# zulu_a7.net
KiCad netlist of a schematic drawn in EAGLE
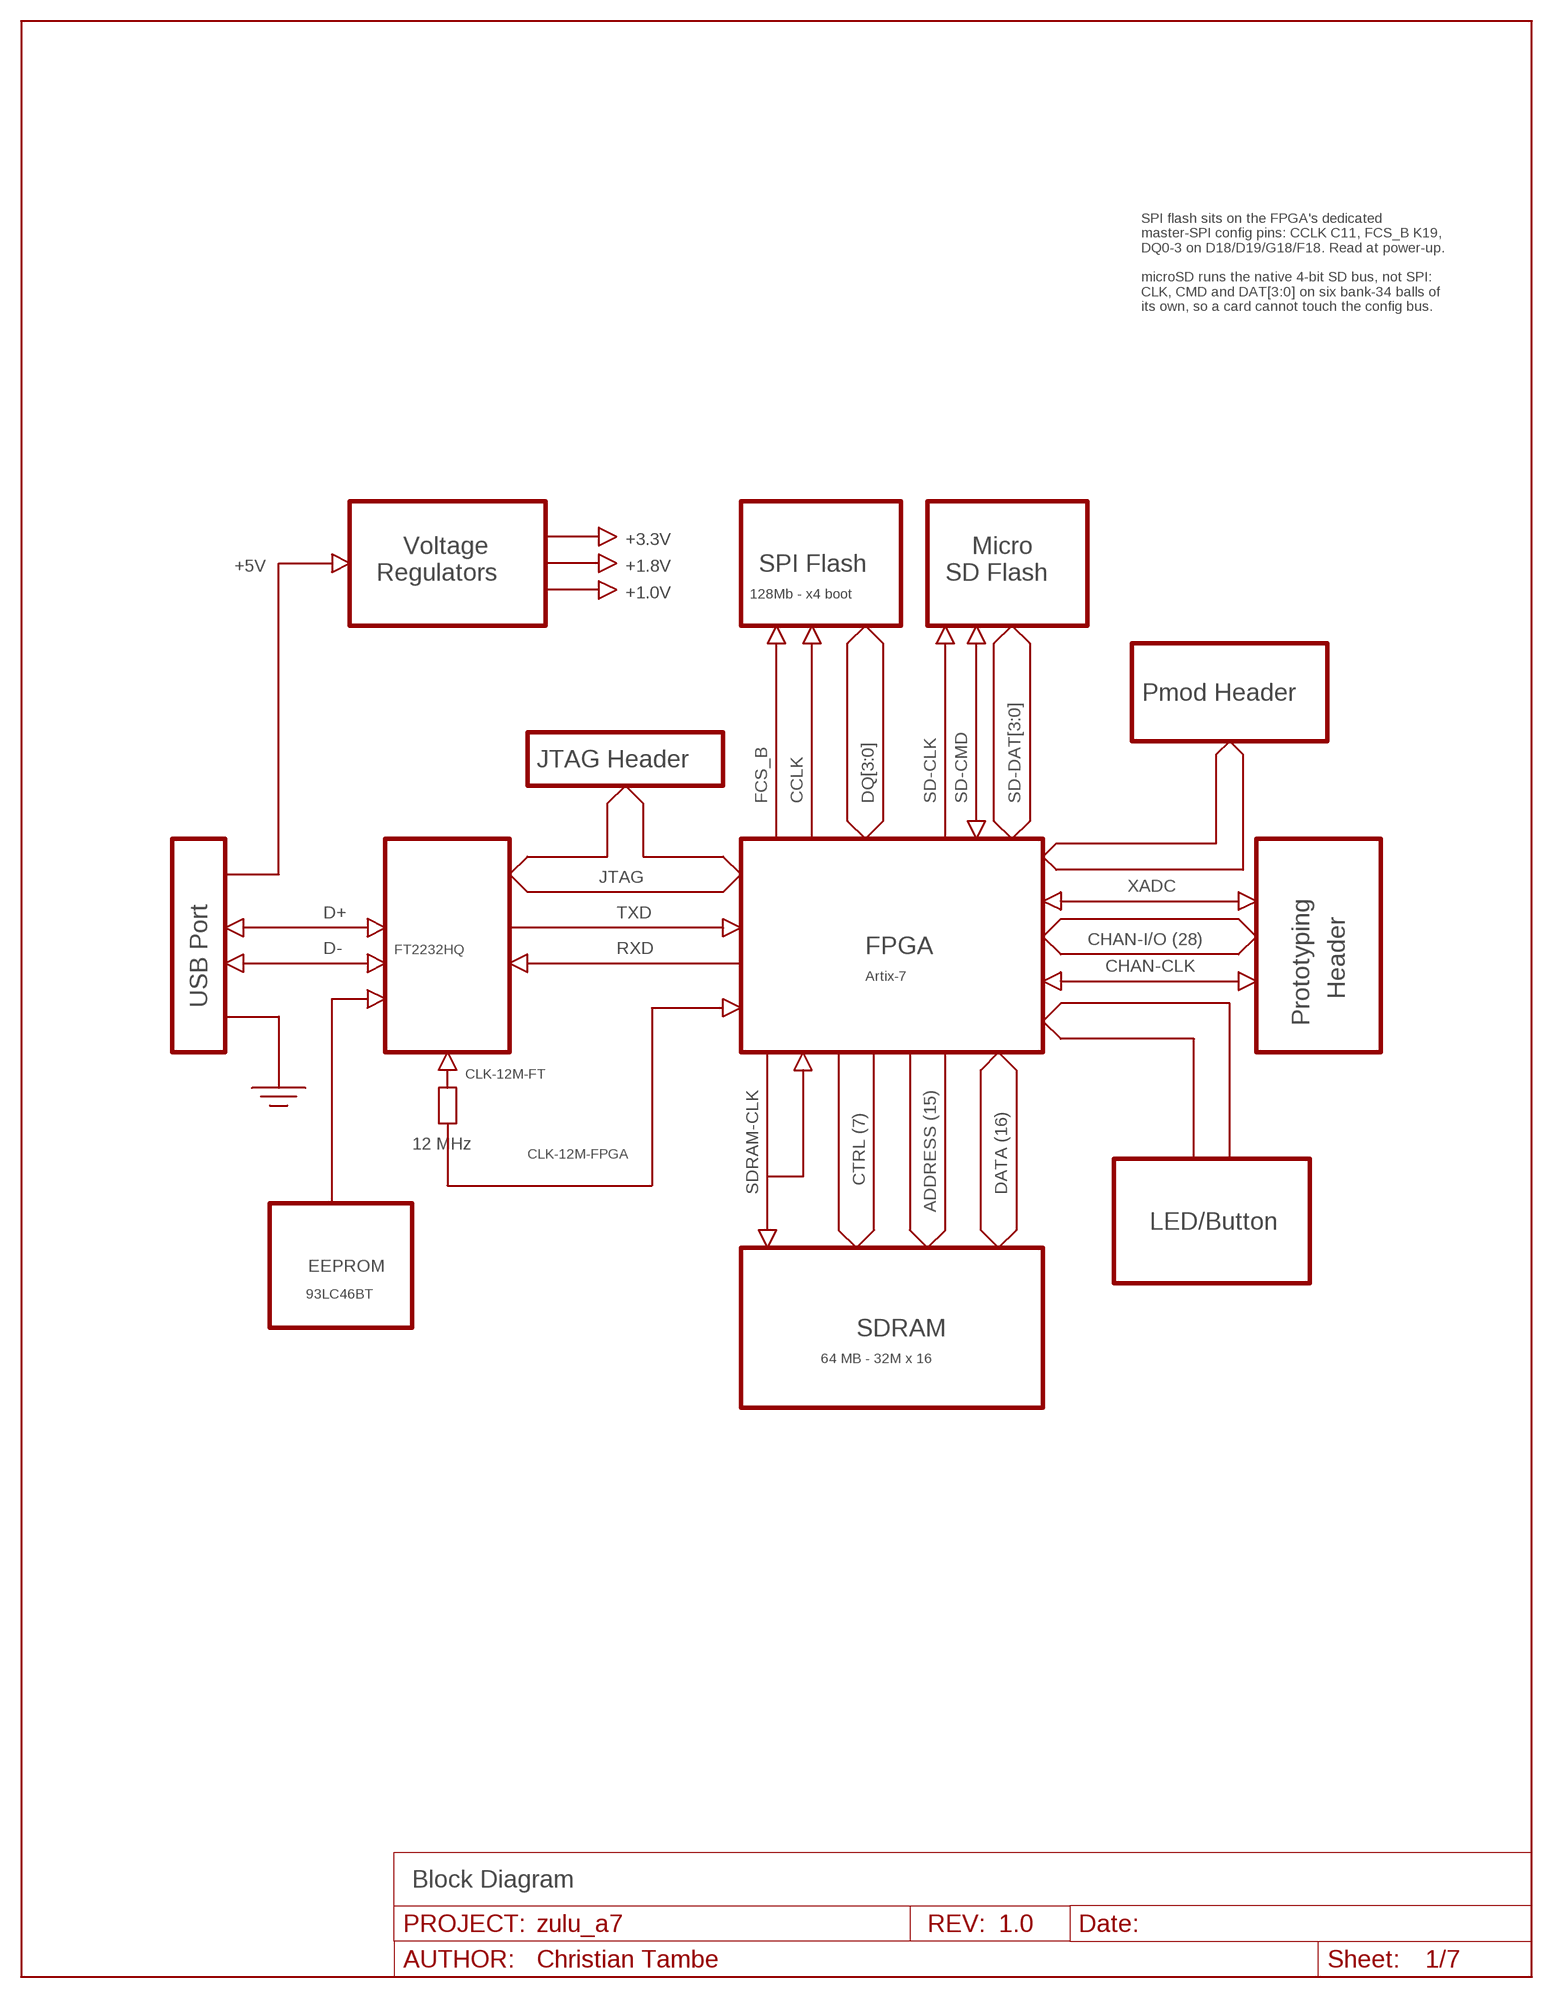
[diagram p0: schematic, sheet 1]
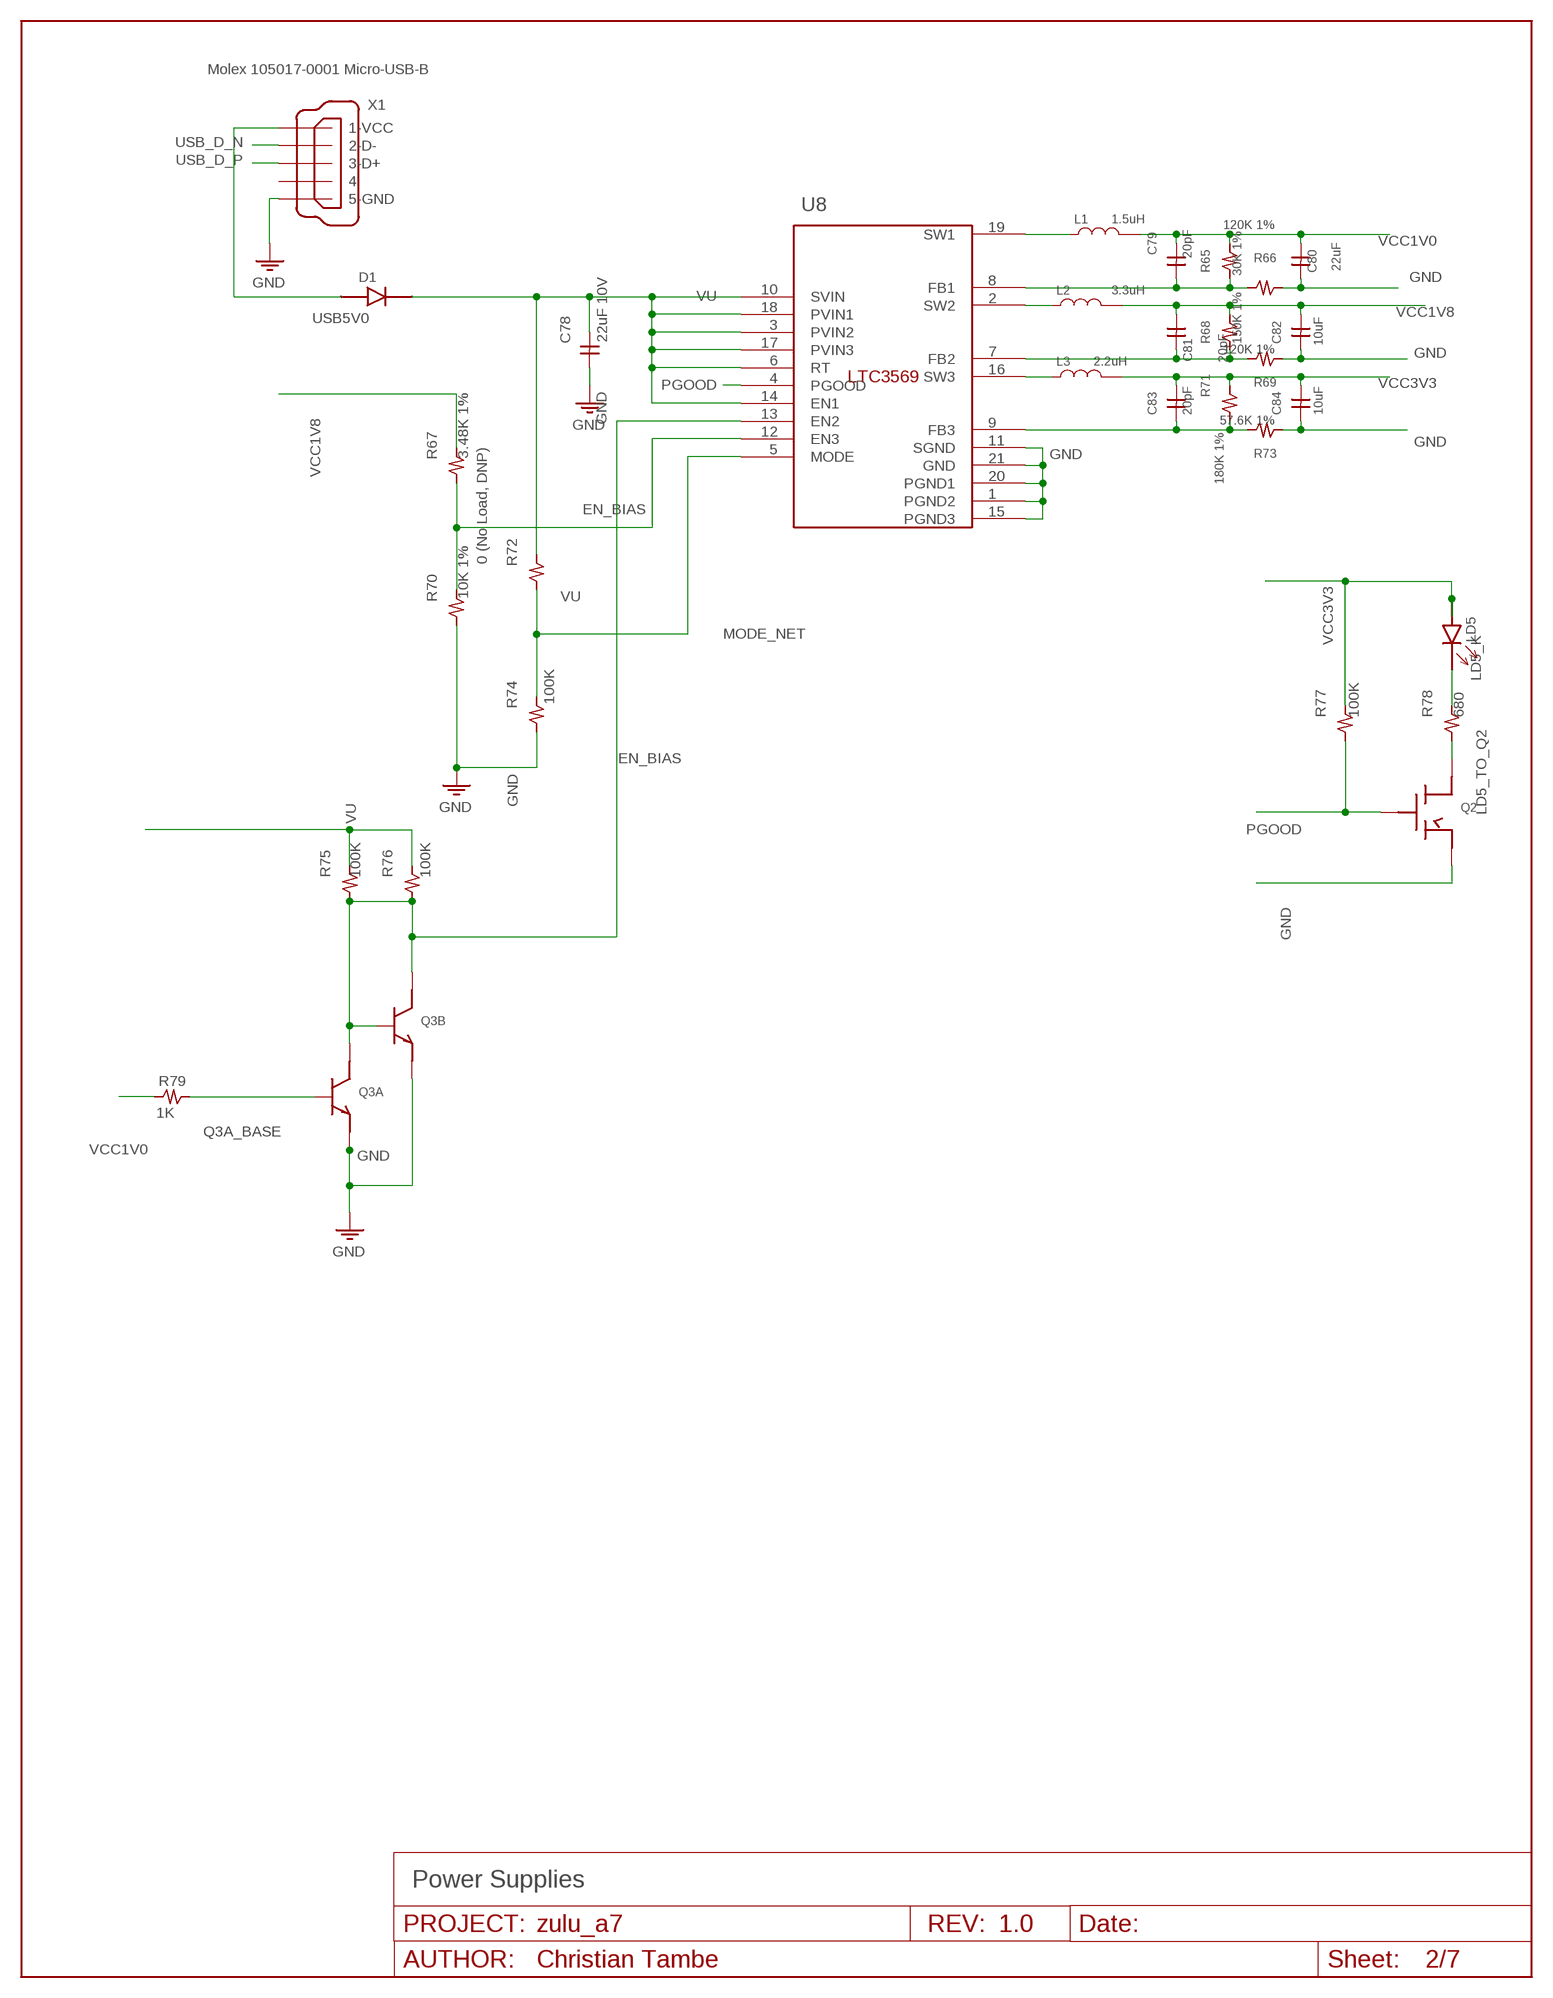
[diagram p1: schematic, sheet 2]
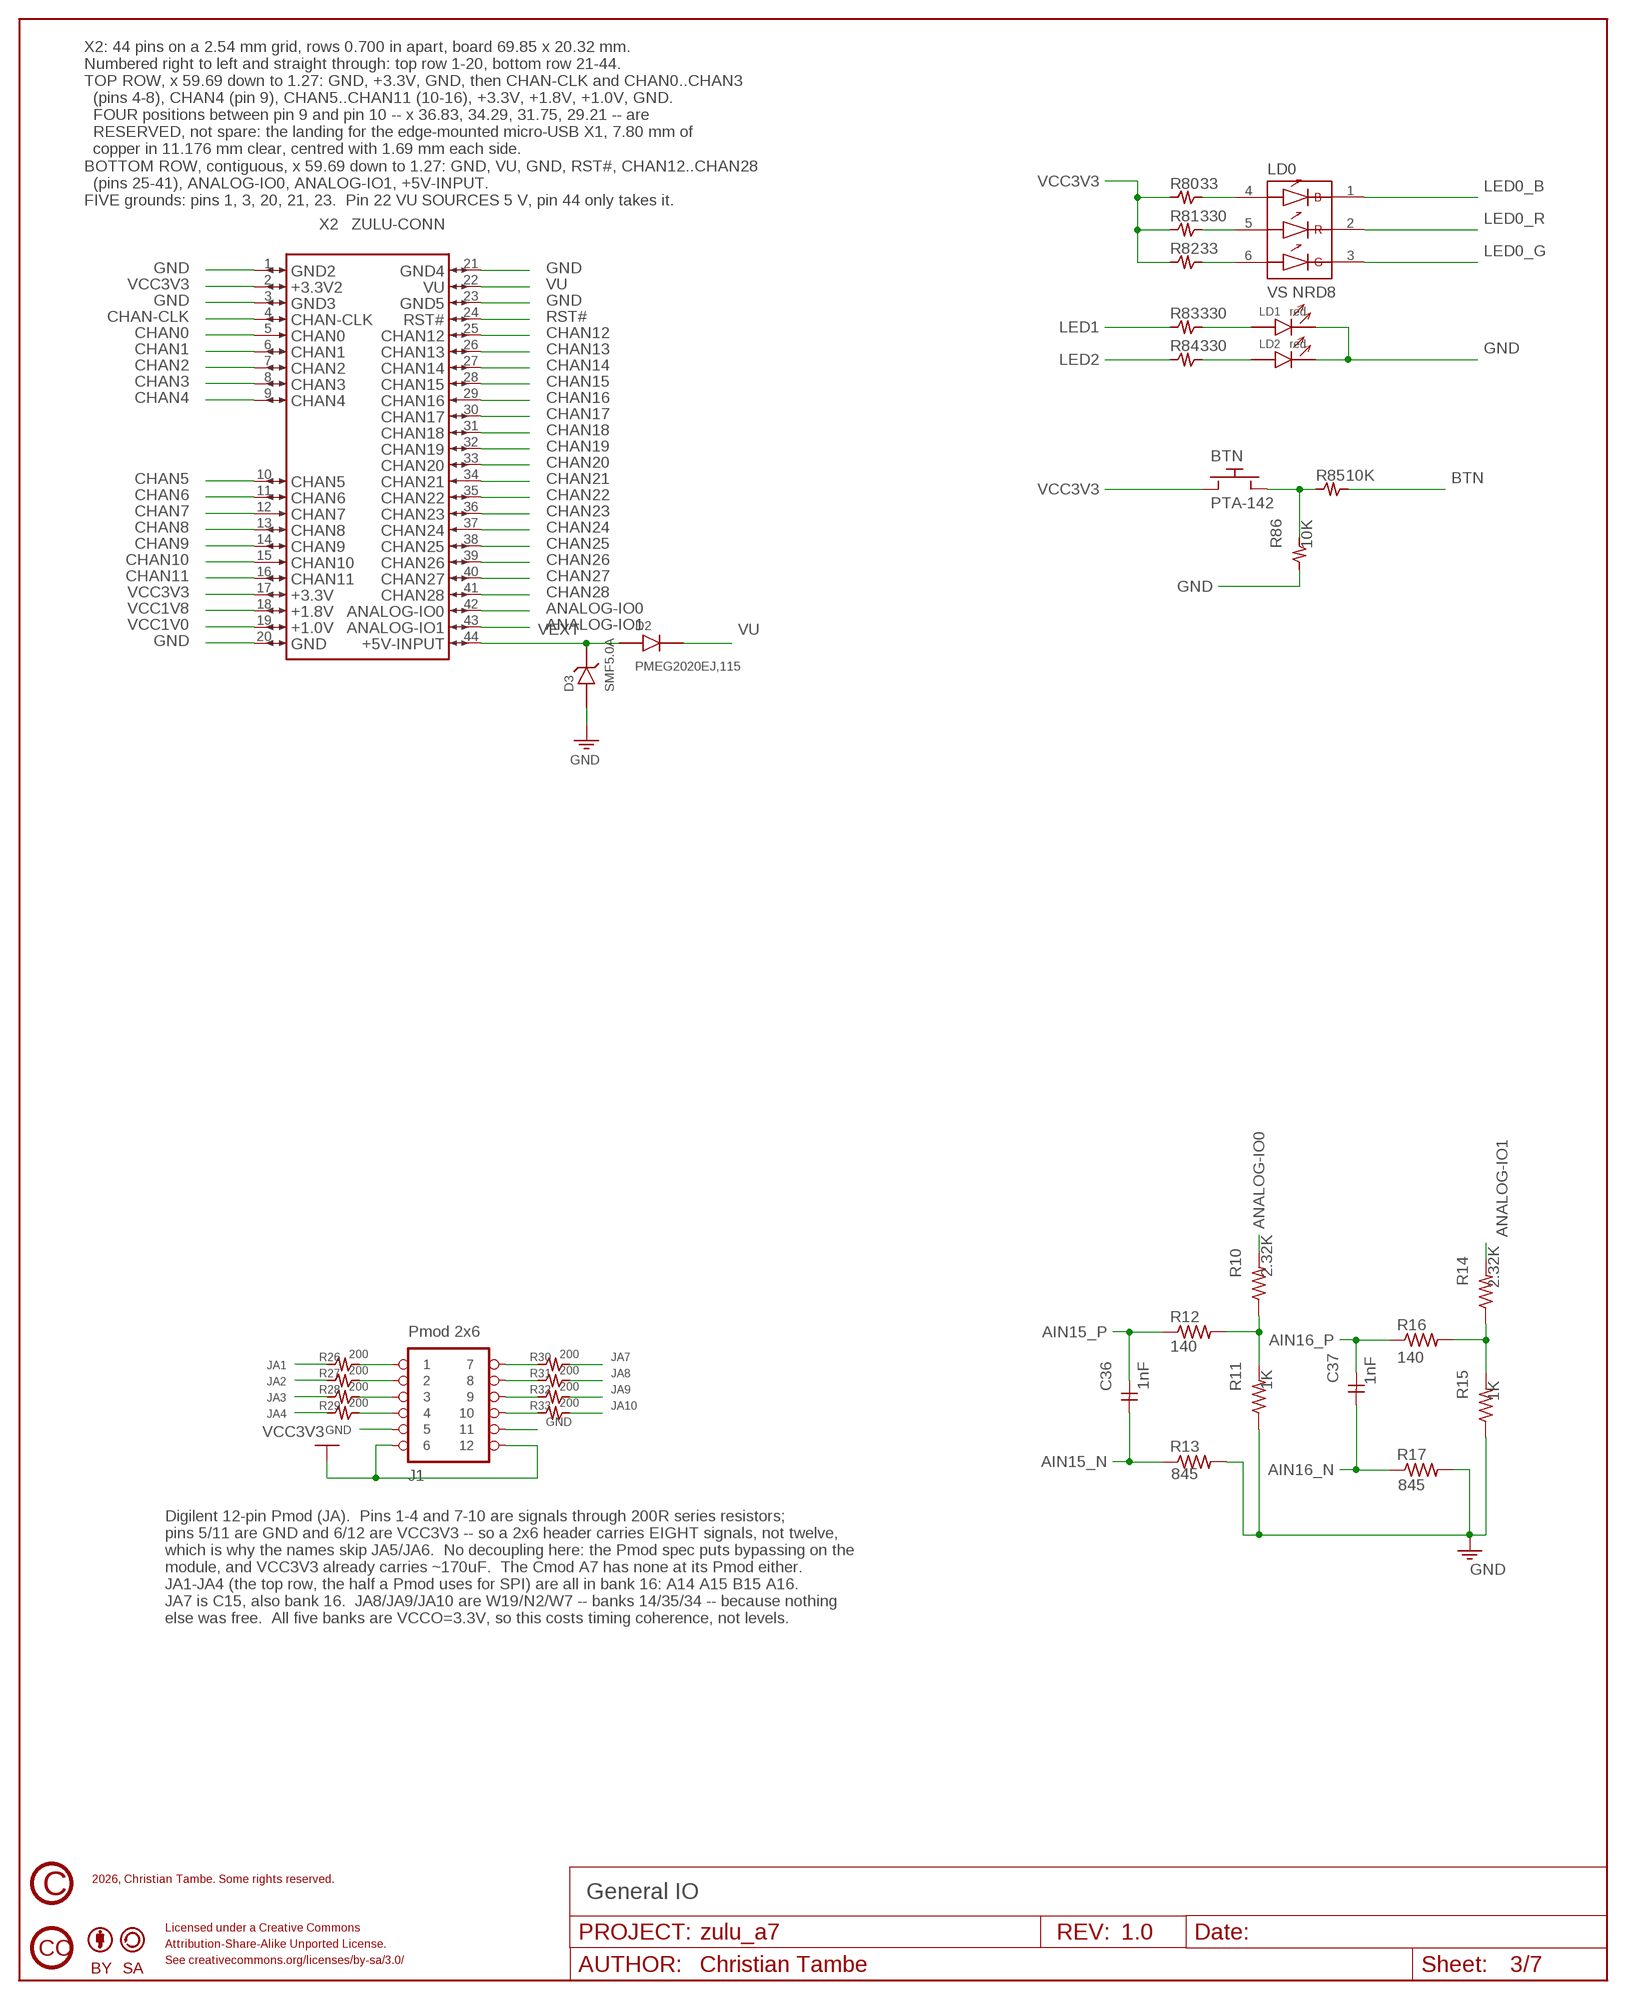
[diagram p2: schematic, sheet 3]
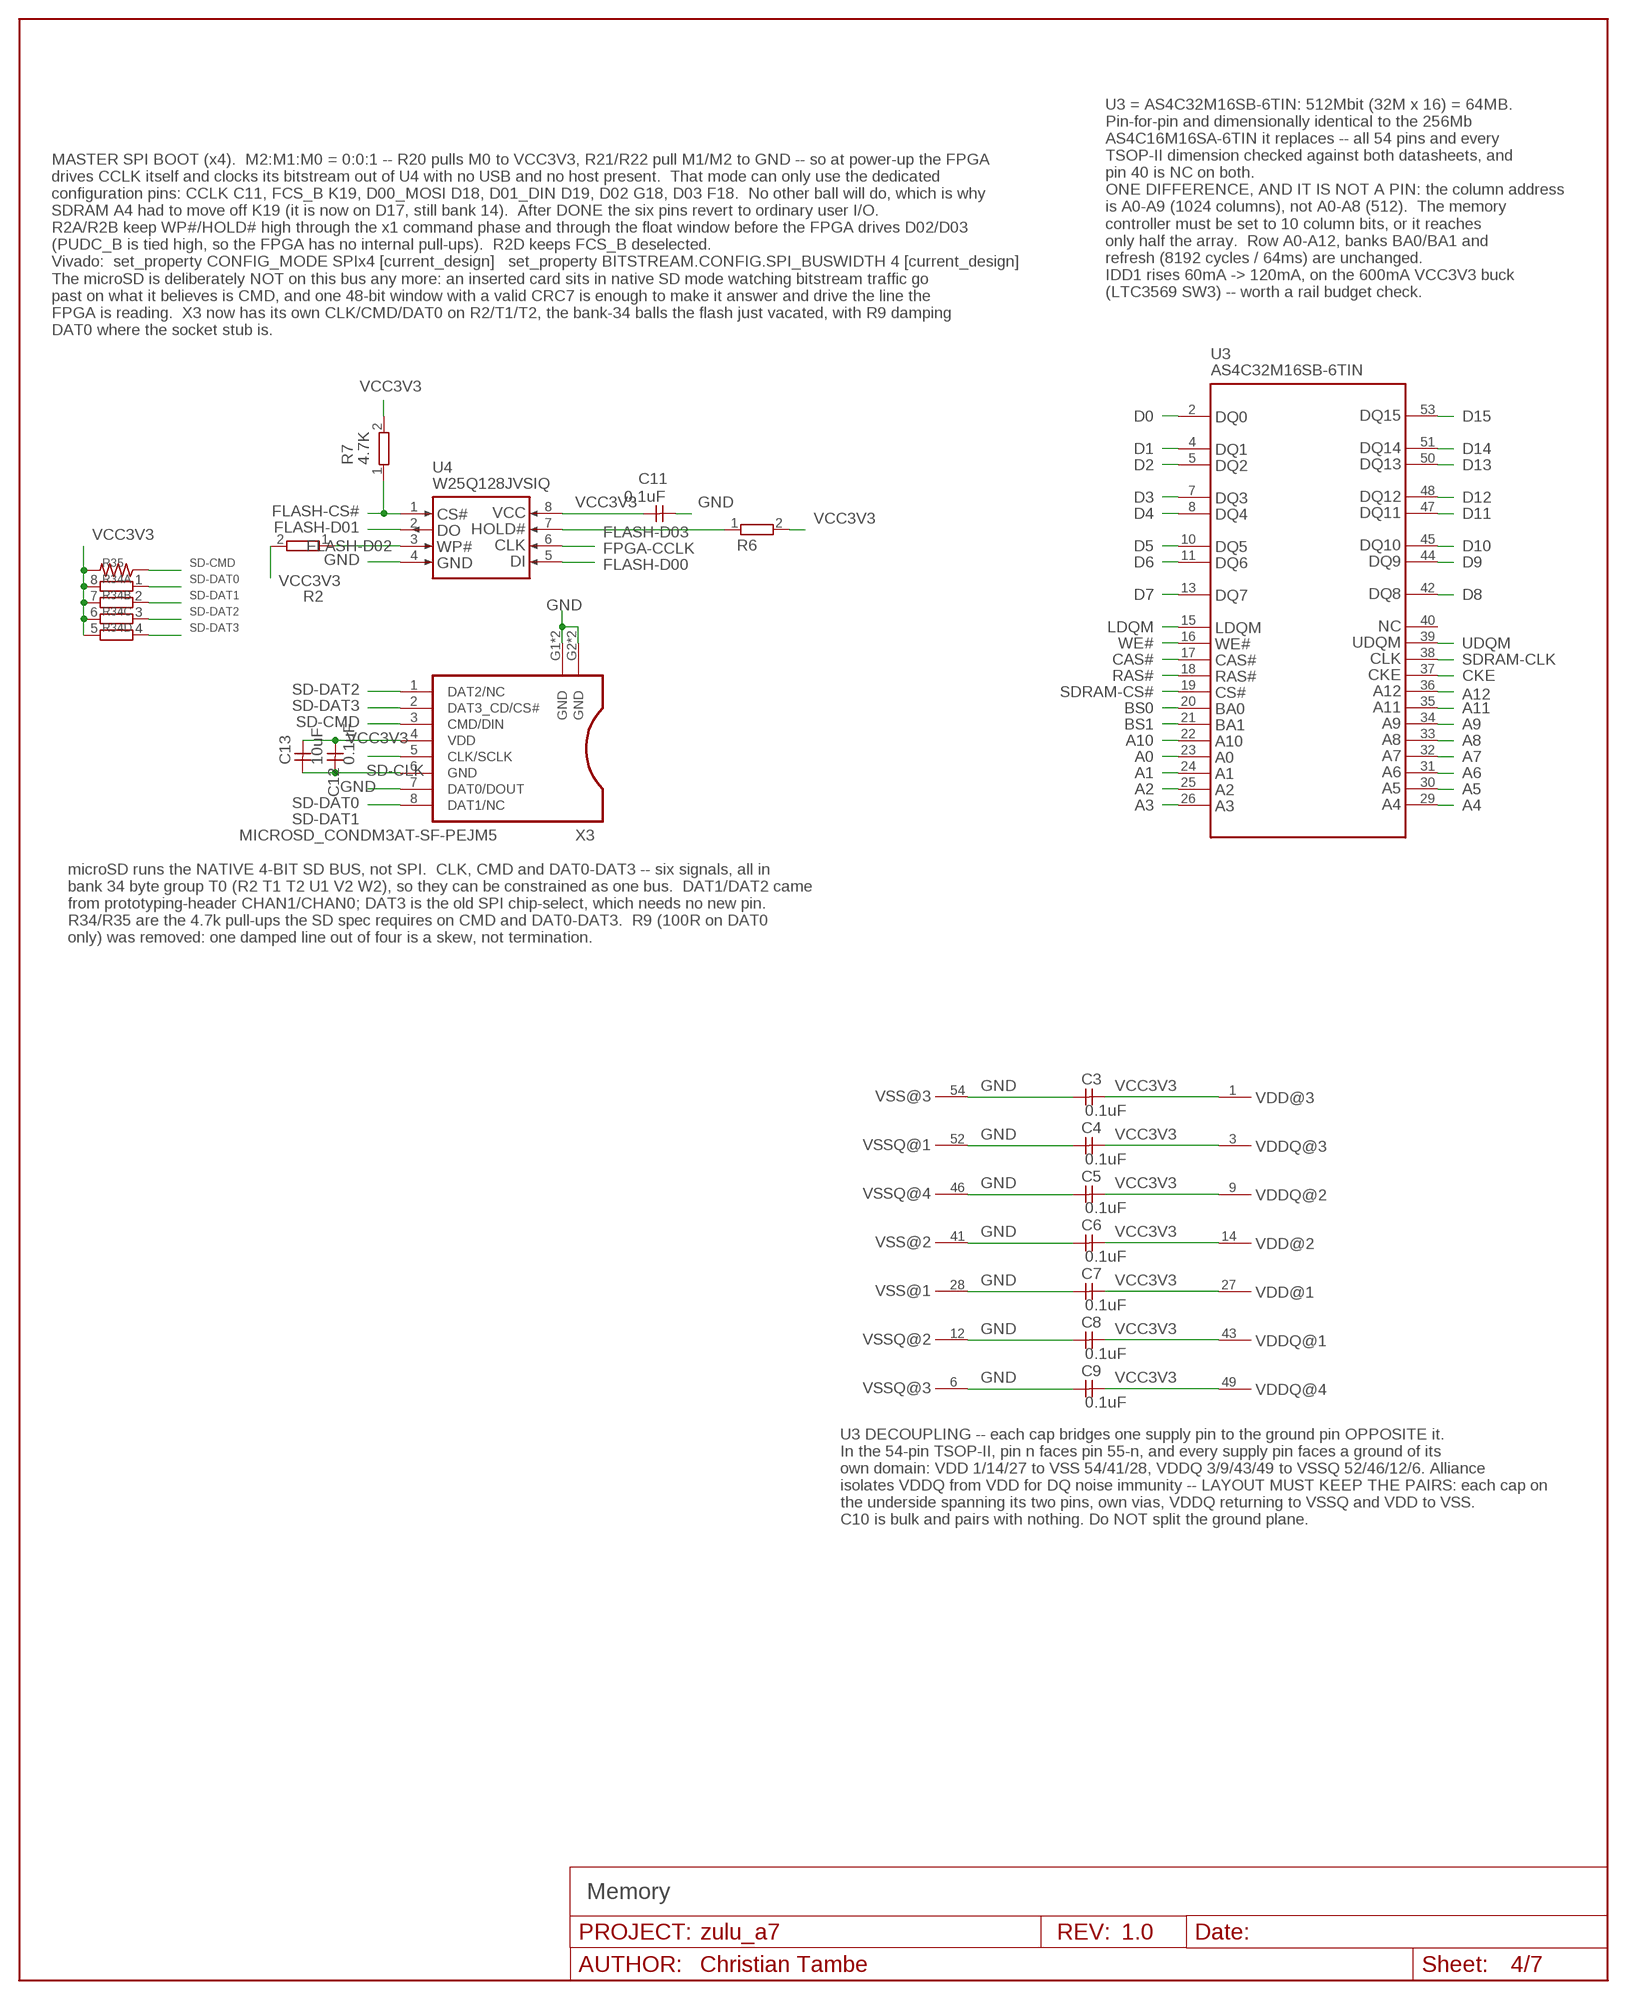
[diagram p3: schematic, sheet 4]
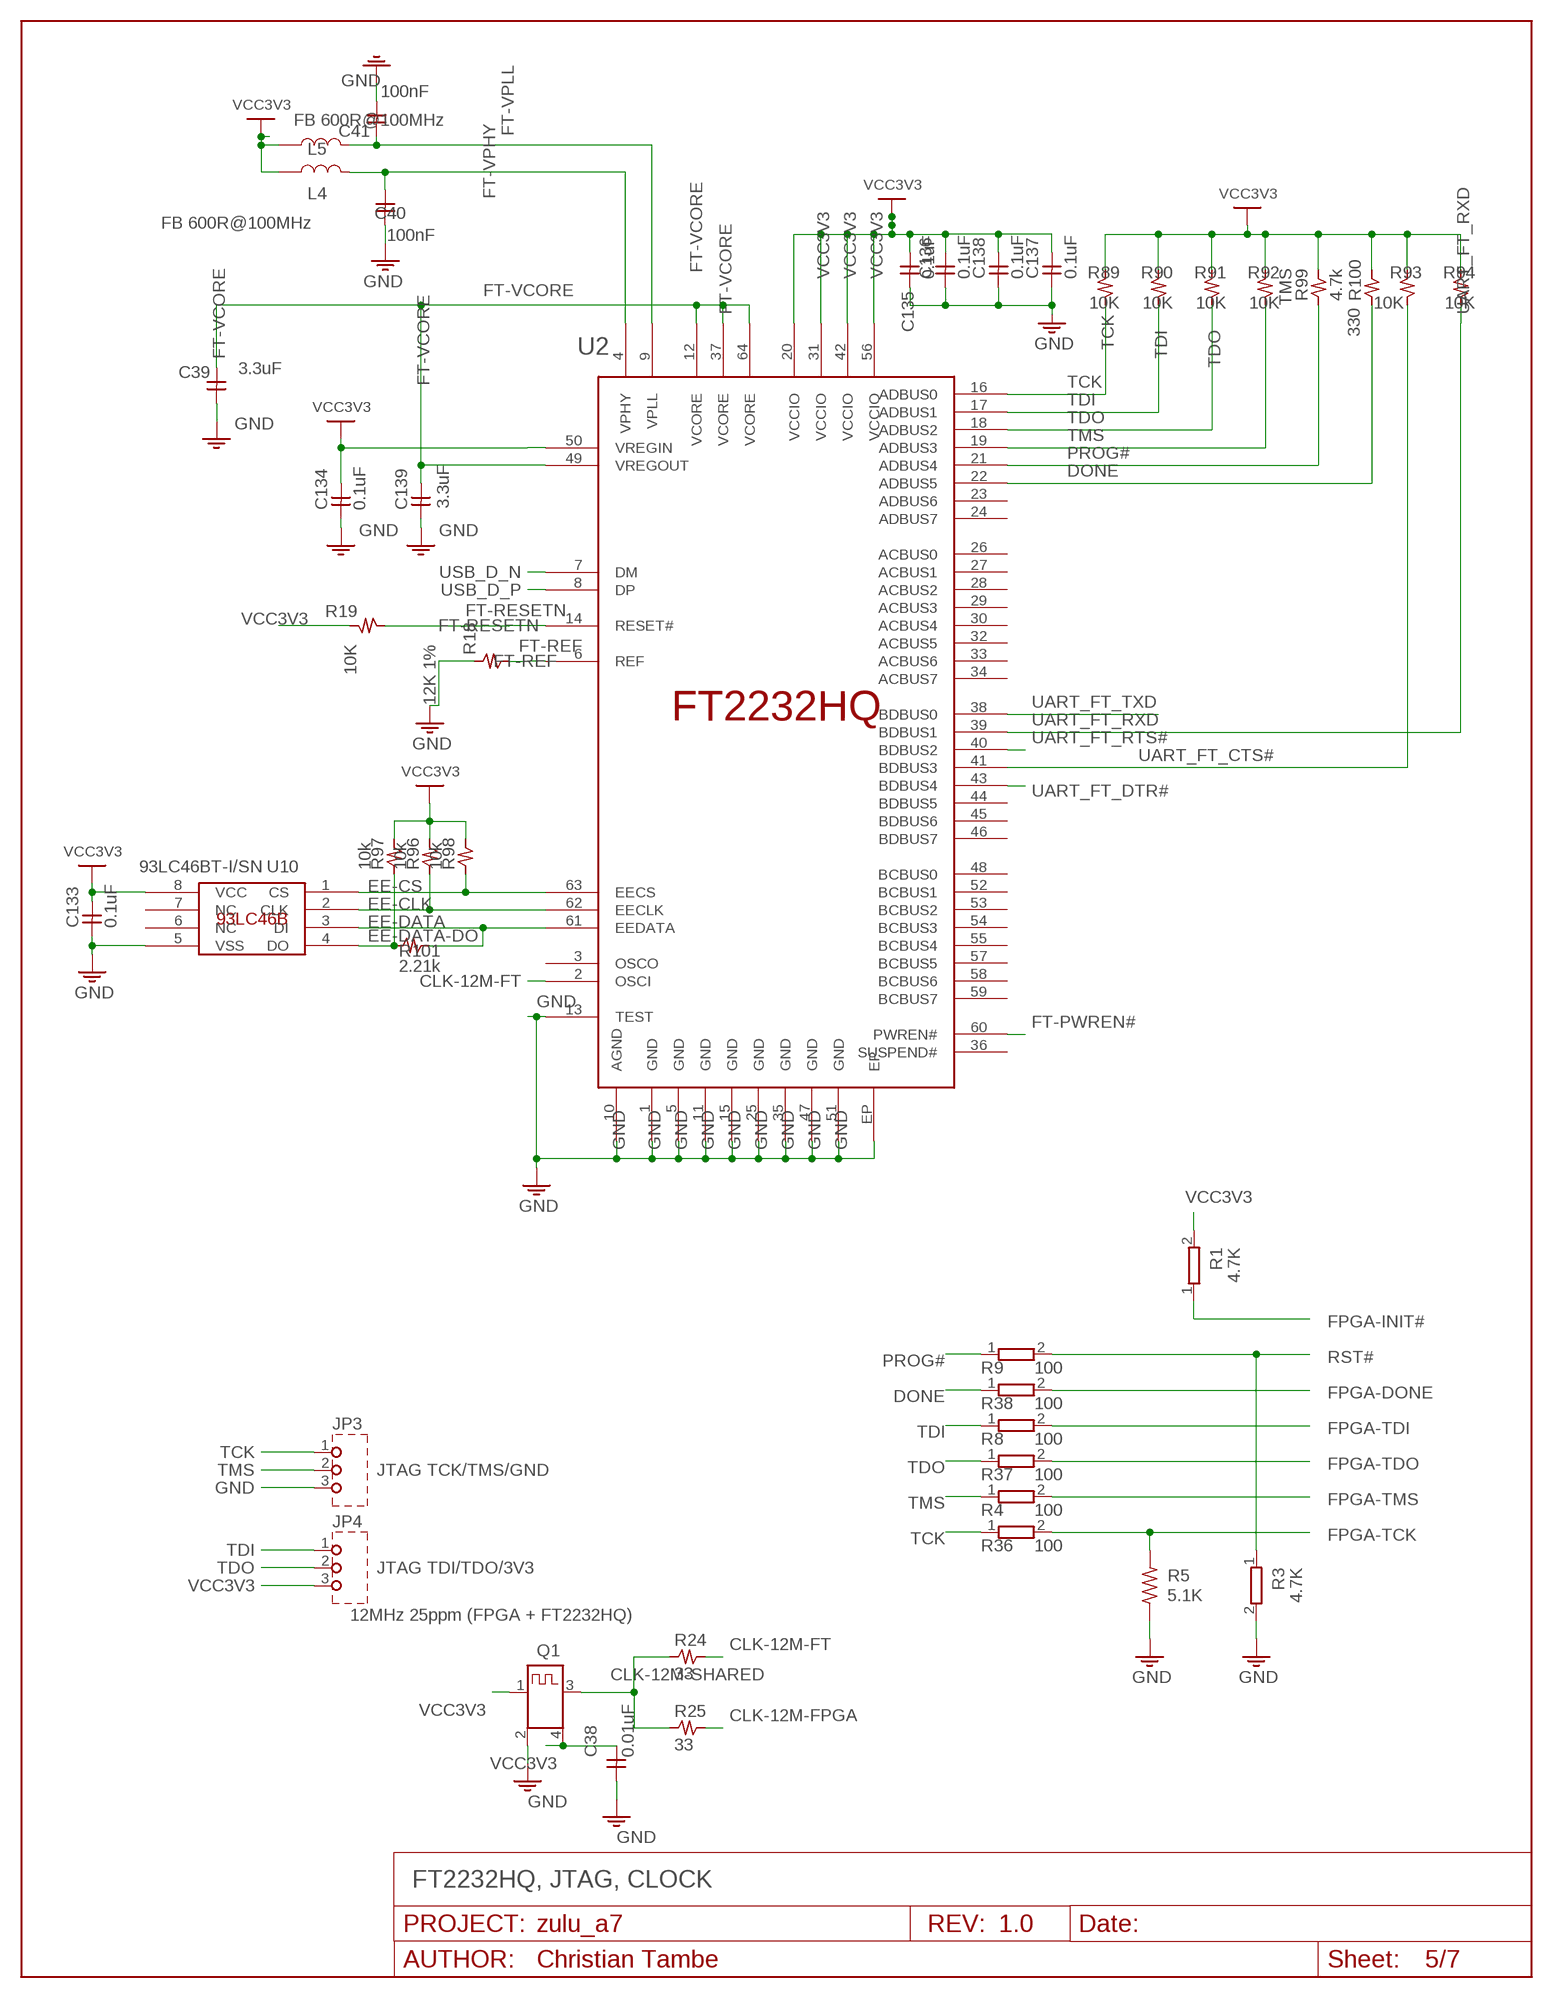
[diagram p4: schematic, sheet 5]
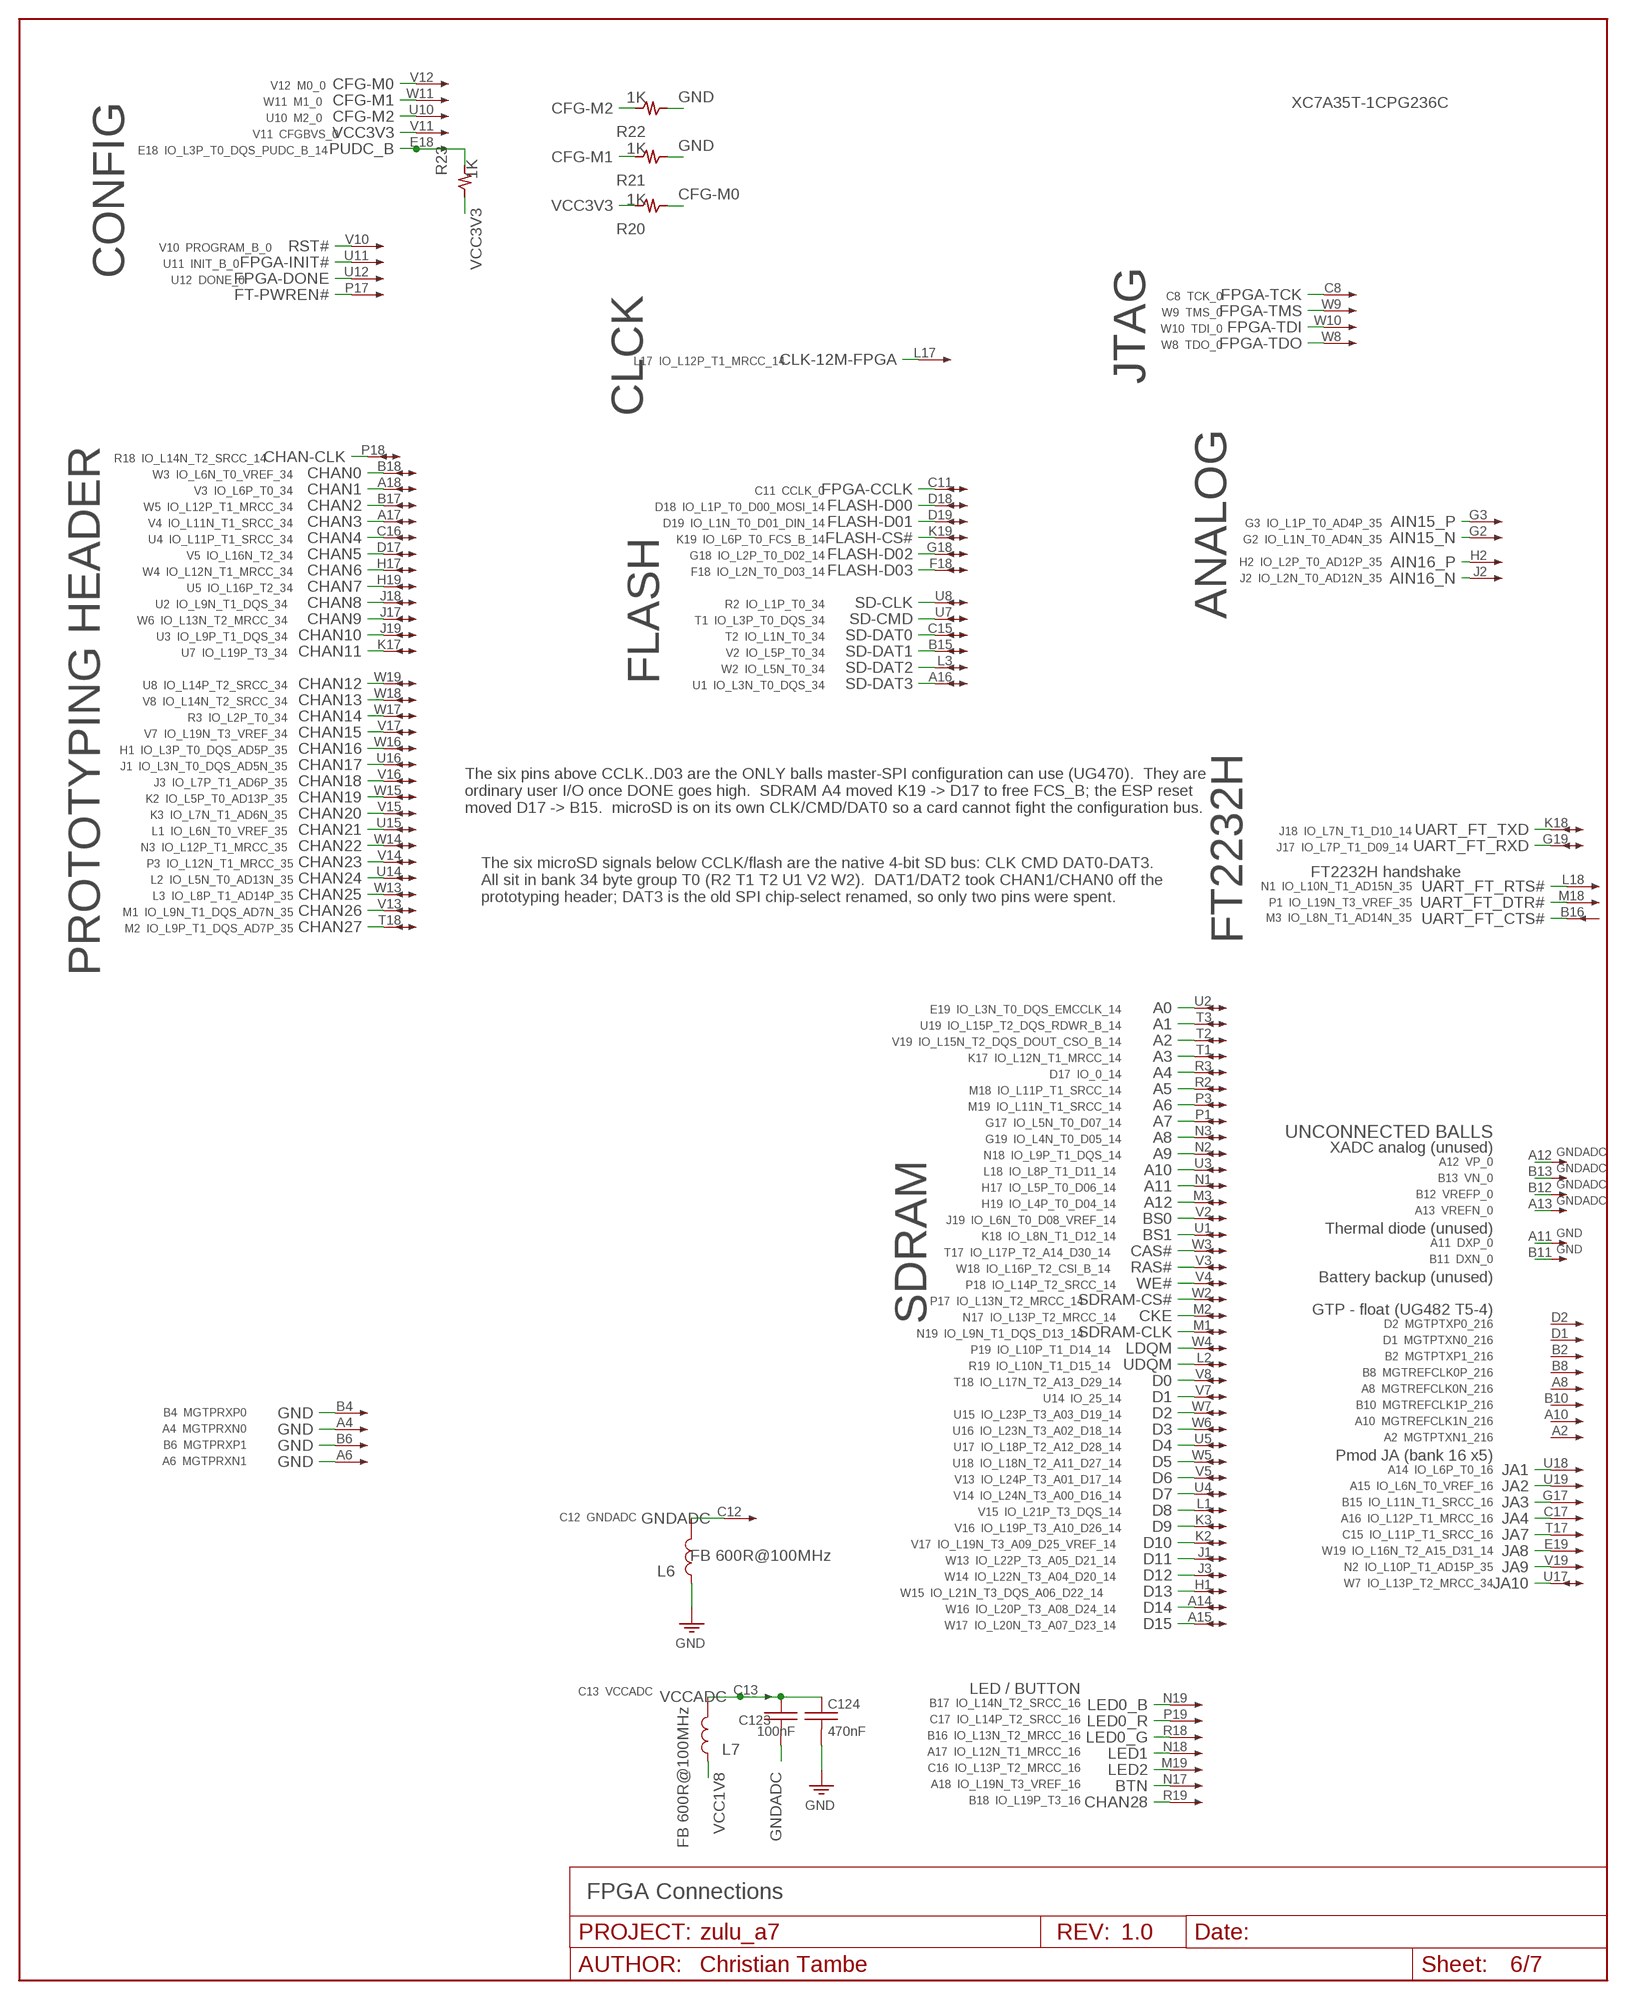
[diagram p5: schematic, sheet 6]
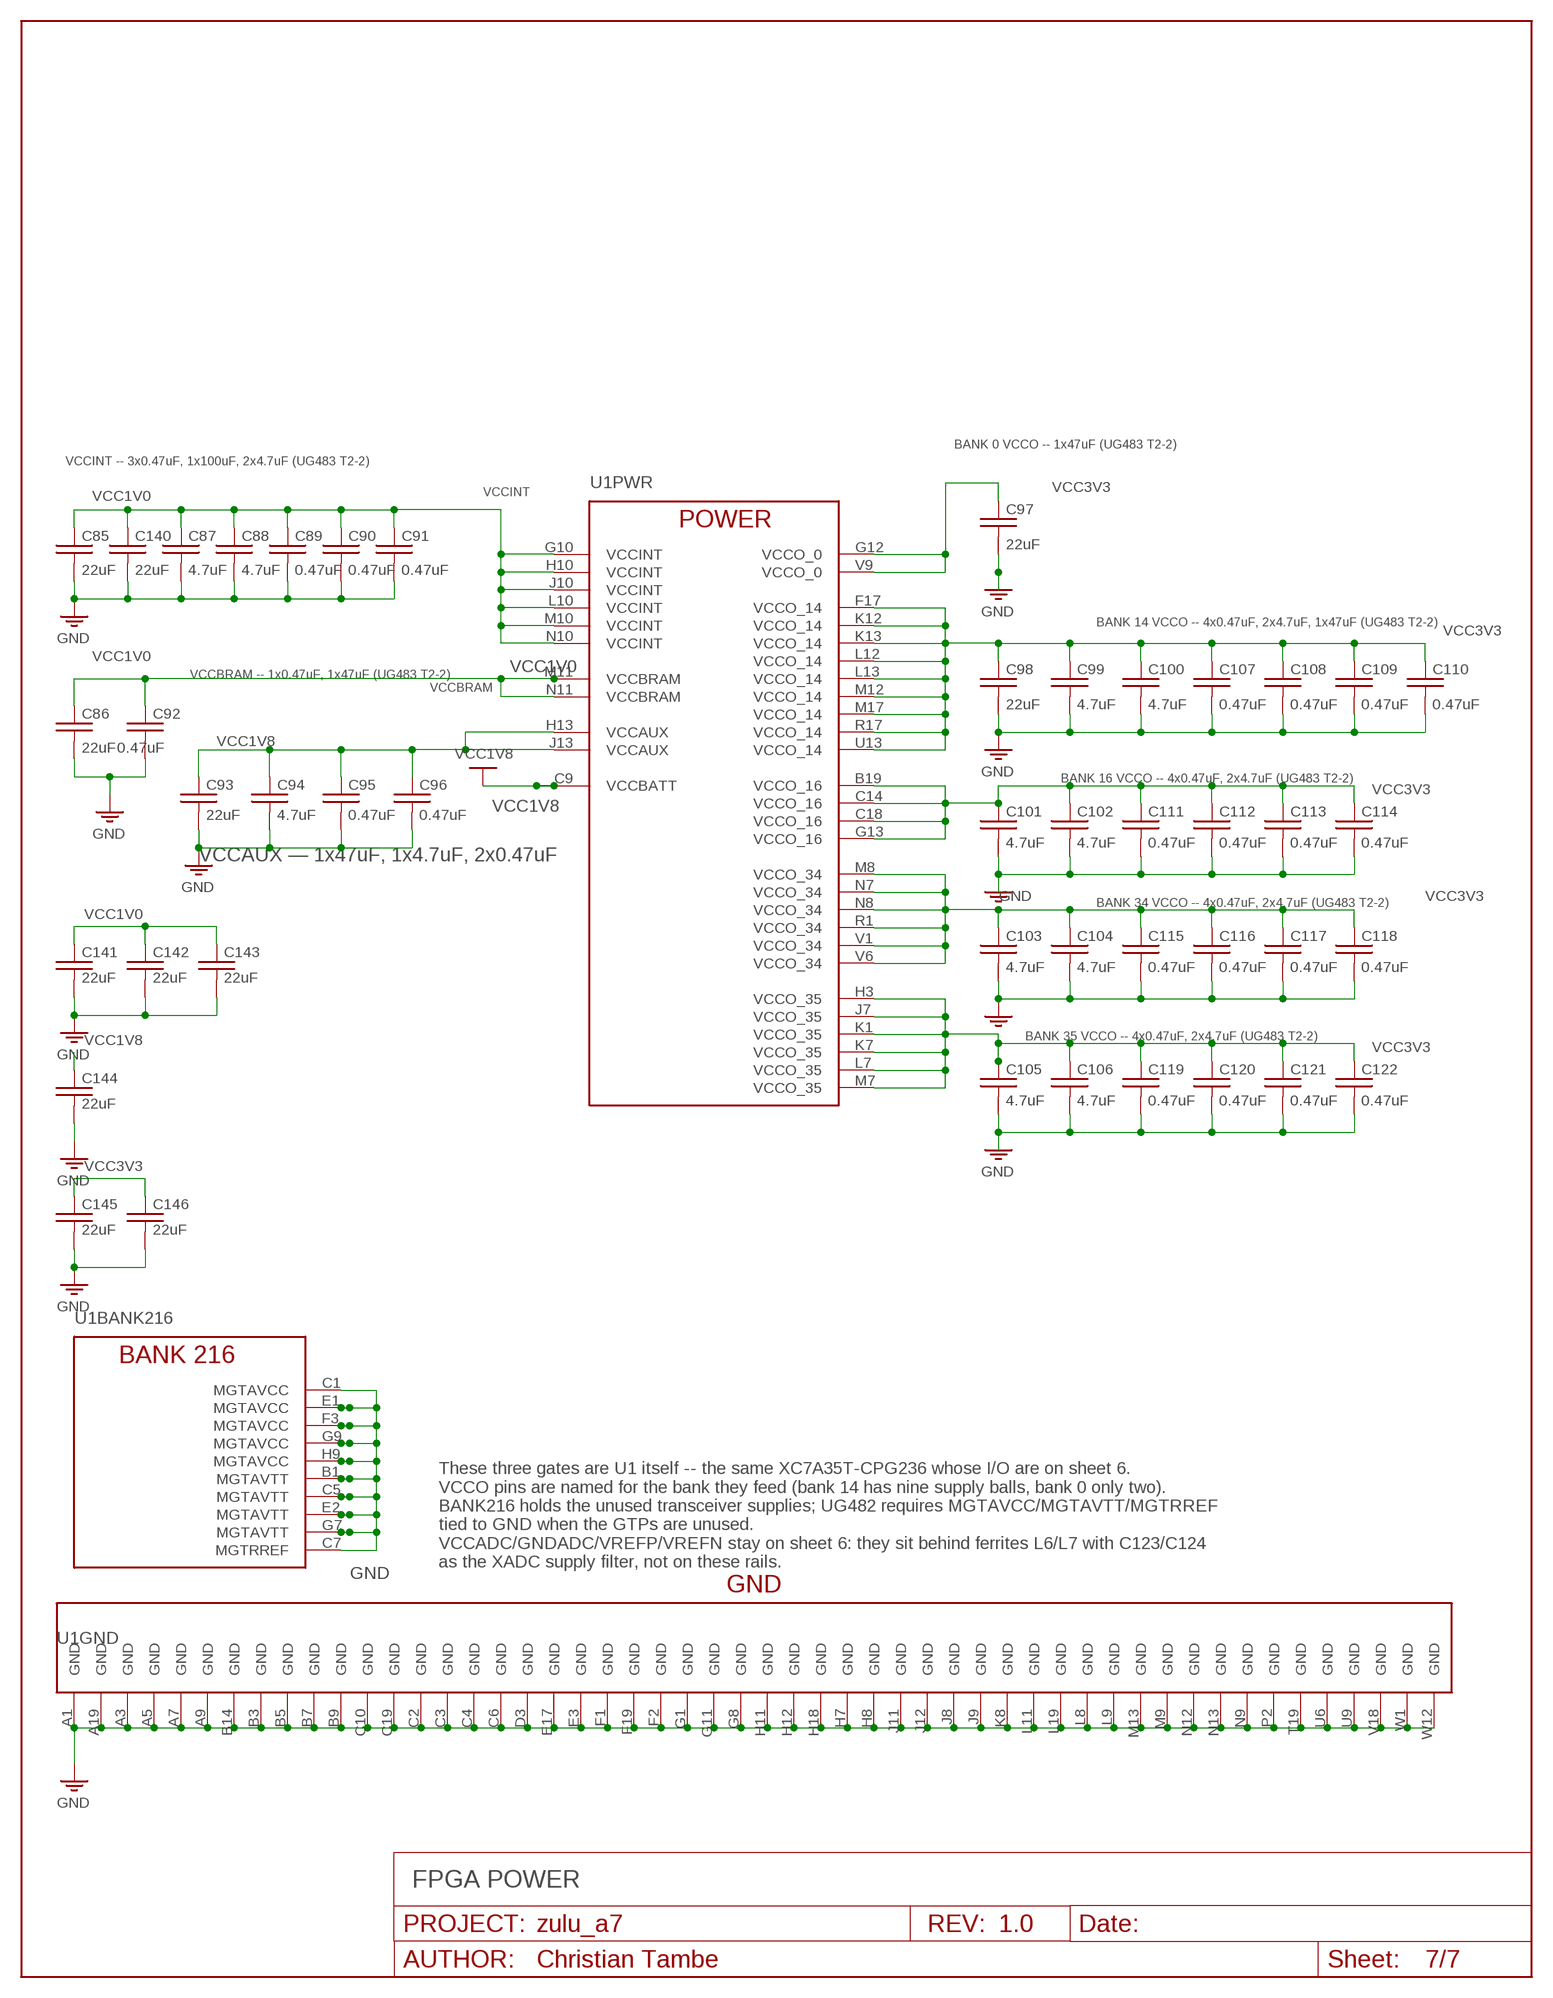
[diagram p6: schematic, sheet 7]

(export (version "E")
  (design (tool "Eeschema 10.0.6"))
  (components
    (comp (ref "C38")
      (value "0.01uF")
      (footprint "eagle-import:C0201")
      (fields
        (field (name "MANF") "Murata")
        (field (name "MANF#") "GRM033R71E103KE14D")
        (field (name "NOTE") "0402 -> 0201 on U2's support. 50V drops to 25V, which is still far over what a 3.3V rail needs -- the 50V part was over-specified. Confirm the MPN suffix before ordering.")
        (field (name "SPEC") "X7R 25V +-10%, 0.30 mm max")
      )
      (libsource (lib "eagle-import") (part "C-GENERICC0201"))
    )
    (comp (ref "C39")
      (value "3.3uF")
      (footprint "eagle-import:C0402")
      (fields
        (field (name "MANF") "Murata")
        (field (name "MANF#") "GRM155R60J335ME15D")
        (field (name "SPEC") "X5R 6.3V +-20%, 0.50 mm max -- FT2232H VCORE, DS_FT2232H asks for 3.3uF")
      )
      (libsource (lib "eagle-import") (part "C-GENERICC0402"))
    )
    (comp (ref "C40")
      (value "100nF")
      (footprint "eagle-import:C0201")
      (fields
        (field (name "MANF") "Murata")
        (field (name "MANF#") "GRM033R61A104KE15D")
        (field (name "NOTE") "0402 -> 0201 on U2's support. The DIELECTRIC AND VOLTAGE BOTH CHANGE: X7R 16V becomes X5R 10V, because 0201 at this capacitance is an X5R part. X5R narrows the temperature range to -55..+85 C from X7R's +125, which suits this board but is not a like-for-like swap. At 0.1 uF the DC bias derating is mild, unlike the 0.47 uF on sheet 7. Confirm the MPN suffix against Murata's data before ordering.")
        (field (name "SPEC") "X5R 10V +-10%, 0.30 mm max")
      )
      (libsource (lib "eagle-import") (part "C-GENERICC0201"))
    )
    (comp (ref "C41")
      (value "100nF")
      (footprint "eagle-import:C0201")
      (fields
        (field (name "MANF") "Murata")
        (field (name "MANF#") "GRM033R61A104KE15D")
        (field (name "NOTE") "0402 -> 0201 on U2's support. The DIELECTRIC AND VOLTAGE BOTH CHANGE: X7R 16V becomes X5R 10V, because 0201 at this capacitance is an X5R part. X5R narrows the temperature range to -55..+85 C from X7R's +125, which suits this board but is not a like-for-like swap. At 0.1 uF the DC bias derating is mild, unlike the 0.47 uF on sheet 7. Confirm the MPN suffix against Murata's data before ordering.")
        (field (name "SPEC") "X5R 10V +-10%, 0.30 mm max")
      )
      (libsource (lib "eagle-import") (part "C-GENERICC0201"))
    )
    (comp (ref "C133")
      (value "0.1uF")
      (footprint "eagle-import:C0201")
      (fields
        (field (name "MANF") "Murata")
        (field (name "MANF#") "GRM033R61A104KE15D")
        (field (name "NOTE") "0402 -> 0201 on U2's support. The DIELECTRIC AND VOLTAGE BOTH CHANGE: X7R 16V becomes X5R 10V, because 0201 at this capacitance is an X5R part. X5R narrows the temperature range to -55..+85 C from X7R's +125, which suits this board but is not a like-for-like swap. At 0.1 uF the DC bias derating is mild, unlike the 0.47 uF on sheet 7. Confirm the MPN suffix against Murata's data before ordering.")
        (field (name "SPEC") "X5R 10V +-10%, 0.30 mm max")
      )
      (libsource (lib "eagle-import") (part "C-GENERICC0201"))
    )
    (comp (ref "C134")
      (value "0.1uF")
      (footprint "eagle-import:C0201")
      (fields
        (field (name "MANF") "Murata")
        (field (name "MANF#") "GRM033R61A104KE15D")
        (field (name "NOTE") "0402 -> 0201 on U2's support. The DIELECTRIC AND VOLTAGE BOTH CHANGE: X7R 16V becomes X5R 10V, because 0201 at this capacitance is an X5R part. X5R narrows the temperature range to -55..+85 C from X7R's +125, which suits this board but is not a like-for-like swap. At 0.1 uF the DC bias derating is mild, unlike the 0.47 uF on sheet 7. Confirm the MPN suffix against Murata's data before ordering.")
        (field (name "SPEC") "X5R 10V +-10%, 0.30 mm max")
      )
      (libsource (lib "eagle-import") (part "C-GENERICC0201"))
    )
    (comp (ref "C135")
      (value "0.1uF")
      (footprint "eagle-import:C0201")
      (fields
        (field (name "MANF") "Murata")
        (field (name "MANF#") "GRM033R61A104KE15D")
        (field (name "NOTE") "0402 -> 0201 on U2's support. The DIELECTRIC AND VOLTAGE BOTH CHANGE: X7R 16V becomes X5R 10V, because 0201 at this capacitance is an X5R part. X5R narrows the temperature range to -55..+85 C from X7R's +125, which suits this board but is not a like-for-like swap. At 0.1 uF the DC bias derating is mild, unlike the 0.47 uF on sheet 7. Confirm the MPN suffix against Murata's data before ordering.")
        (field (name "SPEC") "X5R 10V +-10%, 0.30 mm max")
      )
      (libsource (lib "eagle-import") (part "C-GENERICC0201"))
    )
    (comp (ref "C136")
      (value "0.1uF")
      (footprint "eagle-import:C0201")
      (fields
        (field (name "MANF") "Murata")
        (field (name "MANF#") "GRM033R61A104KE15D")
        (field (name "NOTE") "0402 -> 0201 on U2's support. The DIELECTRIC AND VOLTAGE BOTH CHANGE: X7R 16V becomes X5R 10V, because 0201 at this capacitance is an X5R part. X5R narrows the temperature range to -55..+85 C from X7R's +125, which suits this board but is not a like-for-like swap. At 0.1 uF the DC bias derating is mild, unlike the 0.47 uF on sheet 7. Confirm the MPN suffix against Murata's data before ordering.")
        (field (name "SPEC") "X5R 10V +-10%, 0.30 mm max")
      )
      (libsource (lib "eagle-import") (part "C-GENERICC0201"))
    )
    (comp (ref "C137")
      (value "0.1uF")
      (footprint "eagle-import:C0201")
      (fields
        (field (name "MANF") "Murata")
        (field (name "MANF#") "GRM033R61A104KE15D")
        (field (name "NOTE") "0402 -> 0201 on U2's support. The DIELECTRIC AND VOLTAGE BOTH CHANGE: X7R 16V becomes X5R 10V, because 0201 at this capacitance is an X5R part. X5R narrows the temperature range to -55..+85 C from X7R's +125, which suits this board but is not a like-for-like swap. At 0.1 uF the DC bias derating is mild, unlike the 0.47 uF on sheet 7. Confirm the MPN suffix against Murata's data before ordering.")
        (field (name "SPEC") "X5R 10V +-10%, 0.30 mm max")
      )
      (libsource (lib "eagle-import") (part "C-GENERICC0201"))
    )
    (comp (ref "C138")
      (value "0.1uF")
      (footprint "eagle-import:C0201")
      (fields
        (field (name "MANF") "Murata")
        (field (name "MANF#") "GRM033R61A104KE15D")
        (field (name "NOTE") "0402 -> 0201 on U2's support. The DIELECTRIC AND VOLTAGE BOTH CHANGE: X7R 16V becomes X5R 10V, because 0201 at this capacitance is an X5R part. X5R narrows the temperature range to -55..+85 C from X7R's +125, which suits this board but is not a like-for-like swap. At 0.1 uF the DC bias derating is mild, unlike the 0.47 uF on sheet 7. Confirm the MPN suffix against Murata's data before ordering.")
        (field (name "SPEC") "X5R 10V +-10%, 0.30 mm max")
      )
      (libsource (lib "eagle-import") (part "C-GENERICC0201"))
    )
    (comp (ref "C139")
      (value "3.3uF")
      (footprint "eagle-import:C0402")
      (fields
        (field (name "MANF") "Murata")
        (field (name "MANF#") "GRM155R60J335ME15D")
        (field (name "SPEC") "X5R 6.3V +-20%, 0.50 mm max -- FT2232H VCORE, DS_FT2232H asks for 3.3uF")
      )
      (libsource (lib "eagle-import") (part "C-GENERICC0402"))
    )
    (comp (ref "JP3")
      (value "JTAG TCK/TMS/GND")
      (footprint "eagle-import:1X03-NOSILK")
      (fields
        (field (name "NOTE") "Bare plated holes -- NO HEADER FITTED, nothing to order. Three of the six JTAG holes; JP4 carries the other three, 17.96 mm away on the far side of the Pmod. Each row has 3.05 mm of board to the Pmod but only 0.09 mm to a 1x3 strip's body, so these are for flying leads or a pogo jig. The FT2232 does JTAG over USB on channel B; this is the fallback.")
      )
      (libsource (lib "eagle-import") (part "TESTPT-1X3NOSILK"))
    )
    (comp (ref "JP4")
      (value "JTAG TDI/TDO/3V3")
      (footprint "eagle-import:1X03-NOSILK")
      (fields
        (field (name "NOTE") "Bare plated holes -- NO HEADER FITTED, nothing to order. Three of the six JTAG holes; JP3 carries the other three, 17.96 mm away on the far side of the Pmod. Each row has 3.05 mm of board to the Pmod but only 0.09 mm to a 1x3 strip's body, so these are for flying leads or a pogo jig. The FT2232 does JTAG over USB on channel B; this is the fallback.")
      )
      (libsource (lib "eagle-import") (part "TESTPT-1X3NOSILK"))
    )
    (comp (ref "L4")
      (value "FB 600R@100MHz")
      (footprint "eagle-import:IND0603")
      (fields
        (field (name "MANF") "Murata")
        (field (name "MANF#") "BLM18PG601SN1D")
        (field (name "SPEC") "600 ohm at 100MHz, 1.5A, 0.90 mm max")
      )
      (libsource (lib "eagle-import") (part "INDUCTOR"))
    )
    (comp (ref "L5")
      (value "FB 600R@100MHz")
      (footprint "eagle-import:IND0603")
      (fields
        (field (name "MANF") "Murata")
        (field (name "MANF#") "BLM18PG601SN1D")
        (field (name "SPEC") "600 ohm at 100MHz, 1.5A, 0.90 mm max")
      )
      (libsource (lib "eagle-import") (part "INDUCTOR"))
    )
    (comp (ref "Q1")
      (value "12MHz 25ppm (FPGA + FT2232HQ)")
      (footprint "eagle-import:32X25")
      (fields
        (field (name "MANF") "Abracon")
        (field (name "MANF_1") "Abracon")
        (field (name "MANF#") "ASEM1-12.000MHZ-LC-T")
        (field (name "NOTE") "ACTIVE OSCILLATOR, NOT A CRYSTAL -- the schematic settles it: pin 2 to GND, pin 4 to VCC3V3, pin 3 out into R24 and R25, and pin 1 tied to VCC3V3, which is a 4-pad XO with its enable held high. A crystal would have two pads and load capacitors. THE FREQUENCY IS NOT A CHOICE: the FT2232H wants 12 MHz for its USB PLL, so that was fixed before anything else. 25 ppm is the value already recorded and is comfortably inside what FTDI asks of the reference. Output drives two loads through 33R each, the FT2232's OSCI and the FPGA clock ball. Pin 1 to Vdd suits either an OE part or one with pin 1 not connected, so the choice is not narrowed by it. ASEM1 is the family the design note already named. Confirm the suffix -- it encodes stability and temperature range and is the easy thing to get wrong.")
        (field (name "SPEC") "12.000 MHz CMOS oscillator, 3.3V, 25 ppm, 3.2 x 2.5 mm 4-pad, pin 1 enable or NC, pin 3 output")
      )
      (libsource (lib "eagle-import") (part "OSC_CHIPASEM1-12MHZ"))
    )
    (comp (ref "R1")
      (value "4.7K")
      (footprint "eagle-import:R0201")
      (fields
        (field (name "MANF") "Yageo")
        (field (name "MANF#") "RC0201FR-074K7L")
        (field (name "SPEC") "thick film +-1%, 1/20W, 0201")
      )
      (libsource (lib "eagle-import") (part "R-WIDER0201"))
    )
    (comp (ref "R3")
      (value "4.7K")
      (footprint "eagle-import:R0201")
      (fields
        (field (name "MANF") "Yageo")
        (field (name "MANF#") "RC0201FR-074K7L")
        (field (name "SPEC") "thick film +-1%, 1/20W, 0201")
      )
      (libsource (lib "eagle-import") (part "R-WIDER0201"))
    )
    (comp (ref "R4")
      (value "100")
      (footprint "eagle-import:R0402")
      (fields (field (name "MANF") "Yageo") (field (name "SPEC") "thick film +-1%, 1/16W, 0402"))
      (libsource (lib "eagle-import") (part "R-WIDER0402"))
    )
    (comp (ref "R5")
      (value "5.1K")
      (footprint "eagle-import:R0201")
      (fields (field (name "MANF") "Yageo") (field (name "SPEC") "thick film +-1%, 1/20W, 0201"))
      (libsource (lib "eagle-import") (part "R-US_R0201"))
    )
    (comp (ref "R8")
      (value "100")
      (footprint "eagle-import:R0402")
      (fields
        (field (name "MANF") "Yageo")
        (field (name "MANF#") "RC0402FR-07100RL")
        (field (name "SPEC") "thick film +-1%, 1/16W, 0402")
      )
      (libsource (lib "eagle-import") (part "R-WIDER0402"))
    )
    (comp (ref "R9")
      (value "100")
      (footprint "eagle-import:R0402")
      (fields
        (field (name "MANF") "Yageo")
        (field (name "MANF#") "RC0402FR-07100RL")
        (field (name "SPEC") "thick film +-1%, 1/16W, 0402")
      )
      (libsource (lib "eagle-import") (part "R-WIDER0402"))
    )
    (comp (ref "R18")
      (value "12K 1%")
      (footprint "eagle-import:R0402")
      (fields
        (field (name "MANF") "Yageo")
        (field (name "MANF#") "RC0402FR-0712KL")
        (field (name "NOTE") "Stays 0402 deliberately. Power is trivial (0.9 mW) and 1 percent is 1 percent at any size, but this is the FT2232's RREF -- it sets the USB transceiver bias current. There is no space pressure on this board any more, so there is nothing to gain against a part whose drift shows up as USB signal quality.")
        (field (name "SPEC") "thick film +-1%, 1/16W, 0402")
      )
      (libsource (lib "eagle-import") (part "R-US_SMALLR0402"))
    )
    (comp (ref "R19")
      (value "10K")
      (footprint "eagle-import:R0201")
      (fields
        (field (name "MANF") "Yageo")
        (field (name "MANF#") "RC0201FR-0710KL")
        (field (name "SPEC") "thick film +-1%, 1/20W, 0201")
      )
      (libsource (lib "eagle-import") (part "R-US_SMALLR0201"))
    )
    (comp (ref "R24")
      (value "33")
      (footprint "eagle-import:R0201")
      (fields
        (field (name "MANF") "Yageo")
        (field (name "MANF#") "RC0201FR-0733RL")
        (field (name "SPEC") "thick film +-1%, 1/20W, 0201")
      )
      (libsource (lib "eagle-import") (part "R-US_SMALLR0201"))
    )
    (comp (ref "R25")
      (value "33")
      (footprint "eagle-import:R0201")
      (fields
        (field (name "MANF") "Yageo")
        (field (name "MANF#") "RC0201FR-0733RL")
        (field (name "SPEC") "thick film +-1%, 1/20W, 0201")
      )
      (libsource (lib "eagle-import") (part "R-US_SMALLR0201"))
    )
    (comp (ref "R36")
      (value "100")
      (footprint "eagle-import:R0402")
      (fields
        (field (name "MANF") "Yageo")
        (field (name "MANF#") "RC0402FR-07100RL")
        (field (name "SPEC") "thick film +-1%, 1/16W, 0402")
      )
      (libsource (lib "eagle-import") (part "R-WIDER0402"))
    )
    (comp (ref "R37")
      (value "100")
      (footprint "eagle-import:R0402")
      (fields
        (field (name "MANF") "Yageo")
        (field (name "MANF#") "RC0402FR-07100RL")
        (field (name "SPEC") "thick film +-1%, 1/16W, 0402")
      )
      (libsource (lib "eagle-import") (part "R-WIDER0402"))
    )
    (comp (ref "R38")
      (value "100")
      (footprint "eagle-import:R0402")
      (fields
        (field (name "MANF") "Yageo")
        (field (name "MANF#") "RC0402FR-07100RL")
        (field (name "SPEC") "thick film +-1%, 1/16W, 0402")
      )
      (libsource (lib "eagle-import") (part "R-WIDER0402"))
    )
    (comp (ref "R89")
      (value "10K")
      (footprint "eagle-import:R0201")
      (fields
        (field (name "MANF") "Yageo")
        (field (name "MANF#") "RC0201FR-0710KL")
        (field (name "SPEC") "thick film +-1%, 1/20W, 0201")
      )
      (libsource (lib "eagle-import") (part "R-US_SMALLR0201"))
    )
    (comp (ref "R90")
      (value "10K")
      (footprint "eagle-import:R0201")
      (fields
        (field (name "MANF") "Yageo")
        (field (name "MANF#") "RC0201FR-0710KL")
        (field (name "SPEC") "thick film +-1%, 1/20W, 0201")
      )
      (libsource (lib "eagle-import") (part "R-US_SMALLR0201"))
    )
    (comp (ref "R91")
      (value "10K")
      (footprint "eagle-import:R0201")
      (fields
        (field (name "MANF") "Yageo")
        (field (name "MANF#") "RC0201FR-0710KL")
        (field (name "SPEC") "thick film +-1%, 1/20W, 0201")
      )
      (libsource (lib "eagle-import") (part "R-US_SMALLR0201"))
    )
    (comp (ref "R92")
      (value "10K")
      (footprint "eagle-import:R0201")
      (fields
        (field (name "MANF") "Yageo")
        (field (name "MANF#") "RC0201FR-0710KL")
        (field (name "SPEC") "thick film +-1%, 1/20W, 0201")
      )
      (libsource (lib "eagle-import") (part "R-US_SMALLR0201"))
    )
    (comp (ref "R93")
      (value "10K")
      (footprint "eagle-import:R0201")
      (fields
        (field (name "MANF") "Yageo")
        (field (name "MANF#") "RC0201FR-0710KL")
        (field (name "SPEC") "thick film +-1%, 1/20W, 0201")
      )
      (libsource (lib "eagle-import") (part "R-US_SMALLR0201"))
    )
    (comp (ref "R94")
      (value "10K")
      (footprint "eagle-import:R0201")
      (fields
        (field (name "MANF") "Yageo")
        (field (name "MANF#") "RC0201FR-0710KL")
        (field (name "SPEC") "thick film +-1%, 1/20W, 0201")
      )
      (libsource (lib "eagle-import") (part "R-US_SMALLR0201"))
    )
    (comp (ref "R96")
      (value "10k")
      (footprint "eagle-import:R0201")
      (fields
        (field (name "MANF") "Yageo")
        (field (name "MANF#") "RC0201FR-0710KL")
        (field (name "SPEC") "thick film +-1%, 1/20W, 0201")
      )
      (libsource (lib "eagle-import") (part "R-US_SMALLR0201"))
    )
    (comp (ref "R97")
      (value "10k")
      (footprint "eagle-import:R0201")
      (fields
        (field (name "MANF") "Yageo")
        (field (name "MANF#") "RC0201FR-0710KL")
        (field (name "SPEC") "thick film +-1%, 1/20W, 0201")
      )
      (libsource (lib "eagle-import") (part "R-US_SMALLR0201"))
    )
    (comp (ref "R98")
      (value "10k")
      (footprint "eagle-import:R0201")
      (fields
        (field (name "MANF") "Yageo")
        (field (name "MANF#") "RC0201FR-0710KL")
        (field (name "SPEC") "thick film +-1%, 1/20W, 0201")
      )
      (libsource (lib "eagle-import") (part "R-US_SMALLR0201"))
    )
    (comp (ref "R99")
      (value "4.7k")
      (footprint "eagle-import:R0201")
      (fields
        (field (name "MANF") "Yageo")
        (field (name "MANF#") "RC0201FR-074K7L")
        (field (name "SPEC") "thick film +-1%, 1/20W, 0201")
      )
      (libsource (lib "eagle-import") (part "R-US_SMALLR0201"))
    )
    (comp (ref "R100")
      (value "330")
      (footprint "eagle-import:R0402")
      (fields
        (field (name "MANF") "Yageo")
        (field (name "MANF#") "RC0402FR-07330RL")
        (field (name "NOTE") "Stays 0402 deliberately. At 330R holding DONE low through configuration it dissipates 3.3V^2/330 = 33 mW, which is 53 percent of an 0402's 1/16 W but 66 percent of an 0201's 1/20 W -- and it is sustained for the whole of config, indefinitely if config fails. 330R on DONE is standard Xilinx practice so the value should not change; the package is where the margin is.")
        (field (name "SPEC") "thick film +-1%, 1/16W, 0402")
      )
      (libsource (lib "eagle-import") (part "R-US_SMALLR0402"))
    )
    (comp (ref "R101")
      (value "2.21k")
      (footprint "eagle-import:R0201")
      (fields
        (field (name "MANF") "Yageo")
        (field (name "MANF#") "RC0201FR-072K21L")
        (field (name "SPEC") "thick film +-1%, 1/20W, 0201")
      )
      (libsource (lib "eagle-import") (part "R-US_SMALLR0201"))
    )
    (comp (ref "U2")
      (value "FT2232HQ USB-UART/JTAG Bridge")
      (footprint "eagle-import:FT2232HQ-QFN64")
      (fields
        (field (name "MANF") "FTDI")
        (field (name "MANF_1") "FTDI")
        (field (name "MANF#") "FT2232HQ-REEL")
      )
      (libsource (lib "eagle-import") (part "FT2232HQ-QFN64"))
    )
    (comp (ref "U10")
      (value "93LC46BT-I/SN")
      (footprint "eagle-import:SOIC8")
      (fields
        (field (name "MANF") "Microchip")
        (field (name "MANF_1") "Microchip")
        (field (name "MANF#") "93LC46BT-I/SN")
      )
      (libsource (lib "eagle-import") (part "EEPROM-93LC46B-I/SN"))
    )
    (comp (ref "C3")
      (value "0.1uF")
      (footprint "eagle-import:C0402")
      (fields
        (field (name "MANF") "Murata")
        (field (name "MANF#") "GRM155R71C104KA88D")
        (field (name "SPEC") "X7R 16V +-10%, 0.50 mm max")
      )
      (libsource (lib "eagle-import") (part "C-GENERICC0402"))
    )
    (comp (ref "C4")
      (value "0.1uF")
      (footprint "eagle-import:C0402")
      (fields
        (field (name "MANF") "Murata")
        (field (name "MANF#") "GRM155R71C104KA88D")
        (field (name "SPEC") "X7R 16V +-10%, 0.50 mm max")
      )
      (libsource (lib "eagle-import") (part "C-GENERICC0402"))
    )
    (comp (ref "C5")
      (value "0.1uF")
      (footprint "eagle-import:C0402")
      (fields
        (field (name "MANF") "Murata")
        (field (name "MANF#") "GRM155R71C104KA88D")
        (field (name "SPEC") "X7R 16V +-10%, 0.50 mm max")
      )
      (libsource (lib "eagle-import") (part "C-GENERICC0402"))
    )
    (comp (ref "C6")
      (value "0.1uF")
      (footprint "eagle-import:C0402")
      (fields
        (field (name "MANF") "Murata")
        (field (name "MANF#") "GRM155R71C104KA88D")
        (field (name "SPEC") "X7R 16V +-10%, 0.50 mm max")
      )
      (libsource (lib "eagle-import") (part "C-GENERICC0402"))
    )
    (comp (ref "C7")
      (value "0.1uF")
      (footprint "eagle-import:C0402")
      (fields
        (field (name "MANF") "Murata")
        (field (name "MANF#") "GRM155R71C104KA88D")
        (field (name "SPEC") "X7R 16V +-10%, 0.50 mm max")
      )
      (libsource (lib "eagle-import") (part "C-GENERICC0402"))
    )
    (comp (ref "C8")
      (value "0.1uF")
      (footprint "eagle-import:C0402")
      (fields
        (field (name "MANF") "Murata")
        (field (name "MANF#") "GRM155R71C104KA88D")
        (field (name "SPEC") "X7R 16V +-10%, 0.50 mm max")
      )
      (libsource (lib "eagle-import") (part "C-GENERICC0402"))
    )
    (comp (ref "C9")
      (value "0.1uF")
      (footprint "eagle-import:C0402")
      (fields
        (field (name "MANF") "Murata")
        (field (name "MANF#") "GRM155R71C104KA88D")
        (field (name "SPEC") "X7R 16V +-10%, 0.50 mm max")
      )
      (libsource (lib "eagle-import") (part "C-GENERICC0402"))
    )
    (comp (ref "C11")
      (value "0.1uF")
      (footprint "eagle-import:C0402")
      (fields
        (field (name "MANF") "Murata")
        (field (name "MANF#") "GRM155R71C104KA88D")
        (field (name "SPEC") "X7R 16V +-10%, 0.50 mm max")
      )
      (libsource (lib "eagle-import") (part "C-GENERICC0402"))
    )
    (comp (ref "C12")
      (value "0.1uF")
      (footprint "eagle-import:C0402")
      (fields
        (field (name "MANF") "Murata")
        (field (name "MANF#") "GRM155R71C104KA88D")
        (field (name "SPEC") "X7R 16V +-10%, 0.50 mm max")
      )
      (libsource (lib "eagle-import") (part "C-GENERICC0402"))
    )
    (comp (ref "C13")
      (value "10uF")
      (footprint "eagle-import:C0603")
      (fields
        (field (name "MANF") "Murata")
        (field (name "MANF#") "GRM188R60J106ME47D")
        (field (name "SPEC") "X5R 6.3V +-20%, 0.90 mm max")
      )
      (libsource (lib "eagle-import") (part "C-GENERICC0603"))
    )
    (comp (ref "R2")
      (value "4.7K")
      (footprint "eagle-import:R0201")
      (fields
        (field (name "MANF") "Yageo")
        (field (name "MANF#") "RC0201FR-074K7L")
        (field (name "SPEC") "thick film +-1%, 1/20W, 0201")
      )
      (libsource (lib "eagle-import") (part "R-WIDER0201"))
    )
    (comp (ref "R6")
      (value "4.7K")
      (footprint "eagle-import:R0201")
      (fields
        (field (name "MANF") "Yageo")
        (field (name "MANF#") "RC0201FR-074K7L")
        (field (name "SPEC") "thick film +-1%, 1/20W, 0201")
      )
      (libsource (lib "eagle-import") (part "R-WIDER0201"))
    )
    (comp (ref "R7")
      (value "4.7K")
      (footprint "eagle-import:R0201")
      (fields
        (field (name "MANF") "Yageo")
        (field (name "MANF#") "RC0201FR-074K7L")
        (field (name "SPEC") "thick film +-1%, 1/20W, 0201")
      )
      (libsource (lib "eagle-import") (part "R-WIDER0201"))
    )
    (comp (ref "R34")
      (value "4.7K")
      (footprint "eagle-import:742C083")
      (fields
        (field (name "MANF") "CTS Resistor Products")
        (field (name "MANF_1") "CTS")
        (field (name "MANF#") "742C083472JTR")
        (field (name "NOTE") "The microSD DAT0-3 pull-ups, all four elements used -- which is what an array is actually for, unlike R1, R2 and R4, which used 2, 3 and 6 of theirs and were split into discretes. This one stays an array. 4.7k is the conventional value for SD data lines and it was already chosen; only the part number was missing. 5 percent is ample for a pull-up, so this is a J part where the discrete resistors on this board are F. CTS 742C is the family the footprint is named after. Confirm the suffix -- it encodes tolerance and packaging and is the easy thing to get wrong.")
        (field (name "SPEC") "4-element isolated resistor array, 4.7k, 5 percent or better, 742C083 8-pin convex land")
      )
      (libsource (lib "eagle-import") (part "RES4742"))
    )
    (comp (ref "R35")
      (value "4.7K")
      (footprint "eagle-import:R0402")
      (fields
        (field (name "MANF") "Yageo")
        (field (name "MANF#") "RC0402FR-074K7L")
        (field (name "SPEC") "thick film +-1%, 1/16W, 0402")
      )
      (libsource (lib "eagle-import") (part "R-US_R0402"))
    )
    (comp (ref "U3")
      (value "AS4C32M16SB-6TIN")
      (footprint "eagle-import:TSOPII-54")
      (fields
        (field (name "MANF") "Alliance Memory")
        (field (name "MANF_1") "Alliance Memory")
        (field (name "MANF#") "AS4C32M16SB-6TIN")
        (field (name "NOTE") "512Mbit (32M x 16) = 64MB. Pin-for-pin and dimensionally identical to the 256Mb AS4C16M16SA-6TIN it replaces: all 54 pins and every TSOP-II dimension were checked against both datasheets, and pin 40 is NC on both. ONE DIFFERENCE, AND IT IS NOT A PIN -- the column address is A0-A9 (1024 columns) instead of A0-A8 (512). The memory controller must be set to 10 column bits or it reaches only half the array. Row A0-A12, banks BA0/BA1 and refresh (8192 cycles/64ms) are unchanged. IDD1 rises 60mA to 120mA on the 600mA VCC3V3 buck (LTC3569 SW3).")
      )
      (libsource (lib "eagle-import") (part "SDRAM-X16-ALLIANCE-512M"))
    )
    (comp (ref "U4")
      (value "W25Q128JVSIQ")
      (footprint "eagle-import:SOIC-8_208MIL")
      (fields
        (field (name "MANF") "Winbond")
        (field (name "DIGIKEY#") "W25Q128JVSIQ-ND")
        (field (name "MANF_1") "Winbond")
        (field (name "MANF#") "W25Q128JVSIQ")
        (field (name "NOTE") "128Mbit quad SPI, SOIC-8 208mil. The XC7A35T bitstream is 17,536,096 bits, so the previous W25Q80BV (8Mbit) could not boot the part at all. 128Mbit leaves ~14MB for user data above the bitstream.")
      )
      (libsource (lib "eagle-import") (part "SPI_FLASH-SOIC_150_208"))
    )
    (comp (ref "X3")
      (value "MICROSD_CONDM3AT-SF-PEJM5")
      (footprint "eagle-import:DM3AT-SF-PEJM5")
      (fields
        (field (name "MANF") "Hirose")
        (field (name "MANF_1") "Hirose")
        (field (name "MANF#") "DM3AT-SF-PEJM5")
      )
      (libsource (lib "eagle-import") (part "MICROSD_CONDM3AT-SF-PEJM5"))
    )
    (comp (ref "C123")
      (value "100nF")
      (footprint "eagle-import:C0402")
      (fields
        (field (name "MANF") "Murata")
        (field (name "MANF#") "GRM155R71C104KA88D")
        (field (name "SPEC") "X7R 16V +-10%, 0.50 mm max -- same part as the 0.1uF line")
      )
      (libsource (lib "eagle-import") (part "C-USC0402"))
    )
    (comp (ref "C124")
      (value "470nF")
      (footprint "eagle-import:C0402")
      (fields
        (field (name "MANF") "Murata")
        (field (name "MANF#") "GRM155R61C474KA88D")
        (field (name "SPEC") "X5R 16V +-10%, 0.50 mm max -- same part as the 0.47uF line")
      )
      (libsource (lib "eagle-import") (part "C-USC0402"))
    )
    (comp (ref "L6")
      (value "FB 600R@100MHz")
      (footprint "eagle-import:IND0603")
      (fields
        (field (name "MANF") "Murata")
        (field (name "MANF#") "BLM18PG601SN1D")
        (field (name "SPEC") "600 ohm at 100MHz, 1.5A, 0.90 mm max")
      )
      (libsource (lib "eagle-import") (part "INDUCTOR"))
    )
    (comp (ref "L7")
      (value "FB 600R@100MHz")
      (footprint "eagle-import:IND0603")
      (fields
        (field (name "MANF") "Murata")
        (field (name "MANF#") "BLM18PG601SN1D")
        (field (name "SPEC") "600 ohm at 100MHz, 1.5A, 0.90 mm max")
      )
      (libsource (lib "eagle-import") (part "INDUCTOR"))
    )
    (comp (ref "R20")
      (value "1K")
      (footprint "eagle-import:R0402")
      (fields
        (field (name "MANF") "Yageo")
        (field (name "MANF#") "RC0402FR-071KL")
        (field (name "SPEC") "thick film +-1%, 1/16W, 0402")
      )
      (libsource (lib "eagle-import") (part "R-US_SMALLR0402"))
    )
    (comp (ref "R21")
      (value "1K")
      (footprint "eagle-import:R0402")
      (fields
        (field (name "MANF") "Yageo")
        (field (name "MANF#") "RC0402FR-071KL")
        (field (name "SPEC") "thick film +-1%, 1/16W, 0402")
      )
      (libsource (lib "eagle-import") (part "R-US_SMALLR0402"))
    )
    (comp (ref "R22")
      (value "1K")
      (footprint "eagle-import:R0402")
      (fields
        (field (name "MANF") "Yageo")
        (field (name "MANF#") "RC0402FR-071KL")
        (field (name "SPEC") "thick film +-1%, 1/16W, 0402")
      )
      (libsource (lib "eagle-import") (part "R-US_SMALLR0402"))
    )
    (comp (ref "R23")
      (value "1K")
      (footprint "eagle-import:R0402")
      (fields
        (field (name "MANF") "Yageo")
        (field (name "MANF#") "RC0402FR-071KL")
        (field (name "SPEC") "thick film +-1%, 1/16W, 0402")
      )
      (libsource (lib "eagle-import") (part "R-US_SMALLR0402"))
    )
    (comp (ref "U1")
      (value "XC7A35T-1CPG236C")
      (footprint "eagle-import:XC7A35T-CPG236")
      (fields
        (field (name "MANF") "AMD/Xilinx")
        (field (name "MANF_1") "AMD/Xilinx")
        (field (name "MANF#") "XC7A35T-1CPG236C")
        (field (name "MANF#_1") "XC7A35T-1CPG236C")
      )
      (libsource (lib "eagle-import") (part "XC7A35T-CPG236-1CPG236C"))
    )
    (comp (ref "C85")
      (value "22uF")
      (footprint "eagle-import:C0805")
      (fields
        (field (name "MANF") "Murata")
        (field (name "MANF#") "GRM21BR61A226ME44L")
        (field (name "SPEC") "X5R 10V +-20%, 1.45 mm max")
      )
      (libsource (lib "eagle-import") (part "C-USC0805"))
    )
    (comp (ref "C86")
      (value "22uF")
      (footprint "eagle-import:C0805")
      (fields
        (field (name "MANF") "Murata")
        (field (name "MANF#") "GRM21BR61A226ME44L")
        (field (name "SPEC") "X5R 10V +-20%, 1.45 mm max")
      )
      (libsource (lib "eagle-import") (part "C-USC0805"))
    )
    (comp (ref "C87")
      (value "4.7uF")
      (footprint "eagle-import:C0603")
      (fields
        (field (name "MANF") "Murata")
        (field (name "MANF#") "GRM188R61A475KE15D")
        (field (name "SPEC") "X5R 10V +-10%, 0.90 mm max")
      )
      (libsource (lib "eagle-import") (part "C-USC0603"))
    )
    (comp (ref "C88")
      (value "4.7uF")
      (footprint "eagle-import:C0603")
      (fields
        (field (name "MANF") "Murata")
        (field (name "MANF#") "GRM188R61A475KE15D")
        (field (name "SPEC") "X5R 10V +-10%, 0.90 mm max")
      )
      (libsource (lib "eagle-import") (part "C-USC0603"))
    )
    (comp (ref "C89")
      (value "0.47uF")
      (footprint "eagle-import:C0201")
      (fields
        (field (name "MANF") "Murata")
        (field (name "MANF#") "GRM033R60J474KE15D")
        (field (name "NOTE") "0402 -> 0201 to cut ESL, following Cmod A7. THE VOLTAGE RATING DROPS 16V to 6.3V and that costs real capacitance: on VCC3V3 a 6.3V 0201 sits at 52 percent of rating and DC bias typically removes 60-75 percent of it, against 15-25 percent for the 16V 0402 it replaces. The BOM value is unchanged, so validate.py's UG483 count still passes -- it counts nominal values and cannot see bias derating. Effective decoupling on 3V3 is roughly half what it was. Confirm the MPN suffix and the bias curve against Murata's data before ordering.")
        (field (name "SPEC") "X5R 6.3V +-10%, 0.30 mm max")
      )
      (libsource (lib "eagle-import") (part "C-USC0201"))
    )
    (comp (ref "C90")
      (value "0.47uF")
      (footprint "eagle-import:C0201")
      (fields
        (field (name "MANF") "Murata")
        (field (name "MANF#") "GRM033R60J474KE15D")
        (field (name "NOTE") "0402 -> 0201 to cut ESL, following Cmod A7. THE VOLTAGE RATING DROPS 16V to 6.3V and that costs real capacitance: on VCC3V3 a 6.3V 0201 sits at 52 percent of rating and DC bias typically removes 60-75 percent of it, against 15-25 percent for the 16V 0402 it replaces. The BOM value is unchanged, so validate.py's UG483 count still passes -- it counts nominal values and cannot see bias derating. Effective decoupling on 3V3 is roughly half what it was. Confirm the MPN suffix and the bias curve against Murata's data before ordering.")
        (field (name "SPEC") "X5R 6.3V +-10%, 0.30 mm max")
      )
      (libsource (lib "eagle-import") (part "C-USC0201"))
    )
    (comp (ref "C91")
      (value "0.47uF")
      (footprint "eagle-import:C0201")
      (fields
        (field (name "MANF") "Murata")
        (field (name "MANF#") "GRM033R60J474KE15D")
        (field (name "NOTE") "0402 -> 0201 to cut ESL, following Cmod A7. THE VOLTAGE RATING DROPS 16V to 6.3V and that costs real capacitance: on VCC3V3 a 6.3V 0201 sits at 52 percent of rating and DC bias typically removes 60-75 percent of it, against 15-25 percent for the 16V 0402 it replaces. The BOM value is unchanged, so validate.py's UG483 count still passes -- it counts nominal values and cannot see bias derating. Effective decoupling on 3V3 is roughly half what it was. Confirm the MPN suffix and the bias curve against Murata's data before ordering.")
        (field (name "SPEC") "X5R 6.3V +-10%, 0.30 mm max")
      )
      (libsource (lib "eagle-import") (part "C-USC0201"))
    )
    (comp (ref "C92")
      (value "0.47uF")
      (footprint "eagle-import:C0201")
      (fields
        (field (name "MANF") "Murata")
        (field (name "MANF#") "GRM033R60J474KE15D")
        (field (name "NOTE") "0402 -> 0201 to cut ESL, following Cmod A7. THE VOLTAGE RATING DROPS 16V to 6.3V and that costs real capacitance: on VCC3V3 a 6.3V 0201 sits at 52 percent of rating and DC bias typically removes 60-75 percent of it, against 15-25 percent for the 16V 0402 it replaces. The BOM value is unchanged, so validate.py's UG483 count still passes -- it counts nominal values and cannot see bias derating. Effective decoupling on 3V3 is roughly half what it was. Confirm the MPN suffix and the bias curve against Murata's data before ordering.")
        (field (name "SPEC") "X5R 6.3V +-10%, 0.30 mm max")
      )
      (libsource (lib "eagle-import") (part "C-USC0201"))
    )
    (comp (ref "C93")
      (value "22uF")
      (footprint "eagle-import:C0805")
      (fields
        (field (name "MANF") "Murata")
        (field (name "MANF#") "GRM21BR61A226ME44L")
        (field (name "SPEC") "X5R 10V +-20%, 1.45 mm max")
      )
      (libsource (lib "eagle-import") (part "C-USC0805"))
    )
    (comp (ref "C94")
      (value "4.7uF")
      (footprint "eagle-import:C0603")
      (fields
        (field (name "MANF") "Murata")
        (field (name "MANF#") "GRM188R61A475KE15D")
        (field (name "SPEC") "X5R 10V +-10%, 0.90 mm max")
      )
      (libsource (lib "eagle-import") (part "C-USC0603"))
    )
    (comp (ref "C95")
      (value "0.47uF")
      (footprint "eagle-import:C0201")
      (fields
        (field (name "MANF") "Murata")
        (field (name "MANF#") "GRM033R60J474KE15D")
        (field (name "NOTE") "0402 -> 0201 to cut ESL, following Cmod A7. THE VOLTAGE RATING DROPS 16V to 6.3V and that costs real capacitance: on VCC3V3 a 6.3V 0201 sits at 52 percent of rating and DC bias typically removes 60-75 percent of it, against 15-25 percent for the 16V 0402 it replaces. The BOM value is unchanged, so validate.py's UG483 count still passes -- it counts nominal values and cannot see bias derating. Effective decoupling on 3V3 is roughly half what it was. Confirm the MPN suffix and the bias curve against Murata's data before ordering.")
        (field (name "SPEC") "X5R 6.3V +-10%, 0.30 mm max")
      )
      (libsource (lib "eagle-import") (part "C-USC0201"))
    )
    (comp (ref "C96")
      (value "0.47uF")
      (footprint "eagle-import:C0201")
      (fields
        (field (name "MANF") "Murata")
        (field (name "MANF#") "GRM033R60J474KE15D")
        (field (name "NOTE") "0402 -> 0201 to cut ESL, following Cmod A7. THE VOLTAGE RATING DROPS 16V to 6.3V and that costs real capacitance: on VCC3V3 a 6.3V 0201 sits at 52 percent of rating and DC bias typically removes 60-75 percent of it, against 15-25 percent for the 16V 0402 it replaces. The BOM value is unchanged, so validate.py's UG483 count still passes -- it counts nominal values and cannot see bias derating. Effective decoupling on 3V3 is roughly half what it was. Confirm the MPN suffix and the bias curve against Murata's data before ordering.")
        (field (name "SPEC") "X5R 6.3V +-10%, 0.30 mm max")
      )
      (libsource (lib "eagle-import") (part "C-USC0201"))
    )
    (comp (ref "C97")
      (value "22uF")
      (footprint "eagle-import:C0805")
      (fields
        (field (name "MANF") "Murata")
        (field (name "MANF#") "GRM21BR61A226ME44L")
        (field (name "SPEC") "X5R 10V +-20%, 1.45 mm max")
      )
      (libsource (lib "eagle-import") (part "C-USC0805"))
    )
    (comp (ref "C98")
      (value "22uF")
      (footprint "eagle-import:C0805")
      (fields
        (field (name "MANF") "Murata")
        (field (name "MANF#") "GRM21BR61A226ME44L")
        (field (name "SPEC") "X5R 10V +-20%, 1.45 mm max")
      )
      (libsource (lib "eagle-import") (part "C-USC0805"))
    )
    (comp (ref "C99")
      (value "4.7uF")
      (footprint "eagle-import:C0603")
      (fields
        (field (name "MANF") "Murata")
        (field (name "MANF#") "GRM188R61A475KE15D")
        (field (name "SPEC") "X5R 10V +-10%, 0.90 mm max")
      )
      (libsource (lib "eagle-import") (part "C-USC0603"))
    )
    (comp (ref "C100")
      (value "4.7uF")
      (footprint "eagle-import:C0603")
      (fields
        (field (name "MANF") "Murata")
        (field (name "MANF#") "GRM188R61A475KE15D")
        (field (name "SPEC") "X5R 10V +-10%, 0.90 mm max")
      )
      (libsource (lib "eagle-import") (part "C-USC0603"))
    )
    (comp (ref "C101")
      (value "4.7uF")
      (footprint "eagle-import:C0603")
      (fields
        (field (name "MANF") "Murata")
        (field (name "MANF#") "GRM188R61A475KE15D")
        (field (name "SPEC") "X5R 10V +-10%, 0.90 mm max")
      )
      (libsource (lib "eagle-import") (part "C-USC0603"))
    )
    (comp (ref "C102")
      (value "4.7uF")
      (footprint "eagle-import:C0603")
      (fields
        (field (name "MANF") "Murata")
        (field (name "MANF#") "GRM188R61A475KE15D")
        (field (name "SPEC") "X5R 10V +-10%, 0.90 mm max")
      )
      (libsource (lib "eagle-import") (part "C-USC0603"))
    )
    (comp (ref "C103")
      (value "4.7uF")
      (footprint "eagle-import:C0603")
      (fields
        (field (name "MANF") "Murata")
        (field (name "MANF#") "GRM188R61A475KE15D")
        (field (name "SPEC") "X5R 10V +-10%, 0.90 mm max")
      )
      (libsource (lib "eagle-import") (part "C-USC0603"))
    )
    (comp (ref "C104")
      (value "4.7uF")
      (footprint "eagle-import:C0603")
      (fields
        (field (name "MANF") "Murata")
        (field (name "MANF#") "GRM188R61A475KE15D")
        (field (name "SPEC") "X5R 10V +-10%, 0.90 mm max")
      )
      (libsource (lib "eagle-import") (part "C-USC0603"))
    )
    (comp (ref "C105")
      (value "4.7uF")
      (footprint "eagle-import:C0603")
      (fields
        (field (name "MANF") "Murata")
        (field (name "MANF#") "GRM188R61A475KE15D")
        (field (name "SPEC") "X5R 10V +-10%, 0.90 mm max")
      )
      (libsource (lib "eagle-import") (part "C-USC0603"))
    )
    (comp (ref "C106")
      (value "4.7uF")
      (footprint "eagle-import:C0603")
      (fields
        (field (name "MANF") "Murata")
        (field (name "MANF#") "GRM188R61A475KE15D")
        (field (name "SPEC") "X5R 10V +-10%, 0.90 mm max")
      )
      (libsource (lib "eagle-import") (part "C-USC0603"))
    )
    (comp (ref "C107")
      (value "0.47uF")
      (footprint "eagle-import:C0201")
      (fields
        (field (name "MANF") "Murata")
        (field (name "MANF#") "GRM033R60J474KE15D")
        (field (name "NOTE") "0402 -> 0201 to cut ESL, following Cmod A7. THE VOLTAGE RATING DROPS 16V to 6.3V and that costs real capacitance: on VCC3V3 a 6.3V 0201 sits at 52 percent of rating and DC bias typically removes 60-75 percent of it, against 15-25 percent for the 16V 0402 it replaces. The BOM value is unchanged, so validate.py's UG483 count still passes -- it counts nominal values and cannot see bias derating. Effective decoupling on 3V3 is roughly half what it was. Confirm the MPN suffix and the bias curve against Murata's data before ordering.")
        (field (name "SPEC") "X5R 6.3V +-10%, 0.30 mm max")
      )
      (libsource (lib "eagle-import") (part "C-USC0201"))
    )
    (comp (ref "C108")
      (value "0.47uF")
      (footprint "eagle-import:C0201")
      (fields
        (field (name "MANF") "Murata")
        (field (name "MANF#") "GRM033R60J474KE15D")
        (field (name "NOTE") "0402 -> 0201 to cut ESL, following Cmod A7. THE VOLTAGE RATING DROPS 16V to 6.3V and that costs real capacitance: on VCC3V3 a 6.3V 0201 sits at 52 percent of rating and DC bias typically removes 60-75 percent of it, against 15-25 percent for the 16V 0402 it replaces. The BOM value is unchanged, so validate.py's UG483 count still passes -- it counts nominal values and cannot see bias derating. Effective decoupling on 3V3 is roughly half what it was. Confirm the MPN suffix and the bias curve against Murata's data before ordering.")
        (field (name "SPEC") "X5R 6.3V +-10%, 0.30 mm max")
      )
      (libsource (lib "eagle-import") (part "C-USC0201"))
    )
    (comp (ref "C109")
      (value "0.47uF")
      (footprint "eagle-import:C0201")
      (fields
        (field (name "MANF") "Murata")
        (field (name "MANF#") "GRM033R60J474KE15D")
        (field (name "NOTE") "0402 -> 0201 to cut ESL, following Cmod A7. THE VOLTAGE RATING DROPS 16V to 6.3V and that costs real capacitance: on VCC3V3 a 6.3V 0201 sits at 52 percent of rating and DC bias typically removes 60-75 percent of it, against 15-25 percent for the 16V 0402 it replaces. The BOM value is unchanged, so validate.py's UG483 count still passes -- it counts nominal values and cannot see bias derating. Effective decoupling on 3V3 is roughly half what it was. Confirm the MPN suffix and the bias curve against Murata's data before ordering.")
        (field (name "SPEC") "X5R 6.3V +-10%, 0.30 mm max")
      )
      (libsource (lib "eagle-import") (part "C-USC0201"))
    )
    (comp (ref "C110")
      (value "0.47uF")
      (footprint "eagle-import:C0201")
      (fields
        (field (name "MANF") "Murata")
        (field (name "MANF#") "GRM033R60J474KE15D")
        (field (name "NOTE") "0402 -> 0201 to cut ESL, following Cmod A7. THE VOLTAGE RATING DROPS 16V to 6.3V and that costs real capacitance: on VCC3V3 a 6.3V 0201 sits at 52 percent of rating and DC bias typically removes 60-75 percent of it, against 15-25 percent for the 16V 0402 it replaces. The BOM value is unchanged, so validate.py's UG483 count still passes -- it counts nominal values and cannot see bias derating. Effective decoupling on 3V3 is roughly half what it was. Confirm the MPN suffix and the bias curve against Murata's data before ordering.")
        (field (name "SPEC") "X5R 6.3V +-10%, 0.30 mm max")
      )
      (libsource (lib "eagle-import") (part "C-USC0201"))
    )
    (comp (ref "C111")
      (value "0.47uF")
      (footprint "eagle-import:C0201")
      (fields
        (field (name "MANF") "Murata")
        (field (name "MANF#") "GRM033R60J474KE15D")
        (field (name "NOTE") "0402 -> 0201 to cut ESL, following Cmod A7. THE VOLTAGE RATING DROPS 16V to 6.3V and that costs real capacitance: on VCC3V3 a 6.3V 0201 sits at 52 percent of rating and DC bias typically removes 60-75 percent of it, against 15-25 percent for the 16V 0402 it replaces. The BOM value is unchanged, so validate.py's UG483 count still passes -- it counts nominal values and cannot see bias derating. Effective decoupling on 3V3 is roughly half what it was. Confirm the MPN suffix and the bias curve against Murata's data before ordering.")
        (field (name "SPEC") "X5R 6.3V +-10%, 0.30 mm max")
      )
      (libsource (lib "eagle-import") (part "C-USC0201"))
    )
    (comp (ref "C112")
      (value "0.47uF")
      (footprint "eagle-import:C0201")
      (fields
        (field (name "MANF") "Murata")
        (field (name "MANF#") "GRM033R60J474KE15D")
        (field (name "NOTE") "0402 -> 0201 to cut ESL, following Cmod A7. THE VOLTAGE RATING DROPS 16V to 6.3V and that costs real capacitance: on VCC3V3 a 6.3V 0201 sits at 52 percent of rating and DC bias typically removes 60-75 percent of it, against 15-25 percent for the 16V 0402 it replaces. The BOM value is unchanged, so validate.py's UG483 count still passes -- it counts nominal values and cannot see bias derating. Effective decoupling on 3V3 is roughly half what it was. Confirm the MPN suffix and the bias curve against Murata's data before ordering.")
        (field (name "SPEC") "X5R 6.3V +-10%, 0.30 mm max")
      )
      (libsource (lib "eagle-import") (part "C-USC0201"))
    )
    (comp (ref "C113")
      (value "0.47uF")
      (footprint "eagle-import:C0201")
      (fields
        (field (name "MANF") "Murata")
        (field (name "MANF#") "GRM033R60J474KE15D")
        (field (name "NOTE") "0402 -> 0201 to cut ESL, following Cmod A7. THE VOLTAGE RATING DROPS 16V to 6.3V and that costs real capacitance: on VCC3V3 a 6.3V 0201 sits at 52 percent of rating and DC bias typically removes 60-75 percent of it, against 15-25 percent for the 16V 0402 it replaces. The BOM value is unchanged, so validate.py's UG483 count still passes -- it counts nominal values and cannot see bias derating. Effective decoupling on 3V3 is roughly half what it was. Confirm the MPN suffix and the bias curve against Murata's data before ordering.")
        (field (name "SPEC") "X5R 6.3V +-10%, 0.30 mm max")
      )
      (libsource (lib "eagle-import") (part "C-USC0201"))
    )
    (comp (ref "C114")
      (value "0.47uF")
      (footprint "eagle-import:C0201")
      (fields
        (field (name "MANF") "Murata")
        (field (name "MANF#") "GRM033R60J474KE15D")
        (field (name "NOTE") "0402 -> 0201 to cut ESL, following Cmod A7. THE VOLTAGE RATING DROPS 16V to 6.3V and that costs real capacitance: on VCC3V3 a 6.3V 0201 sits at 52 percent of rating and DC bias typically removes 60-75 percent of it, against 15-25 percent for the 16V 0402 it replaces. The BOM value is unchanged, so validate.py's UG483 count still passes -- it counts nominal values and cannot see bias derating. Effective decoupling on 3V3 is roughly half what it was. Confirm the MPN suffix and the bias curve against Murata's data before ordering.")
        (field (name "SPEC") "X5R 6.3V +-10%, 0.30 mm max")
      )
      (libsource (lib "eagle-import") (part "C-USC0201"))
    )
    (comp (ref "C115")
      (value "0.47uF")
      (footprint "eagle-import:C0201")
      (fields
        (field (name "MANF") "Murata")
        (field (name "MANF#") "GRM033R60J474KE15D")
        (field (name "NOTE") "0402 -> 0201 to cut ESL, following Cmod A7. THE VOLTAGE RATING DROPS 16V to 6.3V and that costs real capacitance: on VCC3V3 a 6.3V 0201 sits at 52 percent of rating and DC bias typically removes 60-75 percent of it, against 15-25 percent for the 16V 0402 it replaces. The BOM value is unchanged, so validate.py's UG483 count still passes -- it counts nominal values and cannot see bias derating. Effective decoupling on 3V3 is roughly half what it was. Confirm the MPN suffix and the bias curve against Murata's data before ordering.")
        (field (name "SPEC") "X5R 6.3V +-10%, 0.30 mm max")
      )
      (libsource (lib "eagle-import") (part "C-USC0201"))
    )
    (comp (ref "C116")
      (value "0.47uF")
      (footprint "eagle-import:C0201")
      (fields
        (field (name "MANF") "Murata")
        (field (name "MANF#") "GRM033R60J474KE15D")
        (field (name "NOTE") "0402 -> 0201 to cut ESL, following Cmod A7. THE VOLTAGE RATING DROPS 16V to 6.3V and that costs real capacitance: on VCC3V3 a 6.3V 0201 sits at 52 percent of rating and DC bias typically removes 60-75 percent of it, against 15-25 percent for the 16V 0402 it replaces. The BOM value is unchanged, so validate.py's UG483 count still passes -- it counts nominal values and cannot see bias derating. Effective decoupling on 3V3 is roughly half what it was. Confirm the MPN suffix and the bias curve against Murata's data before ordering.")
        (field (name "SPEC") "X5R 6.3V +-10%, 0.30 mm max")
      )
      (libsource (lib "eagle-import") (part "C-USC0201"))
    )
    (comp (ref "C117")
      (value "0.47uF")
      (footprint "eagle-import:C0201")
      (fields
        (field (name "MANF") "Murata")
        (field (name "MANF#") "GRM033R60J474KE15D")
        (field (name "NOTE") "0402 -> 0201 to cut ESL, following Cmod A7. THE VOLTAGE RATING DROPS 16V to 6.3V and that costs real capacitance: on VCC3V3 a 6.3V 0201 sits at 52 percent of rating and DC bias typically removes 60-75 percent of it, against 15-25 percent for the 16V 0402 it replaces. The BOM value is unchanged, so validate.py's UG483 count still passes -- it counts nominal values and cannot see bias derating. Effective decoupling on 3V3 is roughly half what it was. Confirm the MPN suffix and the bias curve against Murata's data before ordering.")
        (field (name "SPEC") "X5R 6.3V +-10%, 0.30 mm max")
      )
      (libsource (lib "eagle-import") (part "C-USC0201"))
    )
    (comp (ref "C118")
      (value "0.47uF")
      (footprint "eagle-import:C0201")
      (fields
        (field (name "MANF") "Murata")
        (field (name "MANF#") "GRM033R60J474KE15D")
        (field (name "NOTE") "0402 -> 0201 to cut ESL, following Cmod A7. THE VOLTAGE RATING DROPS 16V to 6.3V and that costs real capacitance: on VCC3V3 a 6.3V 0201 sits at 52 percent of rating and DC bias typically removes 60-75 percent of it, against 15-25 percent for the 16V 0402 it replaces. The BOM value is unchanged, so validate.py's UG483 count still passes -- it counts nominal values and cannot see bias derating. Effective decoupling on 3V3 is roughly half what it was. Confirm the MPN suffix and the bias curve against Murata's data before ordering.")
        (field (name "SPEC") "X5R 6.3V +-10%, 0.30 mm max")
      )
      (libsource (lib "eagle-import") (part "C-USC0201"))
    )
    (comp (ref "C119")
      (value "0.47uF")
      (footprint "eagle-import:C0201")
      (fields
        (field (name "MANF") "Murata")
        (field (name "MANF#") "GRM033R60J474KE15D")
        (field (name "NOTE") "0402 -> 0201 to cut ESL, following Cmod A7. THE VOLTAGE RATING DROPS 16V to 6.3V and that costs real capacitance: on VCC3V3 a 6.3V 0201 sits at 52 percent of rating and DC bias typically removes 60-75 percent of it, against 15-25 percent for the 16V 0402 it replaces. The BOM value is unchanged, so validate.py's UG483 count still passes -- it counts nominal values and cannot see bias derating. Effective decoupling on 3V3 is roughly half what it was. Confirm the MPN suffix and the bias curve against Murata's data before ordering.")
        (field (name "SPEC") "X5R 6.3V +-10%, 0.30 mm max")
      )
      (libsource (lib "eagle-import") (part "C-USC0201"))
    )
    (comp (ref "C120")
      (value "0.47uF")
      (footprint "eagle-import:C0201")
      (fields
        (field (name "MANF") "Murata")
        (field (name "MANF#") "GRM033R60J474KE15D")
        (field (name "NOTE") "0402 -> 0201 to cut ESL, following Cmod A7. THE VOLTAGE RATING DROPS 16V to 6.3V and that costs real capacitance: on VCC3V3 a 6.3V 0201 sits at 52 percent of rating and DC bias typically removes 60-75 percent of it, against 15-25 percent for the 16V 0402 it replaces. The BOM value is unchanged, so validate.py's UG483 count still passes -- it counts nominal values and cannot see bias derating. Effective decoupling on 3V3 is roughly half what it was. Confirm the MPN suffix and the bias curve against Murata's data before ordering.")
        (field (name "SPEC") "X5R 6.3V +-10%, 0.30 mm max")
      )
      (libsource (lib "eagle-import") (part "C-USC0201"))
    )
    (comp (ref "C121")
      (value "0.47uF")
      (footprint "eagle-import:C0201")
      (fields
        (field (name "MANF") "Murata")
        (field (name "MANF#") "GRM033R60J474KE15D")
        (field (name "NOTE") "0402 -> 0201 to cut ESL, following Cmod A7. THE VOLTAGE RATING DROPS 16V to 6.3V and that costs real capacitance: on VCC3V3 a 6.3V 0201 sits at 52 percent of rating and DC bias typically removes 60-75 percent of it, against 15-25 percent for the 16V 0402 it replaces. The BOM value is unchanged, so validate.py's UG483 count still passes -- it counts nominal values and cannot see bias derating. Effective decoupling on 3V3 is roughly half what it was. Confirm the MPN suffix and the bias curve against Murata's data before ordering.")
        (field (name "SPEC") "X5R 6.3V +-10%, 0.30 mm max")
      )
      (libsource (lib "eagle-import") (part "C-USC0201"))
    )
    (comp (ref "C122")
      (value "0.47uF")
      (footprint "eagle-import:C0201")
      (fields
        (field (name "MANF") "Murata")
        (field (name "MANF#") "GRM033R60J474KE15D")
        (field (name "NOTE") "0402 -> 0201 to cut ESL, following Cmod A7. THE VOLTAGE RATING DROPS 16V to 6.3V and that costs real capacitance: on VCC3V3 a 6.3V 0201 sits at 52 percent of rating and DC bias typically removes 60-75 percent of it, against 15-25 percent for the 16V 0402 it replaces. The BOM value is unchanged, so validate.py's UG483 count still passes -- it counts nominal values and cannot see bias derating. Effective decoupling on 3V3 is roughly half what it was. Confirm the MPN suffix and the bias curve against Murata's data before ordering.")
        (field (name "SPEC") "X5R 6.3V +-10%, 0.30 mm max")
      )
      (libsource (lib "eagle-import") (part "C-USC0201"))
    )
    (comp (ref "C140")
      (value "22uF")
      (footprint "eagle-import:C0805")
      (fields
        (field (name "MANF") "Murata")
        (field (name "MANF#") "GRM21BR61A226ME44L")
        (field (name "SPEC") "X5R 10V +-20%, 1.45 mm max")
      )
      (libsource (lib "eagle-import") (part "C-USC0805"))
    )
    (comp (ref "C141")
      (value "22uF")
      (footprint "eagle-import:C0805")
      (fields
        (field (name "MANF") "Murata")
        (field (name "MANF#") "GRM21BR61A226ME44L")
        (field (name "NOTE") "Second half of a bulk position: each 47uF 1206 became two 22uF 0805. Nominal drops 47 -> 44 uF per position, but the 0805 is 10V where the 1206 was 6.3V, so it derates less under bias and the pair should deliver at least what the single part did. Height also drops 1.60 -> 1.45 mm max, which the back-side budget against the 2.54 mm header standoff cares about.")
        (field (name "SPEC") "X5R 10V +-20%, 1.45 mm max")
      )
      (libsource (lib "eagle-import") (part "C-USC0805"))
    )
    (comp (ref "C142")
      (value "22uF")
      (footprint "eagle-import:C0805")
      (fields
        (field (name "MANF") "Murata")
        (field (name "MANF#") "GRM21BR61A226ME44L")
        (field (name "NOTE") "Second half of a bulk position: each 47uF 1206 became two 22uF 0805. Nominal drops 47 -> 44 uF per position, but the 0805 is 10V where the 1206 was 6.3V, so it derates less under bias and the pair should deliver at least what the single part did. Height also drops 1.60 -> 1.45 mm max, which the back-side budget against the 2.54 mm header standoff cares about.")
        (field (name "SPEC") "X5R 10V +-20%, 1.45 mm max")
      )
      (libsource (lib "eagle-import") (part "C-USC0805"))
    )
    (comp (ref "C143")
      (value "22uF")
      (footprint "eagle-import:C0805")
      (fields
        (field (name "MANF") "Murata")
        (field (name "MANF#") "GRM21BR61A226ME44L")
        (field (name "NOTE") "Second half of a bulk position: each 47uF 1206 became two 22uF 0805. Nominal drops 47 -> 44 uF per position, but the 0805 is 10V where the 1206 was 6.3V, so it derates less under bias and the pair should deliver at least what the single part did. Height also drops 1.60 -> 1.45 mm max, which the back-side budget against the 2.54 mm header standoff cares about.")
        (field (name "SPEC") "X5R 10V +-20%, 1.45 mm max")
      )
      (libsource (lib "eagle-import") (part "C-USC0805"))
    )
    (comp (ref "C144")
      (value "22uF")
      (footprint "eagle-import:C0805")
      (fields
        (field (name "MANF") "Murata")
        (field (name "MANF#") "GRM21BR61A226ME44L")
        (field (name "NOTE") "Second half of a bulk position: each 47uF 1206 became two 22uF 0805. Nominal drops 47 -> 44 uF per position, but the 0805 is 10V where the 1206 was 6.3V, so it derates less under bias and the pair should deliver at least what the single part did. Height also drops 1.60 -> 1.45 mm max, which the back-side budget against the 2.54 mm header standoff cares about.")
        (field (name "SPEC") "X5R 10V +-20%, 1.45 mm max")
      )
      (libsource (lib "eagle-import") (part "C-USC0805"))
    )
    (comp (ref "C145")
      (value "22uF")
      (footprint "eagle-import:C0805")
      (fields
        (field (name "MANF") "Murata")
        (field (name "MANF#") "GRM21BR61A226ME44L")
        (field (name "NOTE") "Second half of a bulk position: each 47uF 1206 became two 22uF 0805. Nominal drops 47 -> 44 uF per position, but the 0805 is 10V where the 1206 was 6.3V, so it derates less under bias and the pair should deliver at least what the single part did. Height also drops 1.60 -> 1.45 mm max, which the back-side budget against the 2.54 mm header standoff cares about.")
        (field (name "SPEC") "X5R 10V +-20%, 1.45 mm max")
      )
      (libsource (lib "eagle-import") (part "C-USC0805"))
    )
    (comp (ref "C146")
      (value "22uF")
      (footprint "eagle-import:C0805")
      (fields
        (field (name "MANF") "Murata")
        (field (name "MANF#") "GRM21BR61A226ME44L")
        (field (name "NOTE") "Second half of a bulk position: each 47uF 1206 became two 22uF 0805. Nominal drops 47 -> 44 uF per position, but the 0805 is 10V where the 1206 was 6.3V, so it derates less under bias and the pair should deliver at least what the single part did. Height also drops 1.60 -> 1.45 mm max, which the back-side budget against the 2.54 mm header standoff cares about.")
        (field (name "SPEC") "X5R 10V +-20%, 1.45 mm max")
      )
      (libsource (lib "eagle-import") (part "C-USC0805"))
    )
    (comp (ref "C78")
      (value "22uF 10V")
      (footprint "eagle-import:C0805")
      (fields
        (field (name "MANF") "Murata")
        (field (name "MANF#") "GRM21BR61A226ME44L")
        (field (name "SPEC") "X5R 10V +-20%, 1.45 mm max -- LTC3569 CIN on VU (5V USB)")
      )
      (libsource (lib "eagle-import") (part "C-GENERICC0805"))
    )
    (comp (ref "C79")
      (value "20pF")
      (footprint "eagle-import:C0402")
      (fields
        (field (name "MANF") "Murata")
        (field (name "MANF#") "GRM1555C1H200JA01D")
        (field (name "SPEC") "C0G 50V +-5%, 0.50 mm max -- C0G for the feedback feedforward")
      )
      (libsource (lib "eagle-import") (part "C-GENERICC0402"))
    )
    (comp (ref "C80")
      (value "22uF")
      (footprint "eagle-import:C0805")
      (fields
        (field (name "MANF") "Murata")
        (field (name "MANF#") "GRM21BR61A226ME44L")
        (field (name "SPEC") "X5R 10V +-20%, 1.45 mm max -- LTC3569 COUT buck 1")
      )
      (libsource (lib "eagle-import") (part "C-GENERICC0805"))
    )
    (comp (ref "C81")
      (value "20pF")
      (footprint "eagle-import:C0402")
      (fields
        (field (name "MANF") "Murata")
        (field (name "MANF#") "GRM1555C1H200JA01D")
        (field (name "SPEC") "C0G 50V +-5%, 0.50 mm max -- C0G for the feedback feedforward")
      )
      (libsource (lib "eagle-import") (part "C-GENERICC0402"))
    )
    (comp (ref "C82")
      (value "10uF")
      (footprint "eagle-import:C0603")
      (fields
        (field (name "MANF") "Murata")
        (field (name "MANF#") "GRM188R60J106ME47D")
        (field (name "SPEC") "X5R 6.3V +-20%, 0.90 mm max")
      )
      (libsource (lib "eagle-import") (part "C-GENERICC0603"))
    )
    (comp (ref "C83")
      (value "20pF")
      (footprint "eagle-import:C0402")
      (fields
        (field (name "MANF") "Murata")
        (field (name "MANF#") "GRM1555C1H200JA01D")
        (field (name "SPEC") "C0G 50V +-5%, 0.50 mm max -- C0G for the feedback feedforward")
      )
      (libsource (lib "eagle-import") (part "C-GENERICC0402"))
    )
    (comp (ref "C84")
      (value "10uF")
      (footprint "eagle-import:C0603")
      (fields
        (field (name "MANF") "Murata")
        (field (name "MANF#") "GRM188R60J106ME47D")
        (field (name "SPEC") "X5R 6.3V +-20%, 0.90 mm max")
      )
      (libsource (lib "eagle-import") (part "C-GENERICC0603"))
    )
    (comp (ref "D1")
      (value "PMEG2020EJ,115")
      (footprint "eagle-import:SOD123")
      (fields (field (name "MANF") "Nexperia") (field (name "MANF#") "PMEG2020EJ,115"))
      (libsource (lib "eagle-import") (part "DIODE"))
    )
    (comp (ref "L1")
      (value "1.5uH")
      (footprint "eagle-import:IND2520")
      (fields
        (field (name "MANF") "Murata")
        (field (name "MANF#") "DFE252010P-1R5M=P2")
        (field (name "SPEC") "1.5uH +-20%, Idc >=1.8A REQUIRED, 1.00 mm max -- SW1, 1.2A buck")
      )
      (libsource (lib "eagle-import") (part "INDUCTOR-2520"))
    )
    (comp (ref "L2")
      (value "3.3uH")
      (footprint "eagle-import:IND2520")
      (fields
        (field (name "MANF") "Murata")
        (field (name "MANF#") "DFE252010P-3R3M=P2")
        (field (name "SPEC") "3.3uH +-20%, Idc >=0.9A REQUIRED, 1.00 mm max -- SW2, 600mA buck")
      )
      (libsource (lib "eagle-import") (part "INDUCTOR-2520"))
    )
    (comp (ref "L3")
      (value "2.2uH")
      (footprint "eagle-import:IND2520")
      (fields
        (field (name "MANF") "Murata")
        (field (name "MANF#") "DFE252010P-2R2M=P2")
        (field (name "SPEC") "2.2uH +-20%, Idc >=0.9A REQUIRED, 1.00 mm max -- SW3, 600mA buck")
      )
      (libsource (lib "eagle-import") (part "INDUCTOR-2520"))
    )
    (comp (ref "LD5")
      (value "green")
      (footprint "eagle-import:LED0603")
      (fields
        (field (name "MANF") "Lite-On")
        (field (name "MANF#") "LTST-C191KGKT")
        (field (name "NOTE") "Power-good indicator: VCC3V3 to LD5 to R78 680R to Q2 drain to GND. SELECTED FROM THE CIRCUIT, not recovered -- the part carried no value and no number. THE RESISTOR ALREADY CHOSE THE COLOUR: 680R off 3.3 V passes (3.3 - Vf)/680, which is 1.9 mA for a green LED or 2.1 for a red, but only 0.6 mA for a blue or white one, too dim to read. So it is a green or red part, and green is the convention for power good. 1.9 mA is low but plain on a modern high-efficiency 0603; take R78 to 330R if you want it brighter.")
        (field (name "SPEC") "green indicator, 0603, Vf 2.1V max at 2mA")
      )
      (libsource (lib "eagle-import") (part "LED"))
    )
    (comp (ref "Q2")
      (value "2N7002")
      (footprint "eagle-import:SOT23-3")
      (fields
        (field (name "MANF") "onsemi")
        (field (name "MANF#") "2N7002LT1G")
        (field (name "NOTE") "Switches the PGOOD indicator LD5. SELECTED FROM THE CIRCUIT, not recovered -- the part carried no value and no number. What it has to do: its gate is on PGOOD, the LTC3569's open-drain output pulled to 3V3 through R77's 100k, so Vgs is a static 3.3 V and the weak pull-up costs nothing because a gate draws no DC. That needs a LOGIC-LEVEL threshold, comfortably under 3.3 V. The drain carries the LED at 1.9 mA against the 2N7002's 115 mA, and sees 3.3 V against 60. The SOT23-3 footprint here names its pads G, S and D at pins 1, 2 and 3, which is the 2N7002 pinout exactly, so nothing in the layout moves.")
        (field (name "SPEC") "N-ch MOSFET, logic level: Vgs(th) 1.0 to 2.5V, Vds 20V min, Id 100mA min, SOT-23 G/S/D on pins 1/2/3")
      )
      (libsource (lib "eagle-import") (part "NMOS"))
    )
    (comp (ref "Q3")
      (value "MBT3904DW1T1")
      (footprint "eagle-import:SOT363")
      (fields (field (name "MANF") "onsemi") (field (name "MANF#") "MBT3904DW1T1G"))
      (libsource (lib "eagle-import") (part "NPN-DUAL"))
    )
    (comp (ref "R65")
      (value "30K 1%")
      (footprint "eagle-import:R0402")
      (fields
        (field (name "MANF") "Yageo")
        (field (name "MANF#") "RC0402FR-0730KL")
        (field (name "SPEC") "thick film +-1%, 1/16W, 0402")
      )
      (libsource (lib "eagle-import") (part "R-US_SMALLR0402"))
    )
    (comp (ref "R66")
      (value "120K 1%")
      (footprint "eagle-import:R0402")
      (fields
        (field (name "MANF") "Yageo")
        (field (name "MANF#") "RC0402FR-07120KL")
        (field (name "SPEC") "thick film +-1%, 1/16W, 0402")
      )
      (libsource (lib "eagle-import") (part "R-US_SMALLR0402"))
    )
    (comp (ref "R67")
      (value "3.48K 1%")
      (footprint "eagle-import:R0402")
      (fields
        (field (name "MANF") "Yageo")
        (field (name "MANF#") "RC0402FR-073K48L")
        (field (name "SPEC") "thick film +-1%, 1/16W, 0402")
      )
      (libsource (lib "eagle-import") (part "R-US_SMALLR0402"))
    )
    (comp (ref "R68")
      (value "150K 1%")
      (footprint "eagle-import:R0402")
      (fields
        (field (name "MANF") "Yageo")
        (field (name "MANF#") "RC0402FR-07150KL")
        (field (name "SPEC") "thick film +-1%, 1/16W, 0402")
      )
      (libsource (lib "eagle-import") (part "R-US_SMALLR0402"))
    )
    (comp (ref "R69")
      (value "120K 1%")
      (footprint "eagle-import:R0402")
      (fields
        (field (name "MANF") "Yageo")
        (field (name "MANF#") "RC0402FR-07120KL")
        (field (name "SPEC") "thick film +-1%, 1/16W, 0402")
      )
      (libsource (lib "eagle-import") (part "R-US_SMALLR0402"))
    )
    (comp (ref "R70")
      (value "10K 1%")
      (footprint "eagle-import:R0402")
      (fields
        (field (name "MANF") "Yageo")
        (field (name "MANF#") "RC0402FR-0710KL")
        (field (name "SPEC") "thick film +-1%, 1/16W, 0402")
      )
      (libsource (lib "eagle-import") (part "R-US_SMALLR0402"))
    )
    (comp (ref "R71")
      (value "180K 1%")
      (footprint "eagle-import:R0402")
      (fields
        (field (name "MANF") "Yageo")
        (field (name "MANF#") "RC0402FR-07180KL")
        (field (name "SPEC") "thick film +-1%, 1/16W, 0402")
      )
      (libsource (lib "eagle-import") (part "R-US_SMALLR0402"))
    )
    (comp (ref "R72")
      (value "0 (No Load, DNP)")
      (footprint "eagle-import:R0402")
      (libsource (lib "eagle-import") (part "R-US_SMALLR0402"))
    )
    (comp (ref "R73")
      (value "57.6K 1%")
      (footprint "eagle-import:R0402")
      (fields
        (field (name "MANF") "Yageo")
        (field (name "MANF#") "RC0402FR-0757K6L")
        (field (name "SPEC") "thick film +-1%, 1/16W, 0402")
      )
      (libsource (lib "eagle-import") (part "R-US_SMALLR0402"))
    )
    (comp (ref "R74")
      (value "100K")
      (footprint "eagle-import:R0402")
      (fields
        (field (name "MANF") "Yageo")
        (field (name "MANF#") "RC0402FR-07100KL")
        (field (name "SPEC") "thick film +-1%, 1/16W, 0402")
      )
      (libsource (lib "eagle-import") (part "R-US_SMALLR0402"))
    )
    (comp (ref "R75")
      (value "100K")
      (footprint "eagle-import:R0402")
      (fields
        (field (name "MANF") "Yageo")
        (field (name "MANF#") "RC0402FR-07100KL")
        (field (name "SPEC") "thick film +-1%, 1/16W, 0402")
      )
      (libsource (lib "eagle-import") (part "R-US_SMALLR0402"))
    )
    (comp (ref "R76")
      (value "100K")
      (footprint "eagle-import:R0402")
      (fields
        (field (name "MANF") "Yageo")
        (field (name "MANF#") "RC0402FR-07100KL")
        (field (name "SPEC") "thick film +-1%, 1/16W, 0402")
      )
      (libsource (lib "eagle-import") (part "R-US_SMALLR0402"))
    )
    (comp (ref "R77")
      (value "100K")
      (footprint "eagle-import:R0402")
      (fields
        (field (name "MANF") "Yageo")
        (field (name "MANF#") "RC0402FR-07100KL")
        (field (name "SPEC") "thick film +-1%, 1/16W, 0402")
      )
      (libsource (lib "eagle-import") (part "R-US_SMALLR0402"))
    )
    (comp (ref "R78")
      (value "680")
      (footprint "eagle-import:R0402")
      (fields
        (field (name "MANF") "Yageo")
        (field (name "MANF#") "RC0402FR-07680RL")
        (field (name "SPEC") "thick film +-1%, 1/16W, 0402")
      )
      (libsource (lib "eagle-import") (part "R-US_SMALLR0402"))
    )
    (comp (ref "R79")
      (value "1K")
      (footprint "eagle-import:R0402")
      (fields
        (field (name "MANF") "Yageo")
        (field (name "MANF#") "RC0402FR-071KL")
        (field (name "SPEC") "thick film +-1%, 1/16W, 0402")
      )
      (libsource (lib "eagle-import") (part "R-US_SMALLR0402"))
    )
    (comp (ref "U8")
      (value "LTC3569EUDC#TRPBF")
      (footprint "eagle-import:LTC3569-QFN20")
      (fields (field (name "MANF") "Analog Devices") (field (name "MANF#") "LTC3569EUDC#TRPBF"))
      (libsource (lib "eagle-import") (part "LTC3569-UDC"))
    )
    (comp (ref "X1")
      (value "Molex 105017-0001 Micro-USB-B")
      (footprint "eagle-import:MOLEX-105017-0001")
      (fields
        (field (name "MANF") "Molex")
        (field (name "MANF_1") "Molex")
        (field (name "MANF#") "105017-0001")
      )
      (libsource (lib "eagle-import") (part "MINI-USB-105017-0001"))
    )
    (comp (ref "BTN")
      (value "PTA-142")
      (footprint "eagle-import:PTA-142")
      (fields
        (field (name "MANF#") "PTA-142")
        (field (name "NOTE") "PTA-142, from the catalogue page in Datasheet/pta142-112.pdf. THE PART NUMBER IS COMPLETE AS IT STANDS: the sheet lists one operating force (130 gf +-30), one stem colour (black) and no ordering suffix table, so there is nothing to append. It is the SMD reflow member of the family -- PTA-112 and PTA-113 are through-hole, PTA-143 is the SMD with a ground terminal. Rated DC12V 50 mA, 100 mOhm contact, 50000 cycles, 0.25 mm travel, 2200 per reel. The P.C.B. Layout on that page is 9.1 mm overall, 5.9 inner, 4.4 high, 1.6 pads, which is exactly the land in this library. THE PAGE DOES NOT NAME THE MANUFACTURER -- it is one sheet lifted out of a catalogue and carries no logo, so MANF is left empty rather than guessed. Distributors index PTA-142 directly.")
        (field (name "SPEC") "tactile switch, SMD gull-wing, 4.5 x 4.5 mm, 130 gf, DC12V 50 mA, 50000 cycles")
      )
      (libsource (lib "eagle-import") (part "SWITCH_TACT"))
    )
    (comp (ref "C36")
      (value "1nF")
      (footprint "eagle-import:C0402")
      (fields
        (field (name "MANF") "Murata")
        (field (name "MANF#") "GRM155R71H102KA01D")
        (field (name "SPEC") "X7R 50V +-10%, 0.50 mm max")
      )
      (libsource (lib "eagle-import") (part "C-GENERICC0402"))
    )
    (comp (ref "C37")
      (value "1nF")
      (footprint "eagle-import:C0402")
      (fields
        (field (name "MANF") "Murata")
        (field (name "MANF#") "GRM155R71H102KA01D")
        (field (name "SPEC") "X7R 50V +-10%, 0.50 mm max")
      )
      (libsource (lib "eagle-import") (part "C-GENERICC0402"))
    )
    (comp (ref "D2")
      (value "PMEG2020EJ,115")
      (footprint "eagle-import:SOD123")
      (fields (field (name "MANF") "Nexperia") (field (name "MANF#") "PMEG2020EJ,115"))
      (libsource (lib "eagle-import") (part "DIODE"))
    )
    (comp (ref "D3")
      (value "SMF5.0A")
      (footprint "eagle-import:SOD123")
      (fields (field (name "MANF") "Littelfuse") (field (name "MANF#") "SMF5.0A"))
      (libsource (lib "eagle-import") (part "TVS"))
    )
    (comp (ref "J1")
      (value "Pmod 2x6")
      (footprint "eagle-import:2X06")
      (fields
        (field (name "MANF") "Sullins")
        (field (name "MANF#") "PPTC062LFBN-RC")
        (field (name "NOTE") "A SOCKET, NOT PINS, AND THE LIBRARY NAME DISAGREES WITH THAT. The package is called PIN HEADER 2x6 and the deviceset PINHD-2X6, which is inherited naming, but on a Digilent Pmod the HOST carries the female socket and the peripheral module carries the male pins that plug into it. Cmod A7 is the same. Order male pins off that library name and no Pmod will mate. The footprint is 12 plated holes on 2.54 either way, so a male header such as Sullins PRPC006DAAN-RC drops into the same land if you would rather have pins and a cable. Height 8.5 mm is not a problem: J1 is on the FRONT, and it is the back that faces a breadboard a couple of millimetres away.")
        (field (name "SPEC") "2x6 female header, 2.54 mm pitch, through-hole, 12 way -- Pmod host socket")
      )
      (libsource (lib "eagle-import") (part "PINHD-2X6"))
    )
    (comp (ref "LD0")
      (value "VS NRD8")
      (footprint "eagle-import:VS-NRD8")
      (fields
        (field (name "MANF") "Victory Electronics")
        (field (name "MANF#") "VS NRD8")
        (field (name "NOTE") "Victory Electronics VS NRD8, common anode, 1.6 x 1.6 x 0.35 mm. The datasheet's own Part Number column reads VS NRD8, so the value was the part number all along. Land pattern already drawn from its Recommended Soldering Pad. 25 mA absolute max per colour. GREEN AND BLUE ARE 3.3 V-CLASS DICE ON A 3.3 V RAIL: their Vf is 3.3 V typical at 20 mA, but the working point here is 2 to 3 mA, where the datasheet curve puts Vf near 3.0, so they light perfectly well -- the 20 mA figure does not apply at 3 mA. What it does mean is that the series resistor never dominates their current, so brightness tracks the diode rather than the resistor and varies with part and temperature. Red, an AlGaInP die at about 1.9 V, has real headroom and is set by its resistor. R80, R81 and R82 are chosen to balance that as far as a 3.3 V rail allows; see the note on any of them.")
        (field (name "SPEC") "RGB LED, common anode, 1.6 x 1.6 x 0.35 mm, 25 mA max per colour")
      )
      (libsource (lib "eagle-import") (part "LED_RGB"))
    )
    (comp (ref "LD1")
      (value "red")
      (footprint "eagle-import:LED0603")
      (fields
        (field (name "MANF") "Lite-On")
        (field (name "MANF#") "LTST-C191KRKT")
        (field (name "NOTE") "User status LED, driven straight off an FPGA pin through R83 at 330R: (3.3 - Vf)/330 is 3.9 mA green, 4.2 red, 3.6 yellow, and 1.2 mA blue or white. Any of the first three is comfortable and well inside an LVCMOS33 pin's 12 mA. RED IS A PREFERENCE, NOT A CONSTRAINT -- the circuit takes green just as happily. It is red so that the two user LEDs read differently from LD5, which is green and means power good; on a board being brought up that is worth being able to tell apart at a glance. Same LTST-C191 family and the same 0603 land as LD5, so it is one line in the catalogue, not two. Confirm the suffix before ordering.")
        (field (name "SPEC") "red indicator, 0603, Vf 2.1V max at 4mA")
      )
      (libsource (lib "eagle-import") (part "LED"))
    )
    (comp (ref "LD2")
      (value "red")
      (footprint "eagle-import:LED0603")
      (fields
        (field (name "MANF") "Lite-On")
        (field (name "MANF#") "LTST-C191KRKT")
        (field (name "NOTE") "User status LED, driven straight off an FPGA pin through R84 at 330R: (3.3 - Vf)/330 is 3.9 mA green, 4.2 red, 3.6 yellow, and 1.2 mA blue or white. Any of the first three is comfortable and well inside an LVCMOS33 pin's 12 mA. RED IS A PREFERENCE, NOT A CONSTRAINT -- the circuit takes green just as happily. It is red so that the two user LEDs read differently from LD5, which is green and means power good; on a board being brought up that is worth being able to tell apart at a glance. Same LTST-C191 family and the same 0603 land as LD5, so it is one line in the catalogue, not two. Confirm the suffix before ordering.")
        (field (name "SPEC") "red indicator, 0603, Vf 2.1V max at 4mA")
      )
      (libsource (lib "eagle-import") (part "LED"))
    )
    (comp (ref "R10")
      (value "2.32K")
      (footprint "eagle-import:R0201")
      (fields
        (field (name "MANF") "Yageo")
        (field (name "MANF#") "RC0201FR-072K32L")
        (field (name "SPEC") "thick film +-1%, 1/20W, 0201")
      )
      (libsource (lib "eagle-import") (part "R-US_R0201"))
    )
    (comp (ref "R11")
      (value "1K")
      (footprint "eagle-import:R0201")
      (fields
        (field (name "MANF") "Yageo")
        (field (name "MANF#") "RC0201FR-071KL")
        (field (name "SPEC") "thick film +-1%, 1/20W, 0201")
      )
      (libsource (lib "eagle-import") (part "R-US_R0201"))
    )
    (comp (ref "R12")
      (value "140")
      (footprint "eagle-import:R0201")
      (fields
        (field (name "MANF") "Yageo")
        (field (name "MANF#") "RC0201FR-07140RL")
        (field (name "SPEC") "thick film +-1%, 1/20W, 0201")
      )
      (libsource (lib "eagle-import") (part "R-US_R0201"))
    )
    (comp (ref "R13")
      (value "845")
      (footprint "eagle-import:R0201")
      (fields
        (field (name "MANF") "Yageo")
        (field (name "MANF#") "RC0201FR-07845RL")
        (field (name "SPEC") "thick film +-1%, 1/20W, 0201")
      )
      (libsource (lib "eagle-import") (part "R-US_R0201"))
    )
    (comp (ref "R14")
      (value "2.32K")
      (footprint "eagle-import:R0201")
      (fields
        (field (name "MANF") "Yageo")
        (field (name "MANF#") "RC0201FR-072K32L")
        (field (name "SPEC") "thick film +-1%, 1/20W, 0201")
      )
      (libsource (lib "eagle-import") (part "R-US_R0201"))
    )
    (comp (ref "R15")
      (value "1K")
      (footprint "eagle-import:R0201")
      (fields
        (field (name "MANF") "Yageo")
        (field (name "MANF#") "RC0201FR-071KL")
        (field (name "SPEC") "thick film +-1%, 1/20W, 0201")
      )
      (libsource (lib "eagle-import") (part "R-US_R0201"))
    )
    (comp (ref "R16")
      (value "140")
      (footprint "eagle-import:R0201")
      (fields
        (field (name "MANF") "Yageo")
        (field (name "MANF#") "RC0201FR-07140RL")
        (field (name "SPEC") "thick film +-1%, 1/20W, 0201")
      )
      (libsource (lib "eagle-import") (part "R-US_R0201"))
    )
    (comp (ref "R17")
      (value "845")
      (footprint "eagle-import:R0201")
      (fields
        (field (name "MANF") "Yageo")
        (field (name "MANF#") "RC0201FR-07845RL")
        (field (name "SPEC") "thick film +-1%, 1/20W, 0201")
      )
      (libsource (lib "eagle-import") (part "R-US_R0201"))
    )
    (comp (ref "R26")
      (value "200")
      (footprint "eagle-import:R0201")
      (fields
        (field (name "MANF") "Yageo")
        (field (name "MANF#") "RC0201FR-07200RL")
        (field (name "SPEC") "thick film +-1%, 1/20W, 0201")
      )
      (libsource (lib "eagle-import") (part "R-US_SMALLR0201"))
    )
    (comp (ref "R27")
      (value "200")
      (footprint "eagle-import:R0201")
      (fields
        (field (name "MANF") "Yageo")
        (field (name "MANF#") "RC0201FR-07200RL")
        (field (name "SPEC") "thick film +-1%, 1/20W, 0201")
      )
      (libsource (lib "eagle-import") (part "R-US_SMALLR0201"))
    )
    (comp (ref "R28")
      (value "200")
      (footprint "eagle-import:R0201")
      (fields
        (field (name "MANF") "Yageo")
        (field (name "MANF#") "RC0201FR-07200RL")
        (field (name "SPEC") "thick film +-1%, 1/20W, 0201")
      )
      (libsource (lib "eagle-import") (part "R-US_SMALLR0201"))
    )
    (comp (ref "R29")
      (value "200")
      (footprint "eagle-import:R0201")
      (fields
        (field (name "MANF") "Yageo")
        (field (name "MANF#") "RC0201FR-07200RL")
        (field (name "SPEC") "thick film +-1%, 1/20W, 0201")
      )
      (libsource (lib "eagle-import") (part "R-US_SMALLR0201"))
    )
    (comp (ref "R30")
      (value "200")
      (footprint "eagle-import:R0201")
      (fields
        (field (name "MANF") "Yageo")
        (field (name "MANF#") "RC0201FR-07200RL")
        (field (name "SPEC") "thick film +-1%, 1/20W, 0201")
      )
      (libsource (lib "eagle-import") (part "R-US_SMALLR0201"))
    )
    (comp (ref "R31")
      (value "200")
      (footprint "eagle-import:R0201")
      (fields
        (field (name "MANF") "Yageo")
        (field (name "MANF#") "RC0201FR-07200RL")
        (field (name "SPEC") "thick film +-1%, 1/20W, 0201")
      )
      (libsource (lib "eagle-import") (part "R-US_SMALLR0201"))
    )
    (comp (ref "R32")
      (value "200")
      (footprint "eagle-import:R0201")
      (fields
        (field (name "MANF") "Yageo")
        (field (name "MANF#") "RC0201FR-07200RL")
        (field (name "SPEC") "thick film +-1%, 1/20W, 0201")
      )
      (libsource (lib "eagle-import") (part "R-US_SMALLR0201"))
    )
    (comp (ref "R33")
      (value "200")
      (footprint "eagle-import:R0201")
      (fields
        (field (name "MANF") "Yageo")
        (field (name "MANF#") "RC0201FR-07200RL")
        (field (name "SPEC") "thick film +-1%, 1/20W, 0201")
      )
      (libsource (lib "eagle-import") (part "R-US_SMALLR0201"))
    )
    (comp (ref "R80")
      (value "33")
      (footprint "eagle-import:R0402")
      (fields
        (field (name "MANF") "Yageo")
        (field (name "MANF#") "RC0402FR-0733RL")
        (field (name "NOTE") "RGB LED balance. The green and blue dice are 3.3 V-class parts on a 3.3 V rail, so the resistor never dominates their current -- that is structural and no resistor value fixes it. What the values CAN do is stop red swamping the other two. As built, and as Cmod A7 ships the same LED, 182/182/100 gave red 6.9 mA against green 1.9 and blue 1.5: red about four times either. At 330/33/33 it is red 3.8, green 2.9, blue 2.9. Worst case improves too, not just nominal -- green with a part 0.15 V high in Vf goes from 1.4 mA to 1.8. Lower resistors do make the current MORE sensitive in percentage terms, 77 percent of nominal retained at 100R against 61 at 33R, but the absolute floor is what you see and it rises. Currents read off the datasheet's own Vf/If curve at the working point, not off the 20 mA table.")
        (field (name "SPEC") "thick film +-1%, 1/16W, 0402")
      )
      (libsource (lib "eagle-import") (part "R-US_SMALLR0402"))
    )
    (comp (ref "R81")
      (value "330")
      (footprint "eagle-import:R0402")
      (fields
        (field (name "MANF") "Yageo")
        (field (name "MANF#") "RC0402FR-07330RL")
        (field (name "NOTE") "RGB LED balance. The green and blue dice are 3.3 V-class parts on a 3.3 V rail, so the resistor never dominates their current -- that is structural and no resistor value fixes it. What the values CAN do is stop red swamping the other two. As built, and as Cmod A7 ships the same LED, 182/182/100 gave red 6.9 mA against green 1.9 and blue 1.5: red about four times either. At 330/33/33 it is red 3.8, green 2.9, blue 2.9. Worst case improves too, not just nominal -- green with a part 0.15 V high in Vf goes from 1.4 mA to 1.8. Lower resistors do make the current MORE sensitive in percentage terms, 77 percent of nominal retained at 100R against 61 at 33R, but the absolute floor is what you see and it rises. Currents read off the datasheet's own Vf/If curve at the working point, not off the 20 mA table.")
        (field (name "SPEC") "thick film +-1%, 1/16W, 0402")
      )
      (libsource (lib "eagle-import") (part "R-US_SMALLR0402"))
    )
    (comp (ref "R82")
      (value "33")
      (footprint "eagle-import:R0402")
      (fields
        (field (name "MANF") "Yageo")
        (field (name "MANF#") "RC0402FR-0733RL")
        (field (name "NOTE") "RGB LED balance. The green and blue dice are 3.3 V-class parts on a 3.3 V rail, so the resistor never dominates their current -- that is structural and no resistor value fixes it. What the values CAN do is stop red swamping the other two. As built, and as Cmod A7 ships the same LED, 182/182/100 gave red 6.9 mA against green 1.9 and blue 1.5: red about four times either. At 330/33/33 it is red 3.8, green 2.9, blue 2.9. Worst case improves too, not just nominal -- green with a part 0.15 V high in Vf goes from 1.4 mA to 1.8. Lower resistors do make the current MORE sensitive in percentage terms, 77 percent of nominal retained at 100R against 61 at 33R, but the absolute floor is what you see and it rises. Currents read off the datasheet's own Vf/If curve at the working point, not off the 20 mA table.")
        (field (name "SPEC") "thick film +-1%, 1/16W, 0402")
      )
      (libsource (lib "eagle-import") (part "R-US_SMALLR0402"))
    )
    (comp (ref "R83")
      (value "330")
      (footprint "eagle-import:R0402")
      (fields
        (field (name "MANF") "Yageo")
        (field (name "MANF#") "RC0402FR-07330RL")
        (field (name "SPEC") "thick film +-1%, 1/16W, 0402")
      )
      (libsource (lib "eagle-import") (part "R-US_SMALLR0402"))
    )
    (comp (ref "R84")
      (value "330")
      (footprint "eagle-import:R0402")
      (fields
        (field (name "MANF") "Yageo")
        (field (name "MANF#") "RC0402FR-07330RL")
        (field (name "SPEC") "thick film +-1%, 1/16W, 0402")
      )
      (libsource (lib "eagle-import") (part "R-US_SMALLR0402"))
    )
    (comp (ref "R85")
      (value "10K")
      (footprint "eagle-import:R0402")
      (fields
        (field (name "MANF") "Yageo")
        (field (name "MANF#") "RC0402FR-0710KL")
        (field (name "SPEC") "thick film +-1%, 1/16W, 0402")
      )
      (libsource (lib "eagle-import") (part "R-US_SMALLR0402"))
    )
    (comp (ref "R86")
      (value "10K")
      (footprint "eagle-import:R0402")
      (fields
        (field (name "MANF") "Yageo")
        (field (name "MANF#") "RC0402FR-0710KL")
        (field (name "SPEC") "thick film +-1%, 1/16W, 0402")
      )
      (libsource (lib "eagle-import") (part "R-US_SMALLR0402"))
    )
    (comp (ref "U$2")
      (value "CC_CC")
      (footprint "eagle-import:CC_CC")
      (libsource (lib "eagle-import") (part "CC_CC"))
    )
    (comp (ref "U$3")
      (value "CC_BY")
      (footprint "eagle-import:CC_BY")
      (libsource (lib "eagle-import") (part "CC_BY"))
    )
    (comp (ref "U$4")
      (value "CC_SA")
      (footprint "eagle-import:CC_SA")
      (libsource (lib "eagle-import") (part "CC_SA"))
    )
    (comp (ref "U$5")
      (value "CC_COPYRIGHT")
      (footprint "eagle-import:CC_COPYRIGHT")
      (libsource (lib "eagle-import") (part "CC_COPYRIGHT"))
    )
    (comp (ref "X2")
      (value "ZULU-CONN")
      (footprint "eagle-import:ZULU-DIP37")
      (libsource (lib "eagle-import") (part "ZULU-CONN"))
    )
  )
  (nets
    (net (code "1") (name "A0") (class "Default")
      (node (ref "U1") (pin "U2") (pinfunction "1_U2") (pintype "bidirectional"))
      (node (ref "U3") (pin "23") (pinfunction "P$1_23") (pintype "bidirectional"))
    )
    (net (code "2") (name "A1") (class "Default")
      (node (ref "U1") (pin "T3") (pinfunction "1_T3") (pintype "bidirectional"))
      (node (ref "U3") (pin "24") (pinfunction "P$1_24") (pintype "bidirectional"))
    )
    (net (code "3") (name "A2") (class "Default")
      (node (ref "U1") (pin "T2") (pinfunction "1_T2") (pintype "bidirectional"))
      (node (ref "U3") (pin "25") (pinfunction "P$1_25") (pintype "bidirectional"))
    )
    (net (code "4") (name "A3") (class "Default")
      (node (ref "U1") (pin "T1") (pinfunction "1_T1") (pintype "bidirectional"))
      (node (ref "U3") (pin "26") (pinfunction "P$1_26") (pintype "bidirectional"))
    )
    (net (code "5") (name "A4") (class "Default")
      (node (ref "U1") (pin "R3") (pinfunction "1_R3") (pintype "bidirectional"))
      (node (ref "U3") (pin "29") (pinfunction "P$1_29") (pintype "bidirectional"))
    )
    (net (code "6") (name "A5") (class "Default")
      (node (ref "U1") (pin "R2") (pinfunction "1_R2") (pintype "bidirectional"))
      (node (ref "U3") (pin "30") (pinfunction "P$1_30") (pintype "bidirectional"))
    )
    (net (code "7") (name "A6") (class "Default")
      (node (ref "U1") (pin "P3") (pinfunction "1_P3") (pintype "bidirectional"))
      (node (ref "U3") (pin "31") (pinfunction "P$1_31") (pintype "bidirectional"))
    )
    (net (code "8") (name "A7") (class "Default")
      (node (ref "U1") (pin "P1") (pinfunction "1_P1") (pintype "bidirectional"))
      (node (ref "U3") (pin "32") (pinfunction "P$1_32") (pintype "bidirectional"))
    )
    (net (code "9") (name "A8") (class "Default")
      (node (ref "U1") (pin "N3") (pinfunction "1_N3") (pintype "bidirectional"))
      (node (ref "U3") (pin "33") (pinfunction "P$1_33") (pintype "bidirectional"))
    )
    (net (code "10") (name "A9") (class "Default")
      (node (ref "U1") (pin "N2") (pinfunction "1_N2") (pintype "bidirectional"))
      (node (ref "U3") (pin "34") (pinfunction "P$1_34") (pintype "bidirectional"))
    )
    (net (code "11") (name "A10") (class "Default")
      (node (ref "U1") (pin "U3") (pinfunction "1_U3") (pintype "bidirectional"))
      (node (ref "U3") (pin "22") (pinfunction "P$1_22") (pintype "bidirectional"))
    )
    (net (code "12") (name "A11") (class "Default")
      (node (ref "U1") (pin "N1") (pinfunction "1_N1") (pintype "bidirectional"))
      (node (ref "U3") (pin "35") (pinfunction "P$1_35") (pintype "bidirectional"))
    )
    (net (code "13") (name "A12") (class "Default")
      (node (ref "U1") (pin "M3") (pinfunction "1_M3") (pintype "bidirectional"))
      (node (ref "U3") (pin "36") (pinfunction "P$1_36") (pintype "bidirectional"))
    )
    (net (code "14") (name "AIN15_N") (class "Default")
      (node (ref "C36") (pin "1") (pinfunction "1_1") (pintype "passive"))
      (node (ref "R13") (pin "1") (pinfunction "1_1") (pintype "passive"))
      (node (ref "U1") (pin "G2") (pinfunction "1_G2") (pintype "input"))
    )
    (net (code "15") (name "AIN15_P") (class "Default")
      (node (ref "C36") (pin "2") (pinfunction "2_2") (pintype "passive"))
      (node (ref "R12") (pin "1") (pinfunction "1_1") (pintype "passive"))
      (node (ref "U1") (pin "G3") (pinfunction "1_G3") (pintype "input"))
    )
    (net (code "16") (name "AIN16_N") (class "Default")
      (node (ref "C37") (pin "1") (pinfunction "1_1") (pintype "passive"))
      (node (ref "R17") (pin "1") (pinfunction "1_1") (pintype "passive"))
      (node (ref "U1") (pin "J2") (pinfunction "1_J2") (pintype "input"))
    )
    (net (code "17") (name "AIN16_P") (class "Default")
      (node (ref "C37") (pin "2") (pinfunction "2_2") (pintype "passive"))
      (node (ref "R16") (pin "1") (pinfunction "1_1") (pintype "passive"))
      (node (ref "U1") (pin "H2") (pinfunction "1_H2") (pintype "input"))
    )
    (net (code "18") (name "ANALOG-IO0") (class "Default")
      (node (ref "R10") (pin "2") (pinfunction "2_2") (pintype "passive"))
      (node (ref "X2") (pin "42") (pinfunction "1_42") (pintype "bidirectional"))
    )
    (net (code "19") (name "ANALOG-IO1") (class "Default")
      (node (ref "R14") (pin "2") (pinfunction "2_2") (pintype "passive"))
      (node (ref "X2") (pin "43") (pinfunction "1_43") (pintype "bidirectional"))
    )
    (net (code "20") (name "BS0") (class "Default")
      (node (ref "U1") (pin "V2") (pinfunction "1_V2") (pintype "bidirectional"))
      (node (ref "U3") (pin "20") (pinfunction "P$1_20") (pintype "bidirectional"))
    )
    (net (code "21") (name "BS1") (class "Default")
      (node (ref "U1") (pin "U1") (pinfunction "1_U1") (pintype "bidirectional"))
      (node (ref "U3") (pin "21") (pinfunction "P$1_21") (pintype "bidirectional"))
    )
    (net (code "22") (name "BTN") (class "Default")
      (node (ref "R85") (pin "2") (pinfunction "2_2") (pintype "passive"))
      (node (ref "U1") (pin "N17") (pinfunction "1_N17") (pintype "input"))
    )
    (net (code "23") (name "CAS#") (class "Default")
      (node (ref "U1") (pin "W3") (pinfunction "1_W3") (pintype "bidirectional"))
      (node (ref "U3") (pin "17") (pinfunction "P$1_17") (pintype "bidirectional"))
    )
    (net (code "24") (name "CFG-M0") (class "Default")
      (node (ref "R20") (pin "1") (pinfunction "1_1") (pintype "passive"))
      (node (ref "U1") (pin "V12") (pinfunction "1_V12") (pintype "input"))
    )
    (net (code "25") (name "CFG-M1") (class "Default")
      (node (ref "R21") (pin "2") (pinfunction "2_2") (pintype "passive"))
      (node (ref "U1") (pin "W11") (pinfunction "1_W11") (pintype "input"))
    )
    (net (code "26") (name "CFG-M2") (class "Default")
      (node (ref "R22") (pin "2") (pinfunction "2_2") (pintype "passive"))
      (node (ref "U1") (pin "U10") (pinfunction "1_U10") (pintype "input"))
    )
    (net (code "27") (name "CHAN-CLK") (class "Default")
      (node (ref "U1") (pin "P18") (pinfunction "1_P18") (pintype "bidirectional"))
      (node (ref "X2") (pin "4") (pinfunction "1_4") (pintype "bidirectional"))
    )
    (net (code "28") (name "CHAN0") (class "Default")
      (node (ref "U1") (pin "B18") (pinfunction "1_B18") (pintype "bidirectional"))
      (node (ref "X2") (pin "5") (pinfunction "1_5") (pintype "input"))
    )
    (net (code "29") (name "CHAN1") (class "Default")
      (node (ref "U1") (pin "A18") (pinfunction "1_A18") (pintype "bidirectional"))
      (node (ref "X2") (pin "6") (pinfunction "1_6") (pintype "bidirectional"))
    )
    (net (code "30") (name "CHAN2") (class "Default")
      (node (ref "U1") (pin "B17") (pinfunction "1_B17") (pintype "bidirectional"))
      (node (ref "X2") (pin "7") (pinfunction "1_7") (pintype "bidirectional"))
    )
    (net (code "31") (name "CHAN3") (class "Default")
      (node (ref "U1") (pin "A17") (pinfunction "1_A17") (pintype "bidirectional"))
      (node (ref "X2") (pin "8") (pinfunction "1_8") (pintype "bidirectional"))
    )
    (net (code "32") (name "CHAN4") (class "Default")
      (node (ref "U1") (pin "C16") (pinfunction "1_C16") (pintype "bidirectional"))
      (node (ref "X2") (pin "9") (pinfunction "1_9") (pintype "bidirectional"))
    )
    (net (code "33") (name "CHAN5") (class "Default")
      (node (ref "U1") (pin "D17") (pinfunction "1_D17") (pintype "bidirectional"))
      (node (ref "X2") (pin "10") (pinfunction "1_10") (pintype "bidirectional"))
    )
    (net (code "34") (name "CHAN6") (class "Default")
      (node (ref "U1") (pin "H17") (pinfunction "1_H17") (pintype "bidirectional"))
      (node (ref "X2") (pin "11") (pinfunction "1_11") (pintype "bidirectional"))
    )
    (net (code "35") (name "CHAN7") (class "Default")
      (node (ref "U1") (pin "H19") (pinfunction "1_H19") (pintype "bidirectional"))
      (node (ref "X2") (pin "12") (pinfunction "1_12") (pintype "input"))
    )
    (net (code "36") (name "CHAN8") (class "Default")
      (node (ref "U1") (pin "J18") (pinfunction "1_J18") (pintype "bidirectional"))
      (node (ref "X2") (pin "13") (pinfunction "1_13") (pintype "bidirectional"))
    )
    (net (code "37") (name "CHAN9") (class "Default")
      (node (ref "U1") (pin "J17") (pinfunction "1_J17") (pintype "bidirectional"))
      (node (ref "X2") (pin "14") (pinfunction "1_14") (pintype "bidirectional"))
    )
    (net (code "38") (name "CHAN10") (class "Default")
      (node (ref "U1") (pin "J19") (pinfunction "1_J19") (pintype "bidirectional"))
      (node (ref "X2") (pin "15") (pinfunction "1_15") (pintype "input"))
    )
    (net (code "39") (name "CHAN11") (class "Default")
      (node (ref "U1") (pin "K17") (pinfunction "1_K17") (pintype "bidirectional"))
      (node (ref "X2") (pin "16") (pinfunction "1_16") (pintype "bidirectional"))
    )
    (net (code "40") (name "CHAN12") (class "Default")
      (node (ref "U1") (pin "W19") (pinfunction "1_W19") (pintype "bidirectional"))
      (node (ref "X2") (pin "25") (pinfunction "1_25") (pintype "bidirectional"))
    )
    (net (code "41") (name "CHAN13") (class "Default")
      (node (ref "U1") (pin "W18") (pinfunction "1_W18") (pintype "bidirectional"))
      (node (ref "X2") (pin "26") (pinfunction "1_26") (pintype "bidirectional"))
    )
    (net (code "42") (name "CHAN14") (class "Default")
      (node (ref "U1") (pin "W17") (pinfunction "1_W17") (pintype "bidirectional"))
      (node (ref "X2") (pin "27") (pinfunction "1_27") (pintype "bidirectional"))
    )
    (net (code "43") (name "CHAN15") (class "Default")
      (node (ref "U1") (pin "V17") (pinfunction "1_V17") (pintype "bidirectional"))
      (node (ref "X2") (pin "28") (pinfunction "1_28") (pintype "bidirectional"))
    )
    (net (code "44") (name "CHAN16") (class "Default")
      (node (ref "U1") (pin "W16") (pinfunction "1_W16") (pintype "bidirectional"))
      (node (ref "X2") (pin "29") (pinfunction "1_29") (pintype "input"))
    )
    (net (code "45") (name "CHAN17") (class "Default")
      (node (ref "U1") (pin "U16") (pinfunction "1_U16") (pintype "bidirectional"))
      (node (ref "X2") (pin "30") (pinfunction "1_30") (pintype "bidirectional"))
    )
    (net (code "46") (name "CHAN18") (class "Default")
      (node (ref "U1") (pin "V16") (pinfunction "1_V16") (pintype "bidirectional"))
      (node (ref "X2") (pin "31") (pinfunction "1_31") (pintype "bidirectional"))
    )
    (net (code "47") (name "CHAN19") (class "Default")
      (node (ref "U1") (pin "W15") (pinfunction "1_W15") (pintype "bidirectional"))
      (node (ref "X2") (pin "32") (pinfunction "1_32") (pintype "bidirectional"))
    )
    (net (code "48") (name "CHAN20") (class "Default")
      (node (ref "U1") (pin "V15") (pinfunction "1_V15") (pintype "bidirectional"))
      (node (ref "X2") (pin "33") (pinfunction "1_33") (pintype "bidirectional"))
    )
    (net (code "49") (name "CHAN21") (class "Default")
      (node (ref "U1") (pin "U15") (pinfunction "1_U15") (pintype "bidirectional"))
      (node (ref "X2") (pin "34") (pinfunction "1_34") (pintype "input"))
    )
    (net (code "50") (name "CHAN22") (class "Default")
      (node (ref "U1") (pin "W14") (pinfunction "1_W14") (pintype "bidirectional"))
      (node (ref "X2") (pin "35") (pinfunction "1_35") (pintype "bidirectional"))
    )
    (net (code "51") (name "CHAN23") (class "Default")
      (node (ref "U1") (pin "V14") (pinfunction "1_V14") (pintype "bidirectional"))
      (node (ref "X2") (pin "36") (pinfunction "1_36") (pintype "bidirectional"))
    )
    (net (code "52") (name "CHAN24") (class "Default")
      (node (ref "U1") (pin "U14") (pinfunction "1_U14") (pintype "bidirectional"))
      (node (ref "X2") (pin "37") (pinfunction "1_37") (pintype "input"))
    )
    (net (code "53") (name "CHAN25") (class "Default")
      (node (ref "U1") (pin "W13") (pinfunction "1_W13") (pintype "bidirectional"))
      (node (ref "X2") (pin "38") (pinfunction "1_38") (pintype "bidirectional"))
    )
    (net (code "54") (name "CHAN26") (class "Default")
      (node (ref "U1") (pin "V13") (pinfunction "1_V13") (pintype "bidirectional"))
      (node (ref "X2") (pin "39") (pinfunction "1_39") (pintype "bidirectional"))
    )
    (net (code "55") (name "CHAN27") (class "Default")
      (node (ref "U1") (pin "T18") (pinfunction "1_T18") (pintype "bidirectional"))
      (node (ref "X2") (pin "40") (pinfunction "1_40") (pintype "bidirectional"))
    )
    (net (code "56") (name "CHAN28") (class "Default")
      (node (ref "U1") (pin "R19") (pinfunction "1_R19") (pintype "input"))
      (node (ref "X2") (pin "41") (pinfunction "1_41") (pintype "bidirectional"))
    )
    (net (code "57") (name "CKE") (class "Default")
      (node (ref "U1") (pin "M2") (pinfunction "1_M2") (pintype "bidirectional"))
      (node (ref "U3") (pin "37") (pinfunction "P$1_37") (pintype "bidirectional"))
    )
    (net (code "58") (name "CLK-12M-FPGA") (class "Default")
      (node (ref "R25") (pin "2") (pinfunction "2_2") (pintype "passive"))
      (node (ref "U1") (pin "L17") (pinfunction "1_L17") (pintype "input"))
    )
    (net (code "59") (name "CLK-12M-FT") (class "Default")
      (node (ref "R24") (pin "2") (pinfunction "2_2") (pintype "passive"))
      (node (ref "U2") (pin "2") (pinfunction "OSCI_2") (pintype "bidirectional"))
    )
    (net (code "60") (name "CLK-12M-SHARED") (class "Default")
      (node (ref "Q1") (pin "3") (pinfunction "3_3") (pintype "passive"))
      (node (ref "R24") (pin "1") (pinfunction "1_1") (pintype "passive"))
      (node (ref "R25") (pin "1") (pinfunction "1_1") (pintype "passive"))
    )
    (net (code "61") (name "D0") (class "Default")
      (node (ref "U1") (pin "V8") (pinfunction "1_V8") (pintype "bidirectional"))
      (node (ref "U3") (pin "2") (pinfunction "P$1_2") (pintype "bidirectional"))
    )
    (net (code "62") (name "D1") (class "Default")
      (node (ref "U1") (pin "V7") (pinfunction "1_V7") (pintype "bidirectional"))
      (node (ref "U3") (pin "4") (pinfunction "P$1_4") (pintype "bidirectional"))
    )
    (net (code "63") (name "D2") (class "Default")
      (node (ref "U1") (pin "W7") (pinfunction "1_W7") (pintype "bidirectional"))
      (node (ref "U3") (pin "5") (pinfunction "P$1_5") (pintype "bidirectional"))
    )
    (net (code "64") (name "D3") (class "Default")
      (node (ref "U1") (pin "W6") (pinfunction "1_W6") (pintype "bidirectional"))
      (node (ref "U3") (pin "7") (pinfunction "P$1_7") (pintype "bidirectional"))
    )
    (net (code "65") (name "D4") (class "Default")
      (node (ref "U1") (pin "U5") (pinfunction "1_U5") (pintype "bidirectional"))
      (node (ref "U3") (pin "8") (pinfunction "P$1_8") (pintype "bidirectional"))
    )
    (net (code "66") (name "D5") (class "Default")
      (node (ref "U1") (pin "W5") (pinfunction "1_W5") (pintype "bidirectional"))
      (node (ref "U3") (pin "10") (pinfunction "P$1_10") (pintype "bidirectional"))
    )
    (net (code "67") (name "D6") (class "Default")
      (node (ref "U1") (pin "V5") (pinfunction "1_V5") (pintype "bidirectional"))
      (node (ref "U3") (pin "11") (pinfunction "P$1_11") (pintype "bidirectional"))
    )
    (net (code "68") (name "D7") (class "Default")
      (node (ref "U1") (pin "U4") (pinfunction "1_U4") (pintype "bidirectional"))
      (node (ref "U3") (pin "13") (pinfunction "P$1_13") (pintype "bidirectional"))
    )
    (net (code "69") (name "D8") (class "Default")
      (node (ref "U1") (pin "L1") (pinfunction "1_L1") (pintype "bidirectional"))
      (node (ref "U3") (pin "42") (pinfunction "P$1_42") (pintype "bidirectional"))
    )
    (net (code "70") (name "D9") (class "Default")
      (node (ref "U1") (pin "K3") (pinfunction "1_K3") (pintype "bidirectional"))
      (node (ref "U3") (pin "44") (pinfunction "P$1_44") (pintype "bidirectional"))
    )
    (net (code "71") (name "D10") (class "Default")
      (node (ref "U1") (pin "K2") (pinfunction "1_K2") (pintype "bidirectional"))
      (node (ref "U3") (pin "45") (pinfunction "P$1_45") (pintype "bidirectional"))
    )
    (net (code "72") (name "D11") (class "Default")
      (node (ref "U1") (pin "J1") (pinfunction "1_J1") (pintype "bidirectional"))
      (node (ref "U3") (pin "47") (pinfunction "P$1_47") (pintype "bidirectional"))
    )
    (net (code "73") (name "D12") (class "Default")
      (node (ref "U1") (pin "J3") (pinfunction "1_J3") (pintype "bidirectional"))
      (node (ref "U3") (pin "48") (pinfunction "P$1_48") (pintype "bidirectional"))
    )
    (net (code "74") (name "D13") (class "Default")
      (node (ref "U1") (pin "H1") (pinfunction "1_H1") (pintype "bidirectional"))
      (node (ref "U3") (pin "50") (pinfunction "P$1_50") (pintype "bidirectional"))
    )
    (net (code "75") (name "D14") (class "Default")
      (node (ref "U1") (pin "A14") (pinfunction "1_A14") (pintype "bidirectional"))
      (node (ref "U3") (pin "51") (pinfunction "P$1_51") (pintype "bidirectional"))
    )
    (net (code "76") (name "D15") (class "Default")
      (node (ref "U1") (pin "A15") (pinfunction "1_A15") (pintype "bidirectional"))
      (node (ref "U3") (pin "53") (pinfunction "P$1_53") (pintype "bidirectional"))
    )
    (net (code "77") (name "DONE") (class "Default")
      (node (ref "R100") (pin "1") (pinfunction "1_1") (pintype "passive"))
      (node (ref "R38") (pin "1") (pinfunction "1_1") (pintype "passive"))
      (node (ref "U2") (pin "22") (pinfunction "ADBUS5_22") (pintype "bidirectional"))
    )
    (net (code "78") (name "EE-CLK") (class "Default")
      (node (ref "R96") (pin "1") (pinfunction "1_1") (pintype "passive"))
      (node (ref "U10") (pin "2") (pinfunction "CLK_2") (pintype "bidirectional"))
      (node (ref "U2") (pin "62") (pinfunction "EECLK_62") (pintype "bidirectional"))
    )
    (net (code "79") (name "EE-CS") (class "Default")
      (node (ref "R98") (pin "1") (pinfunction "1_1") (pintype "passive"))
      (node (ref "U10") (pin "1") (pinfunction "CS_1") (pintype "bidirectional"))
      (node (ref "U2") (pin "63") (pinfunction "EECS_63") (pintype "bidirectional"))
    )
    (net (code "80") (name "EE-DATA") (class "Default")
      (node (ref "R101") (pin "2") (pinfunction "2_2") (pintype "passive"))
      (node (ref "U10") (pin "3") (pinfunction "DI_3") (pintype "bidirectional"))
      (node (ref "U2") (pin "61") (pinfunction "EEDATA_61") (pintype "bidirectional"))
    )
    (net (code "81") (name "EE-DATA-DO") (class "Default")
      (node (ref "R101") (pin "1") (pinfunction "1_1") (pintype "passive"))
      (node (ref "R97") (pin "1") (pinfunction "1_1") (pintype "passive"))
      (node (ref "U10") (pin "4") (pinfunction "DO_4") (pintype "bidirectional"))
    )
    (net (code "82") (name "EN_BIAS") (class "Default")
      (node (ref "Q3") (pin "4") (pinfunction "B_4") (pintype "input"))
      (node (ref "Q3") (pin "5") (pinfunction "C_5") (pintype "passive"))
      (node (ref "Q3") (pin "6") (pinfunction "C_6") (pintype "passive"))
      (node (ref "R67") (pin "1") (pinfunction "1_1") (pintype "passive"))
      (node (ref "R70") (pin "2") (pinfunction "2_2") (pintype "passive"))
      (node (ref "R75") (pin "1") (pinfunction "1_1") (pintype "passive"))
      (node (ref "R76") (pin "1") (pinfunction "1_1") (pintype "passive"))
      (node (ref "U8") (pin "12") (pinfunction "EN3_12") (pintype "input"))
      (node (ref "U8") (pin "13") (pinfunction "EN2_13") (pintype "input"))
    )
    (net (code "83") (name "FLASH-CS#") (class "Default")
      (node (ref "R7") (pin "1") (pinfunction "1_1") (pintype "passive"))
      (node (ref "U1") (pin "K19") (pinfunction "1_K19") (pintype "bidirectional"))
      (node (ref "U4") (pin "1") (pinfunction "1_1") (pintype "input"))
    )
    (net (code "84") (name "FLASH-D00") (class "Default")
      (node (ref "U1") (pin "D18") (pinfunction "1_D18") (pintype "bidirectional"))
      (node (ref "U4") (pin "5") (pinfunction "1_5") (pintype "input"))
    )
    (net (code "85") (name "FLASH-D01") (class "Default")
      (node (ref "U1") (pin "D19") (pinfunction "1_D19") (pintype "bidirectional"))
      (node (ref "U4") (pin "2") (pinfunction "1_2") (pintype "output"))
    )
    (net (code "86") (name "FLASH-D02") (class "Default")
      (node (ref "R2") (pin "1") (pinfunction "1_1") (pintype "passive"))
      (node (ref "U1") (pin "G18") (pinfunction "1_G18") (pintype "bidirectional"))
      (node (ref "U4") (pin "3") (pinfunction "1_3") (pintype "input"))
    )
    (net (code "87") (name "FLASH-D03") (class "Default")
      (node (ref "R6") (pin "1") (pinfunction "1_1") (pintype "passive"))
      (node (ref "U1") (pin "F18") (pinfunction "1_F18") (pintype "bidirectional"))
      (node (ref "U4") (pin "7") (pinfunction "1_7") (pintype "input"))
    )
    (net (code "88") (name "FPGA-CCLK") (class "Default")
      (node (ref "U1") (pin "C11") (pinfunction "1_C11") (pintype "bidirectional"))
      (node (ref "U4") (pin "6") (pinfunction "1_6") (pintype "input"))
    )
    (net (code "89") (name "FPGA-DONE") (class "Default")
      (node (ref "R38") (pin "2") (pinfunction "2_2") (pintype "passive"))
      (node (ref "U1") (pin "U12") (pinfunction "1_U12") (pintype "input"))
    )
    (net (code "90") (name "FPGA-INIT#") (class "Default")
      (node (ref "R1") (pin "1") (pinfunction "1_1") (pintype "passive"))
      (node (ref "U1") (pin "U11") (pinfunction "1_U11") (pintype "input"))
    )
    (net (code "91") (name "FPGA-TCK") (class "Default")
      (node (ref "R36") (pin "2") (pinfunction "2_2") (pintype "passive"))
      (node (ref "R5") (pin "2") (pinfunction "2_2") (pintype "passive"))
      (node (ref "U1") (pin "C8") (pinfunction "1_C8") (pintype "input"))
    )
    (net (code "92") (name "FPGA-TDI") (class "Default")
      (node (ref "R8") (pin "2") (pinfunction "2_2") (pintype "passive"))
      (node (ref "U1") (pin "W10") (pinfunction "1_W10") (pintype "input"))
    )
    (net (code "93") (name "FPGA-TDO") (class "Default")
      (node (ref "R37") (pin "2") (pinfunction "2_2") (pintype "passive"))
      (node (ref "U1") (pin "W8") (pinfunction "1_W8") (pintype "input"))
    )
    (net (code "94") (name "FPGA-TMS") (class "Default")
      (node (ref "R4") (pin "2") (pinfunction "2_2") (pintype "passive"))
      (node (ref "U1") (pin "W9") (pinfunction "1_W9") (pintype "input"))
    )
    (net (code "95") (name "FT-PWREN#") (class "Default")
      (node (ref "U1") (pin "P17") (pinfunction "1_P17") (pintype "input"))
      (node (ref "U2") (pin "60") (pinfunction "PWREN#_60") (pintype "bidirectional"))
    )
    (net (code "96") (name "FT-REF") (class "Default")
      (node (ref "R18") (pin "2") (pinfunction "2_2") (pintype "passive"))
      (node (ref "U2") (pin "6") (pinfunction "REF_6") (pintype "bidirectional"))
    )
    (net (code "97") (name "FT-RESETN") (class "Default")
      (node (ref "R19") (pin "1") (pinfunction "1_1") (pintype "passive"))
      (node (ref "U2") (pin "14") (pinfunction "RESET#_14") (pintype "bidirectional"))
    )
    (net (code "98") (name "FT-VCORE") (class "Default")
      (node (ref "C139") (pin "2") (pinfunction "2_2") (pintype "passive"))
      (node (ref "C39") (pin "2") (pinfunction "2_2") (pintype "passive"))
      (node (ref "U2") (pin "12") (pinfunction "VCORE_12") (pintype "bidirectional"))
      (node (ref "U2") (pin "37") (pinfunction "VCORE_37") (pintype "bidirectional"))
      (node (ref "U2") (pin "49") (pinfunction "VREGOUT_49") (pintype "bidirectional"))
      (node (ref "U2") (pin "64") (pinfunction "VCORE_64") (pintype "bidirectional"))
    )
    (net (code "99") (name "FT-VPHY") (class "Default")
      (node (ref "C40") (pin "2") (pinfunction "2_2") (pintype "passive"))
      (node (ref "L4") (pin "1") (pinfunction "1_1") (pintype "passive"))
      (node (ref "U2") (pin "4") (pinfunction "VPHY_4") (pintype "bidirectional"))
    )
    (net (code "100") (name "FT-VPLL") (class "Default")
      (node (ref "C41") (pin "2") (pinfunction "2_2") (pintype "passive"))
      (node (ref "L5") (pin "1") (pinfunction "1_1") (pintype "passive"))
      (node (ref "U2") (pin "9") (pinfunction "VPLL_9") (pintype "bidirectional"))
    )
    (net (code "101") (name "GND") (class "Default")
      (node (ref "C100") (pin "2") (pinfunction "2_2") (pintype "passive"))
      (node (ref "C101") (pin "2") (pinfunction "2_2") (pintype "passive"))
      (node (ref "C102") (pin "2") (pinfunction "2_2") (pintype "passive"))
      (node (ref "C103") (pin "2") (pinfunction "2_2") (pintype "passive"))
      (node (ref "C104") (pin "2") (pinfunction "2_2") (pintype "passive"))
      (node (ref "C105") (pin "2") (pinfunction "2_2") (pintype "passive"))
      (node (ref "C106") (pin "2") (pinfunction "2_2") (pintype "passive"))
      (node (ref "C107") (pin "2") (pinfunction "2_2") (pintype "passive"))
      (node (ref "C108") (pin "2") (pinfunction "2_2") (pintype "passive"))
      (node (ref "C109") (pin "2") (pinfunction "2_2") (pintype "passive"))
      (node (ref "C11") (pin "1") (pinfunction "1_1") (pintype "passive"))
      (node (ref "C110") (pin "2") (pinfunction "2_2") (pintype "passive"))
      (node (ref "C111") (pin "2") (pinfunction "2_2") (pintype "passive"))
      (node (ref "C112") (pin "2") (pinfunction "2_2") (pintype "passive"))
      (node (ref "C113") (pin "2") (pinfunction "2_2") (pintype "passive"))
      (node (ref "C114") (pin "2") (pinfunction "2_2") (pintype "passive"))
      (node (ref "C115") (pin "2") (pinfunction "2_2") (pintype "passive"))
      (node (ref "C116") (pin "2") (pinfunction "2_2") (pintype "passive"))
      (node (ref "C117") (pin "2") (pinfunction "2_2") (pintype "passive"))
      (node (ref "C118") (pin "2") (pinfunction "2_2") (pintype "passive"))
      (node (ref "C119") (pin "2") (pinfunction "2_2") (pintype "passive"))
      (node (ref "C12") (pin "1") (pinfunction "1_1") (pintype "passive"))
      (node (ref "C120") (pin "2") (pinfunction "2_2") (pintype "passive"))
      (node (ref "C121") (pin "2") (pinfunction "2_2") (pintype "passive"))
      (node (ref "C122") (pin "2") (pinfunction "2_2") (pintype "passive"))
      (node (ref "C124") (pin "2") (pinfunction "2_2") (pintype "passive"))
      (node (ref "C13") (pin "1") (pinfunction "1_1") (pintype "passive"))
      (node (ref "C133") (pin "1") (pinfunction "1_1") (pintype "passive"))
      (node (ref "C134") (pin "1") (pinfunction "1_1") (pintype "passive"))
      (node (ref "C135") (pin "1") (pinfunction "1_1") (pintype "passive"))
      (node (ref "C136") (pin "1") (pinfunction "1_1") (pintype "passive"))
      (node (ref "C137") (pin "1") (pinfunction "1_1") (pintype "passive"))
      (node (ref "C138") (pin "1") (pinfunction "1_1") (pintype "passive"))
      (node (ref "C139") (pin "1") (pinfunction "1_1") (pintype "passive"))
      (node (ref "C140") (pin "2") (pinfunction "2_2") (pintype "passive"))
      (node (ref "C141") (pin "2") (pinfunction "2_2") (pintype "passive"))
      (node (ref "C142") (pin "2") (pinfunction "2_2") (pintype "passive"))
      (node (ref "C143") (pin "2") (pinfunction "2_2") (pintype "passive"))
      (node (ref "C144") (pin "2") (pinfunction "2_2") (pintype "passive"))
      (node (ref "C145") (pin "2") (pinfunction "2_2") (pintype "passive"))
      (node (ref "C146") (pin "2") (pinfunction "2_2") (pintype "passive"))
      (node (ref "C3") (pin "1") (pinfunction "1_1") (pintype "passive"))
      (node (ref "C38") (pin "1") (pinfunction "1_1") (pintype "passive"))
      (node (ref "C39") (pin "1") (pinfunction "1_1") (pintype "passive"))
      (node (ref "C4") (pin "1") (pinfunction "1_1") (pintype "passive"))
      (node (ref "C40") (pin "1") (pinfunction "1_1") (pintype "passive"))
      (node (ref "C41") (pin "1") (pinfunction "1_1") (pintype "passive"))
      (node (ref "C5") (pin "1") (pinfunction "1_1") (pintype "passive"))
      (node (ref "C6") (pin "1") (pinfunction "1_1") (pintype "passive"))
      (node (ref "C7") (pin "1") (pinfunction "1_1") (pintype "passive"))
      (node (ref "C78") (pin "1") (pinfunction "1_1") (pintype "passive"))
      (node (ref "C8") (pin "1") (pinfunction "1_1") (pintype "passive"))
      (node (ref "C80") (pin "1") (pinfunction "1_1") (pintype "passive"))
      (node (ref "C82") (pin "1") (pinfunction "1_1") (pintype "passive"))
      (node (ref "C84") (pin "1") (pinfunction "1_1") (pintype "passive"))
      (node (ref "C85") (pin "2") (pinfunction "2_2") (pintype "passive"))
      (node (ref "C86") (pin "2") (pinfunction "2_2") (pintype "passive"))
      (node (ref "C87") (pin "2") (pinfunction "2_2") (pintype "passive"))
      (node (ref "C88") (pin "2") (pinfunction "2_2") (pintype "passive"))
      (node (ref "C89") (pin "2") (pinfunction "2_2") (pintype "passive"))
      (node (ref "C9") (pin "1") (pinfunction "1_1") (pintype "passive"))
      (node (ref "C90") (pin "2") (pinfunction "2_2") (pintype "passive"))
      (node (ref "C91") (pin "2") (pinfunction "2_2") (pintype "passive"))
      (node (ref "C92") (pin "2") (pinfunction "2_2") (pintype "passive"))
      (node (ref "C93") (pin "2") (pinfunction "2_2") (pintype "passive"))
      (node (ref "C94") (pin "2") (pinfunction "2_2") (pintype "passive"))
      (node (ref "C95") (pin "2") (pinfunction "2_2") (pintype "passive"))
      (node (ref "C96") (pin "2") (pinfunction "2_2") (pintype "passive"))
      (node (ref "C97") (pin "2") (pinfunction "2_2") (pintype "passive"))
      (node (ref "C98") (pin "2") (pinfunction "2_2") (pintype "passive"))
      (node (ref "C99") (pin "2") (pinfunction "2_2") (pintype "passive"))
      (node (ref "D3") (pin "A") (pinfunction "A_A") (pintype "passive"))
      (node (ref "J1") (pin "11") (pinfunction "11_11") (pintype "passive"))
      (node (ref "J1") (pin "5") (pinfunction "5_5") (pintype "passive"))
      (node (ref "JP3") (pin "3") (pinfunction "3_3") (pintype "passive"))
      (node (ref "L6") (pin "1") (pinfunction "1_1") (pintype "passive"))
      (node (ref "LD1") (pin "K") (pinfunction "K_K") (pintype "passive"))
      (node (ref "LD2") (pin "K") (pinfunction "K_K") (pintype "passive"))
      (node (ref "Q1") (pin "2") (pinfunction "2_2") (pintype "passive"))
      (node (ref "Q2") (pin "S") (pinfunction "S_S") (pintype "passive"))
      (node (ref "Q3") (pin "2") (pinfunction "E_2") (pintype "passive"))
      (node (ref "Q3") (pin "3") (pinfunction "E_3") (pintype "passive"))
      (node (ref "R11") (pin "1") (pinfunction "1_1") (pintype "passive"))
      (node (ref "R13") (pin "2") (pinfunction "2_2") (pintype "passive"))
      (node (ref "R15") (pin "1") (pinfunction "1_1") (pintype "passive"))
      (node (ref "R17") (pin "2") (pinfunction "2_2") (pintype "passive"))
      (node (ref "R18") (pin "1") (pinfunction "1_1") (pintype "passive"))
      (node (ref "R21") (pin "1") (pinfunction "1_1") (pintype "passive"))
      (node (ref "R22") (pin "1") (pinfunction "1_1") (pintype "passive"))
      (node (ref "R3") (pin "2") (pinfunction "2_2") (pintype "passive"))
      (node (ref "R5") (pin "1") (pinfunction "1_1") (pintype "passive"))
      (node (ref "R66") (pin "1") (pinfunction "1_1") (pintype "passive"))
      (node (ref "R69") (pin "1") (pinfunction "1_1") (pintype "passive"))
      (node (ref "R70") (pin "1") (pinfunction "1_1") (pintype "passive"))
      (node (ref "R73") (pin "1") (pinfunction "1_1") (pintype "passive"))
      (node (ref "R74") (pin "1") (pinfunction "1_1") (pintype "passive"))
      (node (ref "R86") (pin "1") (pinfunction "1_1") (pintype "passive"))
      (node (ref "U1") (pin "A1") (pinfunction "GND_A1") (pintype "power_in"))
      (node (ref "U1") (pin "A11") (pinfunction "1_A11") (pintype "input"))
      (node (ref "U1") (pin "A19") (pinfunction "GND_A19") (pintype "power_in"))
      (node (ref "U1") (pin "A3") (pinfunction "GND_A3") (pintype "power_in"))
      (node (ref "U1") (pin "A4") (pinfunction "1_A4") (pintype "input"))
      (node (ref "U1") (pin "A5") (pinfunction "GND_A5") (pintype "power_in"))
      (node (ref "U1") (pin "A6") (pinfunction "1_A6") (pintype "input"))
      (node (ref "U1") (pin "A7") (pinfunction "GND_A7") (pintype "power_in"))
      (node (ref "U1") (pin "A9") (pinfunction "GND_A9") (pintype "power_in"))
      (node (ref "U1") (pin "B1") (pinfunction "MGTAVTT_B1") (pintype "power_in"))
      (node (ref "U1") (pin "B11") (pinfunction "1_B11") (pintype "input"))
      (node (ref "U1") (pin "B14") (pinfunction "GND_B14") (pintype "power_in"))
      (node (ref "U1") (pin "B3") (pinfunction "GND_B3") (pintype "power_in"))
      (node (ref "U1") (pin "B4") (pinfunction "1_B4") (pintype "input"))
      (node (ref "U1") (pin "B5") (pinfunction "GND_B5") (pintype "power_in"))
      (node (ref "U1") (pin "B6") (pinfunction "1_B6") (pintype "input"))
      (node (ref "U1") (pin "B7") (pinfunction "GND_B7") (pintype "power_in"))
      (node (ref "U1") (pin "B9") (pinfunction "GND_B9") (pintype "power_in"))
      (node (ref "U1") (pin "C1") (pinfunction "MGTAVCC_C1") (pintype "power_in"))
      (node (ref "U1") (pin "C10") (pinfunction "GND_C10") (pintype "power_in"))
      (node (ref "U1") (pin "C19") (pinfunction "GND_C19") (pintype "power_in"))
      (node (ref "U1") (pin "C2") (pinfunction "GND_C2") (pintype "power_in"))
      (node (ref "U1") (pin "C3") (pinfunction "GND_C3") (pintype "power_in"))
      (node (ref "U1") (pin "C4") (pinfunction "GND_C4") (pintype "power_in"))
      (node (ref "U1") (pin "C5") (pinfunction "MGTAVTT_C5") (pintype "power_in"))
      (node (ref "U1") (pin "C6") (pinfunction "GND_C6") (pintype "power_in"))
      (node (ref "U1") (pin "C7") (pinfunction "MGTRREF_C7") (pintype "power_in"))
      (node (ref "U1") (pin "D3") (pinfunction "GND_D3") (pintype "power_in"))
      (node (ref "U1") (pin "E1") (pinfunction "MGTAVCC_E1") (pintype "power_in"))
      (node (ref "U1") (pin "E17") (pinfunction "GND_E17") (pintype "power_in"))
      (node (ref "U1") (pin "E2") (pinfunction "MGTAVTT_E2") (pintype "power_in"))
      (node (ref "U1") (pin "E3") (pinfunction "GND_E3") (pintype "power_in"))
      (node (ref "U1") (pin "F1") (pinfunction "GND_F1") (pintype "power_in"))
      (node (ref "U1") (pin "F19") (pinfunction "GND_F19") (pintype "power_in"))
      (node (ref "U1") (pin "F2") (pinfunction "GND_F2") (pintype "power_in"))
      (node (ref "U1") (pin "F3") (pinfunction "MGTAVCC_F3") (pintype "power_in"))
      (node (ref "U1") (pin "G1") (pinfunction "GND_G1") (pintype "power_in"))
      (node (ref "U1") (pin "G11") (pinfunction "GND_G11") (pintype "power_in"))
      (node (ref "U1") (pin "G7") (pinfunction "MGTAVTT_G7") (pintype "power_in"))
      (node (ref "U1") (pin "G8") (pinfunction "GND_G8") (pintype "power_in"))
      (node (ref "U1") (pin "G9") (pinfunction "MGTAVCC_G9") (pintype "power_in"))
      (node (ref "U1") (pin "H11") (pinfunction "GND_H11") (pintype "power_in"))
      (node (ref "U1") (pin "H12") (pinfunction "GND_H12") (pintype "power_in"))
      (node (ref "U1") (pin "H18") (pinfunction "GND_H18") (pintype "power_in"))
      (node (ref "U1") (pin "H7") (pinfunction "GND_H7") (pintype "power_in"))
      (node (ref "U1") (pin "H8") (pinfunction "GND_H8") (pintype "power_in"))
      (node (ref "U1") (pin "H9") (pinfunction "MGTAVCC_H9") (pintype "power_in"))
      (node (ref "U1") (pin "J11") (pinfunction "GND_J11") (pintype "power_in"))
      (node (ref "U1") (pin "J12") (pinfunction "GND_J12") (pintype "power_in"))
      (node (ref "U1") (pin "J8") (pinfunction "GND_J8") (pintype "power_in"))
      (node (ref "U1") (pin "J9") (pinfunction "GND_J9") (pintype "power_in"))
      (node (ref "U1") (pin "K8") (pinfunction "GND_K8") (pintype "power_in"))
      (node (ref "U1") (pin "L11") (pinfunction "GND_L11") (pintype "power_in"))
      (node (ref "U1") (pin "L19") (pinfunction "GND_L19") (pintype "power_in"))
      (node (ref "U1") (pin "L8") (pinfunction "GND_L8") (pintype "power_in"))
      (node (ref "U1") (pin "L9") (pinfunction "GND_L9") (pintype "power_in"))
      (node (ref "U1") (pin "M13") (pinfunction "GND_M13") (pintype "power_in"))
      (node (ref "U1") (pin "M9") (pinfunction "GND_M9") (pintype "power_in"))
      (node (ref "U1") (pin "N12") (pinfunction "GND_N12") (pintype "power_in"))
      (node (ref "U1") (pin "N13") (pinfunction "GND_N13") (pintype "power_in"))
      (node (ref "U1") (pin "N9") (pinfunction "GND_N9") (pintype "power_in"))
      (node (ref "U1") (pin "P2") (pinfunction "GND_P2") (pintype "power_in"))
      (node (ref "U1") (pin "T19") (pinfunction "GND_T19") (pintype "power_in"))
      (node (ref "U1") (pin "U6") (pinfunction "GND_U6") (pintype "power_in"))
      (node (ref "U1") (pin "U9") (pinfunction "GND_U9") (pintype "power_in"))
      (node (ref "U1") (pin "V18") (pinfunction "GND_V18") (pintype "power_in"))
      (node (ref "U1") (pin "W1") (pinfunction "GND_W1") (pintype "power_in"))
      (node (ref "U1") (pin "W12") (pinfunction "GND_W12") (pintype "power_in"))
      (node (ref "U10") (pin "5") (pinfunction "VSS_5") (pintype "bidirectional"))
      (node (ref "U2") (pin "1") (pinfunction "GND_1") (pintype "bidirectional"))
      (node (ref "U2") (pin "10") (pinfunction "AGND_10") (pintype "bidirectional"))
      (node (ref "U2") (pin "11") (pinfunction "GND_11") (pintype "bidirectional"))
      (node (ref "U2") (pin "13") (pinfunction "TEST_13") (pintype "bidirectional"))
      (node (ref "U2") (pin "15") (pinfunction "GND_15") (pintype "bidirectional"))
      (node (ref "U2") (pin "25") (pinfunction "GND_25") (pintype "bidirectional"))
      (node (ref "U2") (pin "35") (pinfunction "GND_35") (pintype "bidirectional"))
      (node (ref "U2") (pin "47") (pinfunction "GND_47") (pintype "bidirectional"))
      (node (ref "U2") (pin "5") (pinfunction "GND_5") (pintype "bidirectional"))
      (node (ref "U2") (pin "51") (pinfunction "GND_51") (pintype "bidirectional"))
      (node (ref "U2") (pin "EP") (pinfunction "EP_EP") (pintype "bidirectional"))
      (node (ref "U3") (pin "12") (pinfunction "P$1_12") (pintype "bidirectional"))
      (node (ref "U3") (pin "28") (pinfunction "P$1_28") (pintype "bidirectional"))
      (node (ref "U3") (pin "41") (pinfunction "P$1_41") (pintype "bidirectional"))
      (node (ref "U3") (pin "46") (pinfunction "P$1_46") (pintype "bidirectional"))
      (node (ref "U3") (pin "52") (pinfunction "P$1_52") (pintype "bidirectional"))
      (node (ref "U3") (pin "54") (pinfunction "P$1_54") (pintype "bidirectional"))
      (node (ref "U3") (pin "6") (pinfunction "P$1_6") (pintype "bidirectional"))
      (node (ref "U4") (pin "4") (pinfunction "1_4") (pintype "input"))
      (node (ref "U8") (pin "1") (pinfunction "PGND2_1") (pintype "passive"))
      (node (ref "U8") (pin "11") (pinfunction "SGND_11") (pintype "passive"))
      (node (ref "U8") (pin "15") (pinfunction "PGND3_15") (pintype "passive"))
      (node (ref "U8") (pin "20") (pinfunction "PGND1_20") (pintype "passive"))
      (node (ref "U8") (pin "21") (pinfunction "GND_21") (pintype "passive"))
      (node (ref "X1") (pin "5") (pinfunction "5-GND_5") (pintype "input"))
      (node (ref "X1") (pin "MH1") (pinfunction "5-GND_MH1") (pintype "input"))
      (node (ref "X1") (pin "MH2") (pinfunction "5-GND_MH2") (pintype "input"))
      (node (ref "X1") (pin "MP1") (pinfunction "5-GND_MP1") (pintype "input"))
      (node (ref "X1") (pin "MP2") (pinfunction "5-GND_MP2") (pintype "input"))
      (node (ref "X1") (pin "MP3") (pinfunction "5-GND_MP3") (pintype "input"))
      (node (ref "X1") (pin "MP4") (pinfunction "5-GND_MP4") (pintype "input"))
      (node (ref "X1") (pin "MS1") (pinfunction "5-GND_MS1") (pintype "input"))
      (node (ref "X1") (pin "MS2") (pinfunction "5-GND_MS2") (pintype "input"))
      (node (ref "X2") (pin "1") (pinfunction "1_1") (pintype "bidirectional"))
      (node (ref "X2") (pin "20") (pinfunction "1_20") (pintype "bidirectional"))
      (node (ref "X2") (pin "21") (pinfunction "1_21") (pintype "bidirectional"))
      (node (ref "X2") (pin "23") (pinfunction "1_23") (pintype "bidirectional"))
      (node (ref "X2") (pin "3") (pinfunction "1_3") (pintype "bidirectional"))
      (node (ref "X3") (pin "6") (pinfunction "GND_6") (pintype "passive"))
      (node (ref "X3") (pin "G1") (pinfunction "GND_G1") (pintype "passive"))
      (node (ref "X3") (pin "G2") (pinfunction "GND_G2") (pintype "passive"))
      (node (ref "X3") (pin "G3") (pinfunction "GND_G3") (pintype "passive"))
      (node (ref "X3") (pin "G4") (pinfunction "GND_G4") (pintype "passive"))
    )
    (net (code "102") (name "GNDADC") (class "Default")
      (node (ref "C123") (pin "2") (pinfunction "2_2") (pintype "passive"))
      (node (ref "L6") (pin "2") (pinfunction "2_2") (pintype "passive"))
      (node (ref "U1") (pin "A12") (pinfunction "1_A12") (pintype "input"))
      (node (ref "U1") (pin "A13") (pinfunction "1_A13") (pintype "input"))
      (node (ref "U1") (pin "B12") (pinfunction "1_B12") (pintype "input"))
      (node (ref "U1") (pin "B13") (pinfunction "1_B13") (pintype "input"))
      (node (ref "U1") (pin "C12") (pinfunction "1_C12") (pintype "input"))
    )
    (net (code "103") (name "JA1") (class "Default")
      (node (ref "R26") (pin "1") (pinfunction "1_1") (pintype "passive"))
      (node (ref "U1") (pin "U18") (pinfunction "1_U18") (pintype "input"))
    )
    (net (code "104") (name "JA2") (class "Default")
      (node (ref "R27") (pin "1") (pinfunction "1_1") (pintype "passive"))
      (node (ref "U1") (pin "U19") (pinfunction "1_U19") (pintype "input"))
    )
    (net (code "105") (name "JA3") (class "Default")
      (node (ref "R28") (pin "1") (pinfunction "1_1") (pintype "passive"))
      (node (ref "U1") (pin "G17") (pinfunction "1_G17") (pintype "input"))
    )
    (net (code "106") (name "JA4") (class "Default")
      (node (ref "R29") (pin "1") (pinfunction "1_1") (pintype "passive"))
      (node (ref "U1") (pin "C17") (pinfunction "1_C17") (pintype "input"))
    )
    (net (code "107") (name "JA7") (class "Default")
      (node (ref "R30") (pin "2") (pinfunction "2_2") (pintype "passive"))
      (node (ref "U1") (pin "T17") (pinfunction "1_T17") (pintype "input"))
    )
    (net (code "108") (name "JA8") (class "Default")
      (node (ref "R31") (pin "2") (pinfunction "2_2") (pintype "passive"))
      (node (ref "U1") (pin "E19") (pinfunction "1_E19") (pintype "input"))
    )
    (net (code "109") (name "JA9") (class "Default")
      (node (ref "R32") (pin "2") (pinfunction "2_2") (pintype "passive"))
      (node (ref "U1") (pin "V19") (pinfunction "1_V19") (pintype "input"))
    )
    (net (code "110") (name "JA10") (class "Default")
      (node (ref "R33") (pin "2") (pinfunction "2_2") (pintype "passive"))
      (node (ref "U1") (pin "U17") (pinfunction "1_U17") (pintype "bidirectional"))
    )
    (net (code "111") (name "LD5_K") (class "Default")
      (node (ref "LD5") (pin "K") (pinfunction "K_K") (pintype "passive"))
      (node (ref "R78") (pin "2") (pinfunction "2_2") (pintype "passive"))
    )
    (net (code "112") (name "LD5_TO_Q2") (class "Default")
      (node (ref "Q2") (pin "D") (pinfunction "D_D") (pintype "passive"))
      (node (ref "R78") (pin "1") (pinfunction "1_1") (pintype "passive"))
    )
    (net (code "113") (name "LDQM") (class "Default")
      (node (ref "U1") (pin "W4") (pinfunction "1_W4") (pintype "bidirectional"))
      (node (ref "U3") (pin "15") (pinfunction "P$1_15") (pintype "bidirectional"))
    )
    (net (code "114") (name "LED0_B") (class "Default")
      (node (ref "LD0") (pin "1") (pinfunction "1_1") (pintype "passive"))
      (node (ref "U1") (pin "N19") (pinfunction "1_N19") (pintype "input"))
    )
    (net (code "115") (name "LED0_G") (class "Default")
      (node (ref "LD0") (pin "3") (pinfunction "3_3") (pintype "passive"))
      (node (ref "U1") (pin "R18") (pinfunction "1_R18") (pintype "input"))
    )
    (net (code "116") (name "LED0_R") (class "Default")
      (node (ref "LD0") (pin "2") (pinfunction "2_2") (pintype "passive"))
      (node (ref "U1") (pin "P19") (pinfunction "1_P19") (pintype "input"))
    )
    (net (code "117") (name "LED1") (class "Default")
      (node (ref "R83") (pin "1") (pinfunction "1_1") (pintype "passive"))
      (node (ref "U1") (pin "N18") (pinfunction "1_N18") (pintype "input"))
    )
    (net (code "118") (name "LED2") (class "Default")
      (node (ref "R84") (pin "1") (pinfunction "1_1") (pintype "passive"))
      (node (ref "U1") (pin "M19") (pinfunction "1_M19") (pintype "input"))
    )
    (net (code "119") (name "MODE_NET") (class "Default")
      (node (ref "R72") (pin "1") (pinfunction "1_1") (pintype "passive"))
      (node (ref "R74") (pin "2") (pinfunction "2_2") (pintype "passive"))
      (node (ref "U8") (pin "5") (pinfunction "MODE_5") (pintype "input"))
    )
    (net (code "120") (name "Net-(BTN-2-Pad3)") (class "Default")
      (node (ref "BTN") (pin "3") (pinfunction "2_3") (pintype "passive"))
      (node (ref "BTN") (pin "4") (pinfunction "2_4") (pintype "passive"))
      (node (ref "R85") (pin "1") (pinfunction "1_1") (pintype "passive"))
      (node (ref "R86") (pin "2") (pinfunction "2_2") (pintype "passive"))
    )
    (net (code "121") (name "Net-(J1-Pad1)") (class "Default")
      (node (ref "J1") (pin "1") (pinfunction "1_1") (pintype "passive"))
      (node (ref "R26") (pin "2") (pinfunction "2_2") (pintype "passive"))
    )
    (net (code "122") (name "Net-(J1-Pad2)") (class "Default")
      (node (ref "J1") (pin "2") (pinfunction "2_2") (pintype "passive"))
      (node (ref "R27") (pin "2") (pinfunction "2_2") (pintype "passive"))
    )
    (net (code "123") (name "Net-(J1-Pad3)") (class "Default")
      (node (ref "J1") (pin "3") (pinfunction "3_3") (pintype "passive"))
      (node (ref "R28") (pin "2") (pinfunction "2_2") (pintype "passive"))
    )
    (net (code "124") (name "Net-(J1-Pad4)") (class "Default")
      (node (ref "J1") (pin "4") (pinfunction "4_4") (pintype "passive"))
      (node (ref "R29") (pin "2") (pinfunction "2_2") (pintype "passive"))
    )
    (net (code "125") (name "Net-(J1-Pad7)") (class "Default")
      (node (ref "J1") (pin "7") (pinfunction "7_7") (pintype "passive"))
      (node (ref "R30") (pin "1") (pinfunction "1_1") (pintype "passive"))
    )
    (net (code "126") (name "Net-(J1-Pad8)") (class "Default")
      (node (ref "J1") (pin "8") (pinfunction "8_8") (pintype "passive"))
      (node (ref "R31") (pin "1") (pinfunction "1_1") (pintype "passive"))
    )
    (net (code "127") (name "Net-(J1-Pad9)") (class "Default")
      (node (ref "J1") (pin "9") (pinfunction "9_9") (pintype "passive"))
      (node (ref "R32") (pin "1") (pinfunction "1_1") (pintype "passive"))
    )
    (net (code "128") (name "Net-(J1-Pad10)") (class "Default")
      (node (ref "J1") (pin "10") (pinfunction "10_10") (pintype "passive"))
      (node (ref "R33") (pin "1") (pinfunction "1_1") (pintype "passive"))
    )
    (net (code "129") (name "Net-(LD0-Pad4)") (class "Default")
      (node (ref "LD0") (pin "4") (pinfunction "4_4") (pintype "passive"))
      (node (ref "R80") (pin "2") (pinfunction "2_2") (pintype "passive"))
    )
    (net (code "130") (name "Net-(LD0-Pad5)") (class "Default")
      (node (ref "LD0") (pin "5") (pinfunction "5_5") (pintype "passive"))
      (node (ref "R81") (pin "2") (pinfunction "2_2") (pintype "passive"))
    )
    (net (code "131") (name "Net-(LD0-Pad6)") (class "Default")
      (node (ref "LD0") (pin "6") (pinfunction "6_6") (pintype "passive"))
      (node (ref "R82") (pin "2") (pinfunction "2_2") (pintype "passive"))
    )
    (net (code "132") (name "Net-(LD1-PadA)") (class "Default")
      (node (ref "LD1") (pin "A") (pinfunction "A_A") (pintype "passive"))
      (node (ref "R83") (pin "2") (pinfunction "2_2") (pintype "passive"))
    )
    (net (code "133") (name "Net-(LD2-PadA)") (class "Default")
      (node (ref "LD2") (pin "A") (pinfunction "A_A") (pintype "passive"))
      (node (ref "R84") (pin "2") (pinfunction "2_2") (pintype "passive"))
    )
    (net (code "134") (name "Net-(R10-Pad1)") (class "Default")
      (node (ref "R10") (pin "1") (pinfunction "1_1") (pintype "passive"))
      (node (ref "R11") (pin "2") (pinfunction "2_2") (pintype "passive"))
      (node (ref "R12") (pin "2") (pinfunction "2_2") (pintype "passive"))
    )
    (net (code "135") (name "Net-(R14-Pad1)") (class "Default")
      (node (ref "R14") (pin "1") (pinfunction "1_1") (pintype "passive"))
      (node (ref "R15") (pin "2") (pinfunction "2_2") (pintype "passive"))
      (node (ref "R16") (pin "2") (pinfunction "2_2") (pintype "passive"))
    )
    (net (code "136") (name "Net-(U8-FB1)") (class "Default")
      (node (ref "C79") (pin "1") (pinfunction "1_1") (pintype "passive"))
      (node (ref "R65") (pin "1") (pinfunction "1_1") (pintype "passive"))
      (node (ref "R66") (pin "2") (pinfunction "2_2") (pintype "passive"))
      (node (ref "U8") (pin "8") (pinfunction "FB1_8") (pintype "passive"))
    )
    (net (code "137") (name "Net-(U8-FB2)") (class "Default")
      (node (ref "C81") (pin "1") (pinfunction "1_1") (pintype "passive"))
      (node (ref "R68") (pin "1") (pinfunction "1_1") (pintype "passive"))
      (node (ref "R69") (pin "2") (pinfunction "2_2") (pintype "passive"))
      (node (ref "U8") (pin "7") (pinfunction "FB2_7") (pintype "passive"))
    )
    (net (code "138") (name "Net-(U8-FB3)") (class "Default")
      (node (ref "C83") (pin "1") (pinfunction "1_1") (pintype "passive"))
      (node (ref "R71") (pin "1") (pinfunction "1_1") (pintype "passive"))
      (node (ref "R73") (pin "2") (pinfunction "2_2") (pintype "passive"))
      (node (ref "U8") (pin "9") (pinfunction "FB3_9") (pintype "passive"))
    )
    (net (code "139") (name "Net-(U8-SW1)") (class "Default")
      (node (ref "L1") (pin "1") (pinfunction "1_1") (pintype "passive"))
      (node (ref "U8") (pin "19") (pinfunction "SW1_19") (pintype "passive"))
    )
    (net (code "140") (name "Net-(U8-SW2)") (class "Default")
      (node (ref "L2") (pin "1") (pinfunction "1_1") (pintype "passive"))
      (node (ref "U8") (pin "2") (pinfunction "SW2_2") (pintype "passive"))
    )
    (net (code "141") (name "Net-(U8-SW3)") (class "Default")
      (node (ref "L3") (pin "1") (pinfunction "1_1") (pintype "passive"))
      (node (ref "U8") (pin "16") (pinfunction "SW3_16") (pintype "passive"))
    )
    (net (code "142") (name "PGOOD") (class "Default")
      (node (ref "Q2") (pin "G") (pinfunction "G_G") (pintype "input"))
      (node (ref "R77") (pin "1") (pinfunction "1_1") (pintype "passive"))
      (node (ref "U8") (pin "4") (pinfunction "PGOOD_4") (pintype "input"))
    )
    (net (code "143") (name "PROG#") (class "Default")
      (node (ref "R9") (pin "1") (pinfunction "1_1") (pintype "passive"))
      (node (ref "R99") (pin "1") (pinfunction "1_1") (pintype "passive"))
      (node (ref "U2") (pin "21") (pinfunction "ADBUS4_21") (pintype "bidirectional"))
    )
    (net (code "144") (name "PUDC_B") (class "Default")
      (node (ref "R23") (pin "2") (pinfunction "2_2") (pintype "passive"))
      (node (ref "U1") (pin "E18") (pinfunction "1_E18") (pintype "input"))
    )
    (net (code "145") (name "Q3A_BASE") (class "Default")
      (node (ref "Q3") (pin "1") (pinfunction "B_1") (pintype "input"))
      (node (ref "R79") (pin "2") (pinfunction "2_2") (pintype "passive"))
    )
    (net (code "146") (name "RAS#") (class "Default")
      (node (ref "U1") (pin "V3") (pinfunction "1_V3") (pintype "bidirectional"))
      (node (ref "U3") (pin "18") (pinfunction "P$1_18") (pintype "bidirectional"))
    )
    (net (code "147") (name "RST#") (class "Default")
      (node (ref "R3") (pin "1") (pinfunction "1_1") (pintype "passive"))
      (node (ref "R9") (pin "2") (pinfunction "2_2") (pintype "passive"))
      (node (ref "U1") (pin "V10") (pinfunction "1_V10") (pintype "input"))
      (node (ref "X2") (pin "24") (pinfunction "1_24") (pintype "bidirectional"))
    )
    (net (code "148") (name "SD-CLK") (class "Default")
      (node (ref "U1") (pin "U8") (pinfunction "1_U8") (pintype "bidirectional"))
      (node (ref "X3") (pin "5") (pinfunction "CLK/SCLK_5") (pintype "input"))
    )
    (net (code "149") (name "SD-CMD") (class "Default")
      (node (ref "R35") (pin "1") (pinfunction "1_1") (pintype "passive"))
      (node (ref "U1") (pin "U7") (pinfunction "1_U7") (pintype "bidirectional"))
      (node (ref "X3") (pin "3") (pinfunction "CMD/DIN_3") (pintype "input"))
    )
    (net (code "150") (name "SD-DAT0") (class "Default")
      (node (ref "R34") (pin "1") (pinfunction "1_1") (pintype "passive"))
      (node (ref "U1") (pin "C15") (pinfunction "1_C15") (pintype "bidirectional"))
      (node (ref "X3") (pin "7") (pinfunction "DAT0/DOUT_7") (pintype "bidirectional"))
    )
    (net (code "151") (name "SD-DAT1") (class "Default")
      (node (ref "R34") (pin "2") (pinfunction "1_2") (pintype "passive"))
      (node (ref "U1") (pin "B15") (pinfunction "1_B15") (pintype "bidirectional"))
      (node (ref "X3") (pin "8") (pinfunction "DAT1/NC_8") (pintype "bidirectional"))
    )
    (net (code "152") (name "SD-DAT2") (class "Default")
      (node (ref "R34") (pin "3") (pinfunction "1_3") (pintype "passive"))
      (node (ref "U1") (pin "L3") (pinfunction "1_L3") (pintype "bidirectional"))
      (node (ref "X3") (pin "1") (pinfunction "DAT2/NC_1") (pintype "bidirectional"))
    )
    (net (code "153") (name "SD-DAT3") (class "Default")
      (node (ref "R34") (pin "4") (pinfunction "1_4") (pintype "passive"))
      (node (ref "U1") (pin "A16") (pinfunction "1_A16") (pintype "bidirectional"))
      (node (ref "X3") (pin "2") (pinfunction "DAT3_CD/CS#_2") (pintype "bidirectional"))
    )
    (net (code "154") (name "SDRAM-CLK") (class "Default")
      (node (ref "U1") (pin "M1") (pinfunction "1_M1") (pintype "bidirectional"))
      (node (ref "U3") (pin "38") (pinfunction "P$1_38") (pintype "bidirectional"))
    )
    (net (code "155") (name "SDRAM-CS#") (class "Default")
      (node (ref "U1") (pin "W2") (pinfunction "1_W2") (pintype "bidirectional"))
      (node (ref "U3") (pin "19") (pinfunction "P$1_19") (pintype "bidirectional"))
    )
    (net (code "156") (name "TCK") (class "Default")
      (node (ref "JP3") (pin "1") (pinfunction "1_1") (pintype "passive"))
      (node (ref "R36") (pin "1") (pinfunction "1_1") (pintype "passive"))
      (node (ref "R89") (pin "1") (pinfunction "1_1") (pintype "passive"))
      (node (ref "U2") (pin "16") (pinfunction "ADBUS0_16") (pintype "bidirectional"))
    )
    (net (code "157") (name "TDI") (class "Default")
      (node (ref "JP4") (pin "1") (pinfunction "1_1") (pintype "passive"))
      (node (ref "R8") (pin "1") (pinfunction "1_1") (pintype "passive"))
      (node (ref "R90") (pin "1") (pinfunction "1_1") (pintype "passive"))
      (node (ref "U2") (pin "17") (pinfunction "ADBUS1_17") (pintype "bidirectional"))
    )
    (net (code "158") (name "TDO") (class "Default")
      (node (ref "JP4") (pin "2") (pinfunction "2_2") (pintype "passive"))
      (node (ref "R37") (pin "1") (pinfunction "1_1") (pintype "passive"))
      (node (ref "R91") (pin "1") (pinfunction "1_1") (pintype "passive"))
      (node (ref "U2") (pin "18") (pinfunction "ADBUS2_18") (pintype "bidirectional"))
    )
    (net (code "159") (name "TMS") (class "Default")
      (node (ref "JP3") (pin "2") (pinfunction "2_2") (pintype "passive"))
      (node (ref "R4") (pin "1") (pinfunction "1_1") (pintype "passive"))
      (node (ref "R92") (pin "1") (pinfunction "1_1") (pintype "passive"))
      (node (ref "U2") (pin "19") (pinfunction "ADBUS3_19") (pintype "bidirectional"))
    )
    (net (code "160") (name "UART_FT_CTS#") (class "Default")
      (node (ref "R93") (pin "1") (pinfunction "1_1") (pintype "passive"))
      (node (ref "U1") (pin "B16") (pinfunction "1_B16") (pintype "output"))
      (node (ref "U2") (pin "41") (pinfunction "BDBUS3_41") (pintype "bidirectional"))
    )
    (net (code "161") (name "UART_FT_DTR#") (class "Default")
      (node (ref "U1") (pin "M18") (pinfunction "1_M18") (pintype "input"))
      (node (ref "U2") (pin "43") (pinfunction "BDBUS4_43") (pintype "bidirectional"))
    )
    (net (code "162") (name "UART_FT_RTS#") (class "Default")
      (node (ref "U1") (pin "L18") (pinfunction "1_L18") (pintype "input"))
      (node (ref "U2") (pin "40") (pinfunction "BDBUS2_40") (pintype "bidirectional"))
    )
    (net (code "163") (name "UART_FT_RXD") (class "Default")
      (node (ref "R94") (pin "1") (pinfunction "1_1") (pintype "passive"))
      (node (ref "U1") (pin "G19") (pinfunction "1_G19") (pintype "bidirectional"))
      (node (ref "U2") (pin "39") (pinfunction "BDBUS1_39") (pintype "bidirectional"))
    )
    (net (code "164") (name "UART_FT_TXD") (class "Default")
      (node (ref "U1") (pin "K18") (pinfunction "1_K18") (pintype "bidirectional"))
      (node (ref "U2") (pin "38") (pinfunction "BDBUS0_38") (pintype "bidirectional"))
    )
    (net (code "165") (name "UDQM") (class "Default")
      (node (ref "U1") (pin "L2") (pinfunction "1_L2") (pintype "bidirectional"))
      (node (ref "U3") (pin "39") (pinfunction "P$1_39") (pintype "bidirectional"))
    )
    (net (code "166") (name "USB5V0") (class "Default")
      (node (ref "D1") (pin "A") (pinfunction "A_A") (pintype "passive"))
      (node (ref "X1") (pin "1") (pinfunction "1-VCC_1") (pintype "input"))
    )
    (net (code "167") (name "USB_D_N") (class "Default")
      (node (ref "U2") (pin "7") (pinfunction "DM_7") (pintype "bidirectional"))
      (node (ref "X1") (pin "2") (pinfunction "2-D-_2") (pintype "input"))
    )
    (net (code "168") (name "USB_D_P") (class "Default")
      (node (ref "U2") (pin "8") (pinfunction "DP_8") (pintype "bidirectional"))
      (node (ref "X1") (pin "3") (pinfunction "3-D+_3") (pintype "input"))
    )
    (net (code "169") (name "VCC1V0") (class "Default")
      (node (ref "C140") (pin "1") (pinfunction "1_1") (pintype "passive"))
      (node (ref "C141") (pin "1") (pinfunction "1_1") (pintype "passive"))
      (node (ref "C142") (pin "1") (pinfunction "1_1") (pintype "passive"))
      (node (ref "C143") (pin "1") (pinfunction "1_1") (pintype "passive"))
      (node (ref "C79") (pin "2") (pinfunction "2_2") (pintype "passive"))
      (node (ref "C80") (pin "2") (pinfunction "2_2") (pintype "passive"))
      (node (ref "C85") (pin "1") (pinfunction "1_1") (pintype "passive"))
      (node (ref "C86") (pin "1") (pinfunction "1_1") (pintype "passive"))
      (node (ref "C87") (pin "1") (pinfunction "1_1") (pintype "passive"))
      (node (ref "C88") (pin "1") (pinfunction "1_1") (pintype "passive"))
      (node (ref "C89") (pin "1") (pinfunction "1_1") (pintype "passive"))
      (node (ref "C90") (pin "1") (pinfunction "1_1") (pintype "passive"))
      (node (ref "C91") (pin "1") (pinfunction "1_1") (pintype "passive"))
      (node (ref "C92") (pin "1") (pinfunction "1_1") (pintype "passive"))
      (node (ref "L1") (pin "2") (pinfunction "2_2") (pintype "passive"))
      (node (ref "R65") (pin "2") (pinfunction "2_2") (pintype "passive"))
      (node (ref "R79") (pin "1") (pinfunction "1_1") (pintype "passive"))
      (node (ref "U1") (pin "G10") (pinfunction "VCCINT_G10") (pintype "power_in"))
      (node (ref "U1") (pin "H10") (pinfunction "VCCINT_H10") (pintype "power_in"))
      (node (ref "U1") (pin "J10") (pinfunction "VCCINT_J10") (pintype "power_in"))
      (node (ref "U1") (pin "L10") (pinfunction "VCCINT_L10") (pintype "power_in"))
      (node (ref "U1") (pin "M10") (pinfunction "VCCINT_M10") (pintype "power_in"))
      (node (ref "U1") (pin "M11") (pinfunction "VCCBRAM_M11") (pintype "power_in"))
      (node (ref "U1") (pin "N10") (pinfunction "VCCINT_N10") (pintype "power_in"))
      (node (ref "U1") (pin "N11") (pinfunction "VCCBRAM_N11") (pintype "power_in"))
      (node (ref "X2") (pin "19") (pinfunction "1_19") (pintype "bidirectional"))
    )
    (net (code "170") (name "VCC1V8") (class "Default")
      (node (ref "C144") (pin "1") (pinfunction "1_1") (pintype "passive"))
      (node (ref "C81") (pin "2") (pinfunction "2_2") (pintype "passive"))
      (node (ref "C82") (pin "2") (pinfunction "2_2") (pintype "passive"))
      (node (ref "C93") (pin "1") (pinfunction "1_1") (pintype "passive"))
      (node (ref "C94") (pin "1") (pinfunction "1_1") (pintype "passive"))
      (node (ref "C95") (pin "1") (pinfunction "1_1") (pintype "passive"))
      (node (ref "C96") (pin "1") (pinfunction "1_1") (pintype "passive"))
      (node (ref "L2") (pin "2") (pinfunction "2_2") (pintype "passive"))
      (node (ref "L7") (pin "1") (pinfunction "1_1") (pintype "passive"))
      (node (ref "R67") (pin "2") (pinfunction "2_2") (pintype "passive"))
      (node (ref "R68") (pin "2") (pinfunction "2_2") (pintype "passive"))
      (node (ref "U1") (pin "C9") (pinfunction "VCCBATT_C9") (pintype "power_in"))
      (node (ref "U1") (pin "H13") (pinfunction "VCCAUX_H13") (pintype "power_in"))
      (node (ref "U1") (pin "J13") (pinfunction "VCCAUX_J13") (pintype "power_in"))
      (node (ref "X2") (pin "18") (pinfunction "1_18") (pintype "bidirectional"))
    )
    (net (code "171") (name "VCC3V3") (class "Default")
      (node (ref "BTN") (pin "1") (pinfunction "1_1") (pintype "passive"))
      (node (ref "BTN") (pin "2") (pinfunction "1_2") (pintype "passive"))
      (node (ref "C100") (pin "1") (pinfunction "1_1") (pintype "passive"))
      (node (ref "C101") (pin "1") (pinfunction "1_1") (pintype "passive"))
      (node (ref "C102") (pin "1") (pinfunction "1_1") (pintype "passive"))
      (node (ref "C103") (pin "1") (pinfunction "1_1") (pintype "passive"))
      (node (ref "C104") (pin "1") (pinfunction "1_1") (pintype "passive"))
      (node (ref "C105") (pin "1") (pinfunction "1_1") (pintype "passive"))
      (node (ref "C106") (pin "1") (pinfunction "1_1") (pintype "passive"))
      (node (ref "C107") (pin "1") (pinfunction "1_1") (pintype "passive"))
      (node (ref "C108") (pin "1") (pinfunction "1_1") (pintype "passive"))
      (node (ref "C109") (pin "1") (pinfunction "1_1") (pintype "passive"))
      (node (ref "C11") (pin "2") (pinfunction "2_2") (pintype "passive"))
      (node (ref "C110") (pin "1") (pinfunction "1_1") (pintype "passive"))
      (node (ref "C111") (pin "1") (pinfunction "1_1") (pintype "passive"))
      (node (ref "C112") (pin "1") (pinfunction "1_1") (pintype "passive"))
      (node (ref "C113") (pin "1") (pinfunction "1_1") (pintype "passive"))
      (node (ref "C114") (pin "1") (pinfunction "1_1") (pintype "passive"))
      (node (ref "C115") (pin "1") (pinfunction "1_1") (pintype "passive"))
      (node (ref "C116") (pin "1") (pinfunction "1_1") (pintype "passive"))
      (node (ref "C117") (pin "1") (pinfunction "1_1") (pintype "passive"))
      (node (ref "C118") (pin "1") (pinfunction "1_1") (pintype "passive"))
      (node (ref "C119") (pin "1") (pinfunction "1_1") (pintype "passive"))
      (node (ref "C12") (pin "2") (pinfunction "2_2") (pintype "passive"))
      (node (ref "C120") (pin "1") (pinfunction "1_1") (pintype "passive"))
      (node (ref "C121") (pin "1") (pinfunction "1_1") (pintype "passive"))
      (node (ref "C122") (pin "1") (pinfunction "1_1") (pintype "passive"))
      (node (ref "C13") (pin "2") (pinfunction "2_2") (pintype "passive"))
      (node (ref "C133") (pin "2") (pinfunction "2_2") (pintype "passive"))
      (node (ref "C134") (pin "2") (pinfunction "2_2") (pintype "passive"))
      (node (ref "C135") (pin "2") (pinfunction "2_2") (pintype "passive"))
      (node (ref "C136") (pin "2") (pinfunction "2_2") (pintype "passive"))
      (node (ref "C137") (pin "2") (pinfunction "2_2") (pintype "passive"))
      (node (ref "C138") (pin "2") (pinfunction "2_2") (pintype "passive"))
      (node (ref "C145") (pin "1") (pinfunction "1_1") (pintype "passive"))
      (node (ref "C146") (pin "1") (pinfunction "1_1") (pintype "passive"))
      (node (ref "C3") (pin "2") (pinfunction "2_2") (pintype "passive"))
      (node (ref "C38") (pin "2") (pinfunction "2_2") (pintype "passive"))
      (node (ref "C4") (pin "2") (pinfunction "2_2") (pintype "passive"))
      (node (ref "C5") (pin "2") (pinfunction "2_2") (pintype "passive"))
      (node (ref "C6") (pin "2") (pinfunction "2_2") (pintype "passive"))
      (node (ref "C7") (pin "2") (pinfunction "2_2") (pintype "passive"))
      (node (ref "C8") (pin "2") (pinfunction "2_2") (pintype "passive"))
      (node (ref "C83") (pin "2") (pinfunction "2_2") (pintype "passive"))
      (node (ref "C84") (pin "2") (pinfunction "2_2") (pintype "passive"))
      (node (ref "C9") (pin "2") (pinfunction "2_2") (pintype "passive"))
      (node (ref "C97") (pin "1") (pinfunction "1_1") (pintype "passive"))
      (node (ref "C98") (pin "1") (pinfunction "1_1") (pintype "passive"))
      (node (ref "C99") (pin "1") (pinfunction "1_1") (pintype "passive"))
      (node (ref "J1") (pin "12") (pinfunction "12_12") (pintype "passive"))
      (node (ref "J1") (pin "6") (pinfunction "6_6") (pintype "passive"))
      (node (ref "JP4") (pin "3") (pinfunction "3_3") (pintype "passive"))
      (node (ref "L3") (pin "2") (pinfunction "2_2") (pintype "passive"))
      (node (ref "L4") (pin "2") (pinfunction "2_2") (pintype "passive"))
      (node (ref "L5") (pin "2") (pinfunction "2_2") (pintype "passive"))
      (node (ref "LD5") (pin "A") (pinfunction "A_A") (pintype "passive"))
      (node (ref "Q1") (pin "1") (pinfunction "1_1") (pintype "passive"))
      (node (ref "Q1") (pin "4") (pinfunction "4_4") (pintype "passive"))
      (node (ref "R1") (pin "2") (pinfunction "2_2") (pintype "passive"))
      (node (ref "R100") (pin "2") (pinfunction "2_2") (pintype "passive"))
      (node (ref "R19") (pin "2") (pinfunction "2_2") (pintype "passive"))
      (node (ref "R2") (pin "2") (pinfunction "2_2") (pintype "passive"))
      (node (ref "R20") (pin "2") (pinfunction "2_2") (pintype "passive"))
      (node (ref "R23") (pin "1") (pinfunction "1_1") (pintype "passive"))
      (node (ref "R34") (pin "5") (pinfunction "2_5") (pintype "passive"))
      (node (ref "R34") (pin "6") (pinfunction "2_6") (pintype "passive"))
      (node (ref "R34") (pin "7") (pinfunction "2_7") (pintype "passive"))
      (node (ref "R34") (pin "8") (pinfunction "2_8") (pintype "passive"))
      (node (ref "R35") (pin "2") (pinfunction "2_2") (pintype "passive"))
      (node (ref "R6") (pin "2") (pinfunction "2_2") (pintype "passive"))
      (node (ref "R7") (pin "2") (pinfunction "2_2") (pintype "passive"))
      (node (ref "R71") (pin "2") (pinfunction "2_2") (pintype "passive"))
      (node (ref "R77") (pin "2") (pinfunction "2_2") (pintype "passive"))
      (node (ref "R80") (pin "1") (pinfunction "1_1") (pintype "passive"))
      (node (ref "R81") (pin "1") (pinfunction "1_1") (pintype "passive"))
      (node (ref "R82") (pin "1") (pinfunction "1_1") (pintype "passive"))
      (node (ref "R89") (pin "2") (pinfunction "2_2") (pintype "passive"))
      (node (ref "R90") (pin "2") (pinfunction "2_2") (pintype "passive"))
      (node (ref "R91") (pin "2") (pinfunction "2_2") (pintype "passive"))
      (node (ref "R92") (pin "2") (pinfunction "2_2") (pintype "passive"))
      (node (ref "R93") (pin "2") (pinfunction "2_2") (pintype "passive"))
      (node (ref "R94") (pin "2") (pinfunction "2_2") (pintype "passive"))
      (node (ref "R96") (pin "2") (pinfunction "2_2") (pintype "passive"))
      (node (ref "R97") (pin "2") (pinfunction "2_2") (pintype "passive"))
      (node (ref "R98") (pin "2") (pinfunction "2_2") (pintype "passive"))
      (node (ref "R99") (pin "2") (pinfunction "2_2") (pintype "passive"))
      (node (ref "U1") (pin "B19") (pinfunction "VCCO_16_B19") (pintype "power_in"))
      (node (ref "U1") (pin "C14") (pinfunction "VCCO_16_C14") (pintype "power_in"))
      (node (ref "U1") (pin "C18") (pinfunction "VCCO_16_C18") (pintype "power_in"))
      (node (ref "U1") (pin "F17") (pinfunction "VCCO_14_F17") (pintype "power_in"))
      (node (ref "U1") (pin "G12") (pinfunction "VCCO_0_G12") (pintype "power_in"))
      (node (ref "U1") (pin "G13") (pinfunction "VCCO_16_G13") (pintype "power_in"))
      (node (ref "U1") (pin "H3") (pinfunction "VCCO_35_H3") (pintype "power_in"))
      (node (ref "U1") (pin "J7") (pinfunction "VCCO_35_J7") (pintype "power_in"))
      (node (ref "U1") (pin "K1") (pinfunction "VCCO_35_K1") (pintype "power_in"))
      (node (ref "U1") (pin "K12") (pinfunction "VCCO_14_K12") (pintype "power_in"))
      (node (ref "U1") (pin "K13") (pinfunction "VCCO_14_K13") (pintype "power_in"))
      (node (ref "U1") (pin "K7") (pinfunction "VCCO_35_K7") (pintype "power_in"))
      (node (ref "U1") (pin "L12") (pinfunction "VCCO_14_L12") (pintype "power_in"))
      (node (ref "U1") (pin "L13") (pinfunction "VCCO_14_L13") (pintype "power_in"))
      (node (ref "U1") (pin "L7") (pinfunction "VCCO_35_L7") (pintype "power_in"))
      (node (ref "U1") (pin "M12") (pinfunction "VCCO_14_M12") (pintype "power_in"))
      (node (ref "U1") (pin "M17") (pinfunction "VCCO_14_M17") (pintype "power_in"))
      (node (ref "U1") (pin "M7") (pinfunction "VCCO_35_M7") (pintype "power_in"))
      (node (ref "U1") (pin "M8") (pinfunction "VCCO_34_M8") (pintype "power_in"))
      (node (ref "U1") (pin "N7") (pinfunction "VCCO_34_N7") (pintype "power_in"))
      (node (ref "U1") (pin "N8") (pinfunction "VCCO_34_N8") (pintype "power_in"))
      (node (ref "U1") (pin "R1") (pinfunction "VCCO_34_R1") (pintype "power_in"))
      (node (ref "U1") (pin "R17") (pinfunction "VCCO_14_R17") (pintype "power_in"))
      (node (ref "U1") (pin "U13") (pinfunction "VCCO_14_U13") (pintype "power_in"))
      (node (ref "U1") (pin "V1") (pinfunction "VCCO_34_V1") (pintype "power_in"))
      (node (ref "U1") (pin "V11") (pinfunction "1_V11") (pintype "input"))
      (node (ref "U1") (pin "V6") (pinfunction "VCCO_34_V6") (pintype "power_in"))
      (node (ref "U1") (pin "V9") (pinfunction "VCCO_0_V9") (pintype "power_in"))
      (node (ref "U10") (pin "8") (pinfunction "VCC_8") (pintype "bidirectional"))
      (node (ref "U2") (pin "20") (pinfunction "VCCIO_20") (pintype "bidirectional"))
      (node (ref "U2") (pin "31") (pinfunction "VCCIO_31") (pintype "bidirectional"))
      (node (ref "U2") (pin "42") (pinfunction "VCCIO_42") (pintype "bidirectional"))
      (node (ref "U2") (pin "50") (pinfunction "VREGIN_50") (pintype "bidirectional"))
      (node (ref "U2") (pin "56") (pinfunction "VCCIO_56") (pintype "bidirectional"))
      (node (ref "U3") (pin "1") (pinfunction "P$1_1") (pintype "bidirectional"))
      (node (ref "U3") (pin "14") (pinfunction "P$1_14") (pintype "bidirectional"))
      (node (ref "U3") (pin "27") (pinfunction "P$1_27") (pintype "bidirectional"))
      (node (ref "U3") (pin "3") (pinfunction "P$1_3") (pintype "bidirectional"))
      (node (ref "U3") (pin "43") (pinfunction "P$1_43") (pintype "bidirectional"))
      (node (ref "U3") (pin "49") (pinfunction "P$1_49") (pintype "bidirectional"))
      (node (ref "U3") (pin "9") (pinfunction "P$1_9") (pintype "bidirectional"))
      (node (ref "U4") (pin "8") (pinfunction "1_8") (pintype "input"))
      (node (ref "X2") (pin "17") (pinfunction "1_17") (pintype "bidirectional"))
      (node (ref "X2") (pin "2") (pinfunction "1_2") (pintype "bidirectional"))
      (node (ref "X3") (pin "4") (pinfunction "VDD_4") (pintype "passive"))
    )
    (net (code "172") (name "VCCADC") (class "Default")
      (node (ref "C123") (pin "1") (pinfunction "1_1") (pintype "passive"))
      (node (ref "C124") (pin "1") (pinfunction "1_1") (pintype "passive"))
      (node (ref "L7") (pin "2") (pinfunction "2_2") (pintype "passive"))
      (node (ref "U1") (pin "C13") (pinfunction "1_C13") (pintype "input"))
    )
    (net (code "173") (name "VEXT") (class "Default")
      (node (ref "D2") (pin "A") (pinfunction "A_A") (pintype "passive"))
      (node (ref "D3") (pin "K") (pinfunction "K_K") (pintype "passive"))
      (node (ref "X2") (pin "44") (pinfunction "1_44") (pintype "bidirectional"))
    )
    (net (code "174") (name "VU") (class "Default")
      (node (ref "C78") (pin "2") (pinfunction "2_2") (pintype "passive"))
      (node (ref "D1") (pin "K") (pinfunction "K_K") (pintype "passive"))
      (node (ref "D2") (pin "K") (pinfunction "K_K") (pintype "passive"))
      (node (ref "R72") (pin "2") (pinfunction "2_2") (pintype "passive"))
      (node (ref "R75") (pin "2") (pinfunction "2_2") (pintype "passive"))
      (node (ref "R76") (pin "2") (pinfunction "2_2") (pintype "passive"))
      (node (ref "U8") (pin "10") (pinfunction "SVIN_10") (pintype "input"))
      (node (ref "U8") (pin "14") (pinfunction "EN1_14") (pintype "input"))
      (node (ref "U8") (pin "17") (pinfunction "PVIN3_17") (pintype "input"))
      (node (ref "U8") (pin "18") (pinfunction "PVIN1_18") (pintype "input"))
      (node (ref "U8") (pin "3") (pinfunction "PVIN2_3") (pintype "input"))
      (node (ref "U8") (pin "6") (pinfunction "RT_6") (pintype "input"))
      (node (ref "X2") (pin "22") (pinfunction "1_22") (pintype "bidirectional"))
    )
    (net (code "175") (name "WE#") (class "Default")
      (node (ref "U1") (pin "V4") (pinfunction "1_V4") (pintype "bidirectional"))
      (node (ref "U3") (pin "16") (pinfunction "P$1_16") (pintype "bidirectional"))
    )
    (net (code "176") (name "unconnected-(U1BI-1-PadD1)") (class "Default")
      (node (ref "U1") (pin "D1") (pinfunction "1_D1") (pintype "input"))
    )
    (net (code "177") (name "unconnected-(U1BJ-1-PadA2)") (class "Default")
      (node (ref "U1") (pin "A2") (pinfunction "1_A2") (pintype "input"))
    )
    (net (code "178") (name "unconnected-(U1BK-1-PadD2)") (class "Default")
      (node (ref "U1") (pin "D2") (pinfunction "1_D2") (pintype "input"))
    )
    (net (code "179") (name "unconnected-(U1BL-1-PadB2)") (class "Default")
      (node (ref "U1") (pin "B2") (pinfunction "1_B2") (pintype "input"))
    )
    (net (code "180") (name "unconnected-(U1BM-1-PadA8)") (class "Default")
      (node (ref "U1") (pin "A8") (pinfunction "1_A8") (pintype "input"))
    )
    (net (code "181") (name "unconnected-(U1BN-1-PadB8)") (class "Default")
      (node (ref "U1") (pin "B8") (pinfunction "1_B8") (pintype "input"))
    )
    (net (code "182") (name "unconnected-(U1BO-1-PadA10)") (class "Default")
      (node (ref "U1") (pin "A10") (pinfunction "1_A10") (pintype "input"))
    )
    (net (code "183") (name "unconnected-(U1BP-1-PadB10)") (class "Default")
      (node (ref "U1") (pin "B10") (pinfunction "1_B10") (pintype "input"))
    )
    (net (code "184") (name "unconnected-(U2-ACBUS0-Pad26)") (class "Default")
      (node (ref "U2") (pin "26") (pinfunction "ACBUS0_26") (pintype "bidirectional"))
    )
    (net (code "185") (name "unconnected-(U2-ACBUS1-Pad27)") (class "Default")
      (node (ref "U2") (pin "27") (pinfunction "ACBUS1_27") (pintype "bidirectional"))
    )
    (net (code "186") (name "unconnected-(U2-ACBUS2-Pad28)") (class "Default")
      (node (ref "U2") (pin "28") (pinfunction "ACBUS2_28") (pintype "bidirectional"))
    )
    (net (code "187") (name "unconnected-(U2-ACBUS3-Pad29)") (class "Default")
      (node (ref "U2") (pin "29") (pinfunction "ACBUS3_29") (pintype "bidirectional"))
    )
    (net (code "188") (name "unconnected-(U2-ACBUS4-Pad30)") (class "Default")
      (node (ref "U2") (pin "30") (pinfunction "ACBUS4_30") (pintype "bidirectional"))
    )
    (net (code "189") (name "unconnected-(U2-ACBUS5-Pad32)") (class "Default")
      (node (ref "U2") (pin "32") (pinfunction "ACBUS5_32") (pintype "bidirectional"))
    )
    (net (code "190") (name "unconnected-(U2-ACBUS6-Pad33)") (class "Default")
      (node (ref "U2") (pin "33") (pinfunction "ACBUS6_33") (pintype "bidirectional"))
    )
    (net (code "191") (name "unconnected-(U2-ACBUS7-Pad34)") (class "Default")
      (node (ref "U2") (pin "34") (pinfunction "ACBUS7_34") (pintype "bidirectional"))
    )
    (net (code "192") (name "unconnected-(U2-ADBUS6-Pad23)") (class "Default")
      (node (ref "U2") (pin "23") (pinfunction "ADBUS6_23") (pintype "bidirectional"))
    )
    (net (code "193") (name "unconnected-(U2-ADBUS7-Pad24)") (class "Default")
      (node (ref "U2") (pin "24") (pinfunction "ADBUS7_24") (pintype "bidirectional"))
    )
    (net (code "194") (name "unconnected-(U2-BCBUS0-Pad48)") (class "Default")
      (node (ref "U2") (pin "48") (pinfunction "BCBUS0_48") (pintype "bidirectional"))
    )
    (net (code "195") (name "unconnected-(U2-BCBUS1-Pad52)") (class "Default")
      (node (ref "U2") (pin "52") (pinfunction "BCBUS1_52") (pintype "bidirectional"))
    )
    (net (code "196") (name "unconnected-(U2-BCBUS2-Pad53)") (class "Default")
      (node (ref "U2") (pin "53") (pinfunction "BCBUS2_53") (pintype "bidirectional"))
    )
    (net (code "197") (name "unconnected-(U2-BCBUS3-Pad54)") (class "Default")
      (node (ref "U2") (pin "54") (pinfunction "BCBUS3_54") (pintype "bidirectional"))
    )
    (net (code "198") (name "unconnected-(U2-BCBUS4-Pad55)") (class "Default")
      (node (ref "U2") (pin "55") (pinfunction "BCBUS4_55") (pintype "bidirectional"))
    )
    (net (code "199") (name "unconnected-(U2-BCBUS5-Pad57)") (class "Default")
      (node (ref "U2") (pin "57") (pinfunction "BCBUS5_57") (pintype "bidirectional"))
    )
    (net (code "200") (name "unconnected-(U2-BCBUS6-Pad58)") (class "Default")
      (node (ref "U2") (pin "58") (pinfunction "BCBUS6_58") (pintype "bidirectional"))
    )
    (net (code "201") (name "unconnected-(U2-BCBUS7-Pad59)") (class "Default")
      (node (ref "U2") (pin "59") (pinfunction "BCBUS7_59") (pintype "bidirectional"))
    )
    (net (code "202") (name "unconnected-(U2-BDBUS5-Pad44)") (class "Default")
      (node (ref "U2") (pin "44") (pinfunction "BDBUS5_44") (pintype "bidirectional"))
    )
    (net (code "203") (name "unconnected-(U2-BDBUS6-Pad45)") (class "Default")
      (node (ref "U2") (pin "45") (pinfunction "BDBUS6_45") (pintype "bidirectional"))
    )
    (net (code "204") (name "unconnected-(U2-BDBUS7-Pad46)") (class "Default")
      (node (ref "U2") (pin "46") (pinfunction "BDBUS7_46") (pintype "bidirectional"))
    )
    (net (code "205") (name "unconnected-(U2-OSCO-Pad3)") (class "Default")
      (node (ref "U2") (pin "3") (pinfunction "OSCO_3") (pintype "bidirectional"))
    )
    (net (code "206") (name "unconnected-(U2-SUSPEND#-Pad36)") (class "Default")
      (node (ref "U2") (pin "36") (pinfunction "SUSPEND#_36") (pintype "bidirectional"))
    )
    (net (code "207") (name "unconnected-(U3AK-P$1-Pad40)") (class "Default")
      (node (ref "U3") (pin "40") (pinfunction "P$1_40") (pintype "bidirectional"))
    )
    (net (code "208") (name "unconnected-(U10-NC-Pad6)") (class "Default")
      (node (ref "U10") (pin "6") (pinfunction "NC_6") (pintype "bidirectional"))
    )
    (net (code "209") (name "unconnected-(U10-NC-Pad7)") (class "Default")
      (node (ref "U10") (pin "7") (pinfunction "NC_7") (pintype "bidirectional"))
    )
    (net (code "210") (name "unconnected-(X1-Pad4)") (class "Default")
      (node (ref "X1") (pin "4") (pinfunction "4_4") (pintype "input"))
    )
  )
)
